# TG21_mach_nut_nhan__V1_ReV.net
KiCad netlist of a schematic drawn in Altium Designer
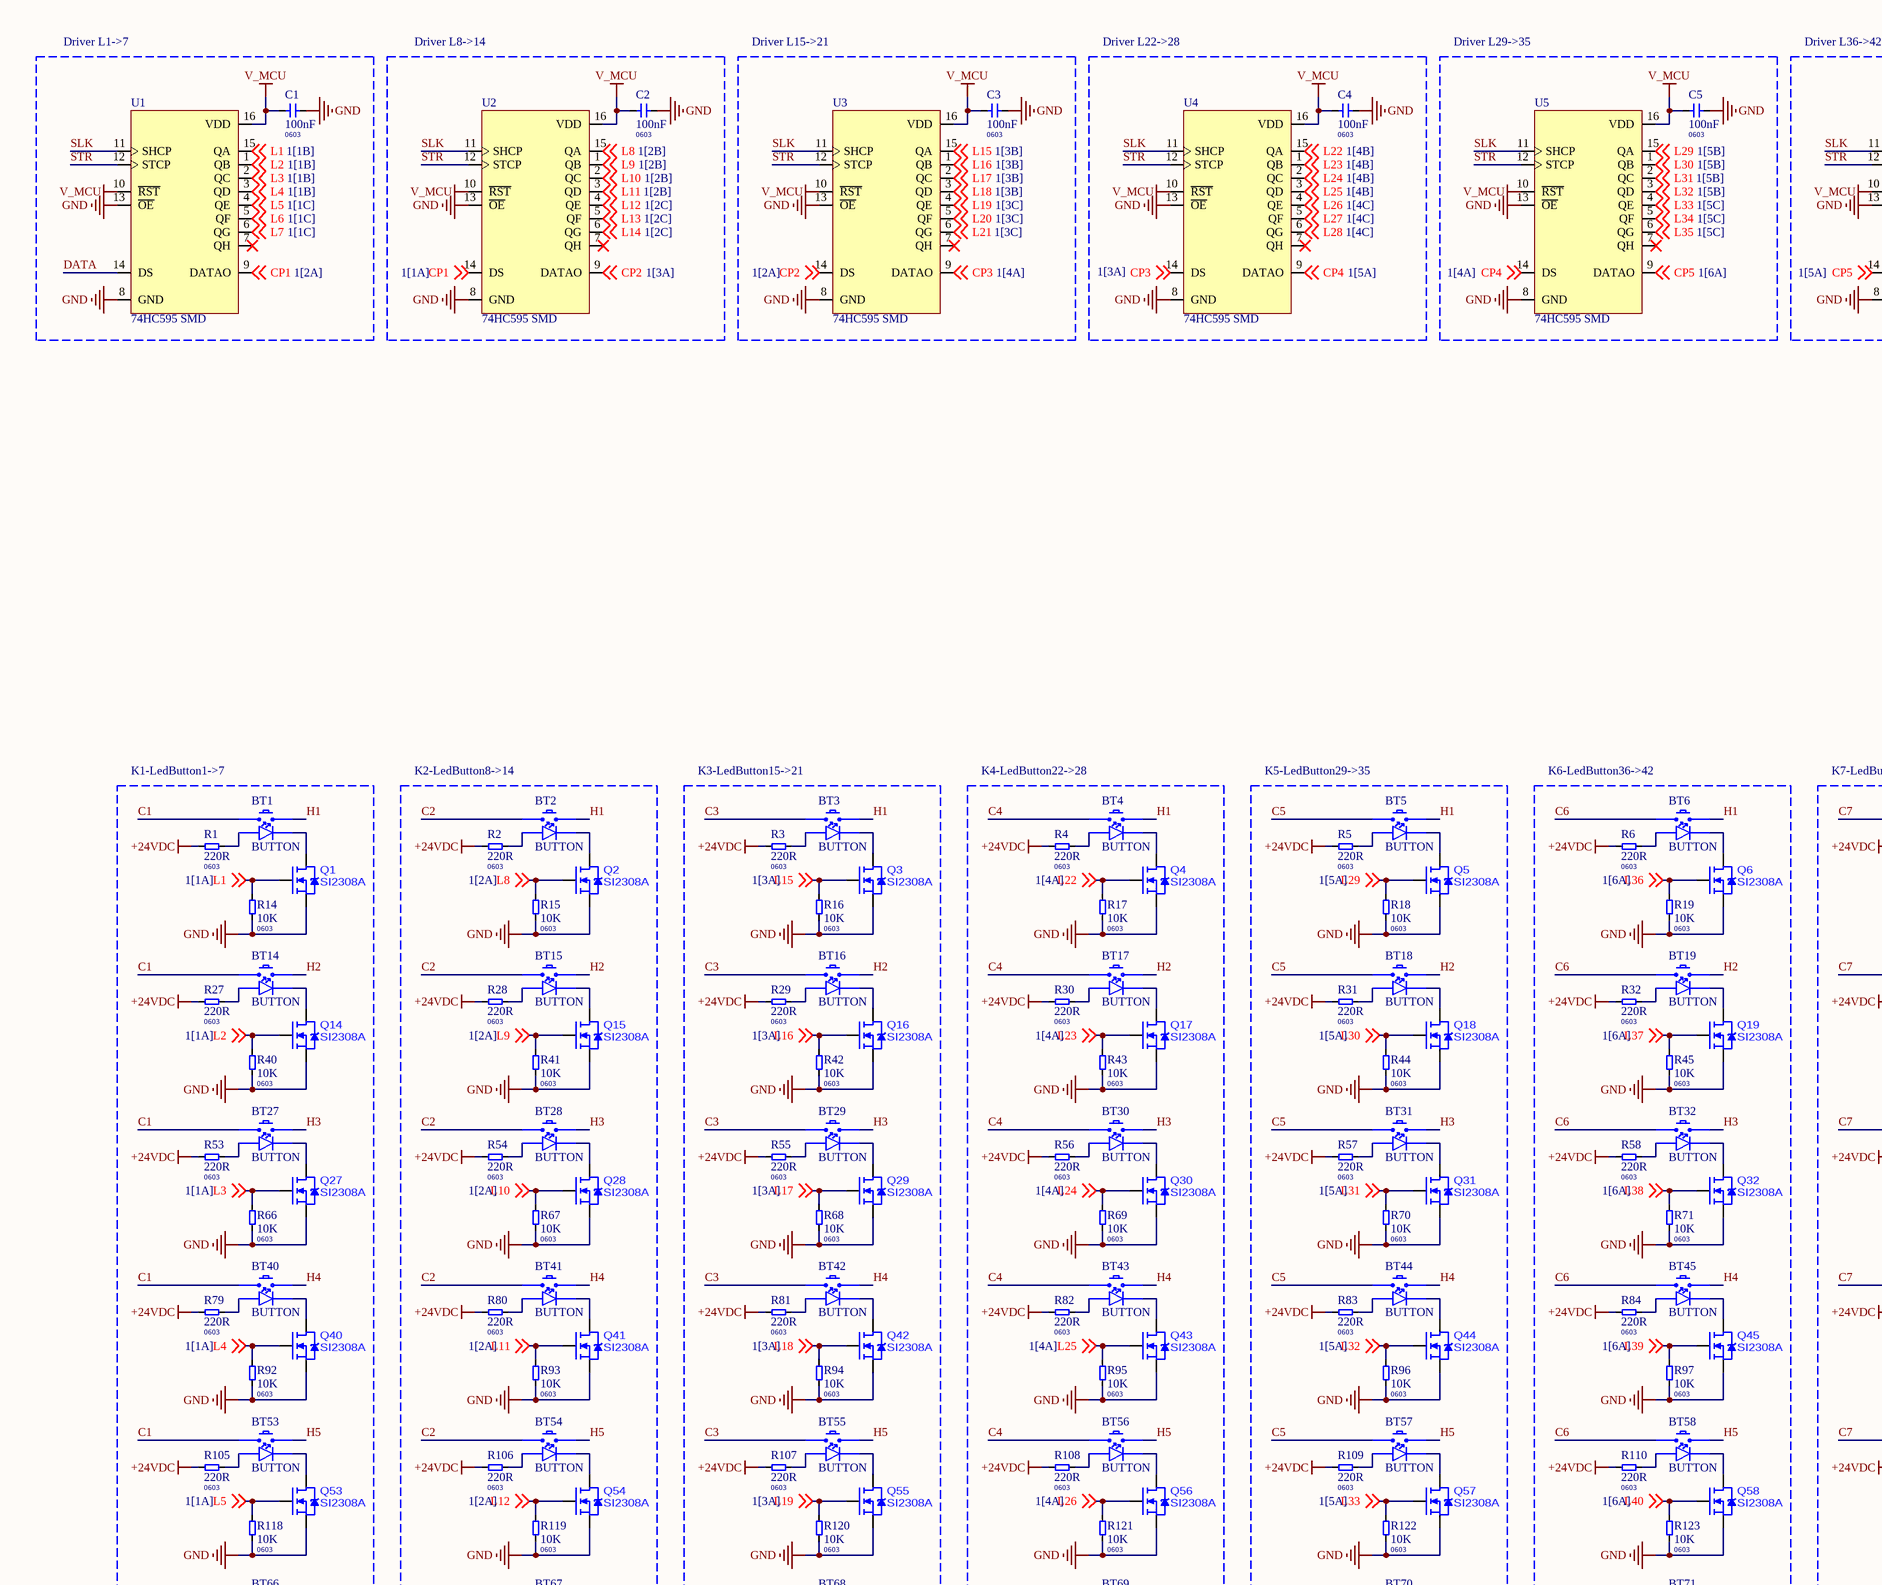
[diagram p0: TG21_mach_nut_nhan _V1_ReV.SchDoc, top left]
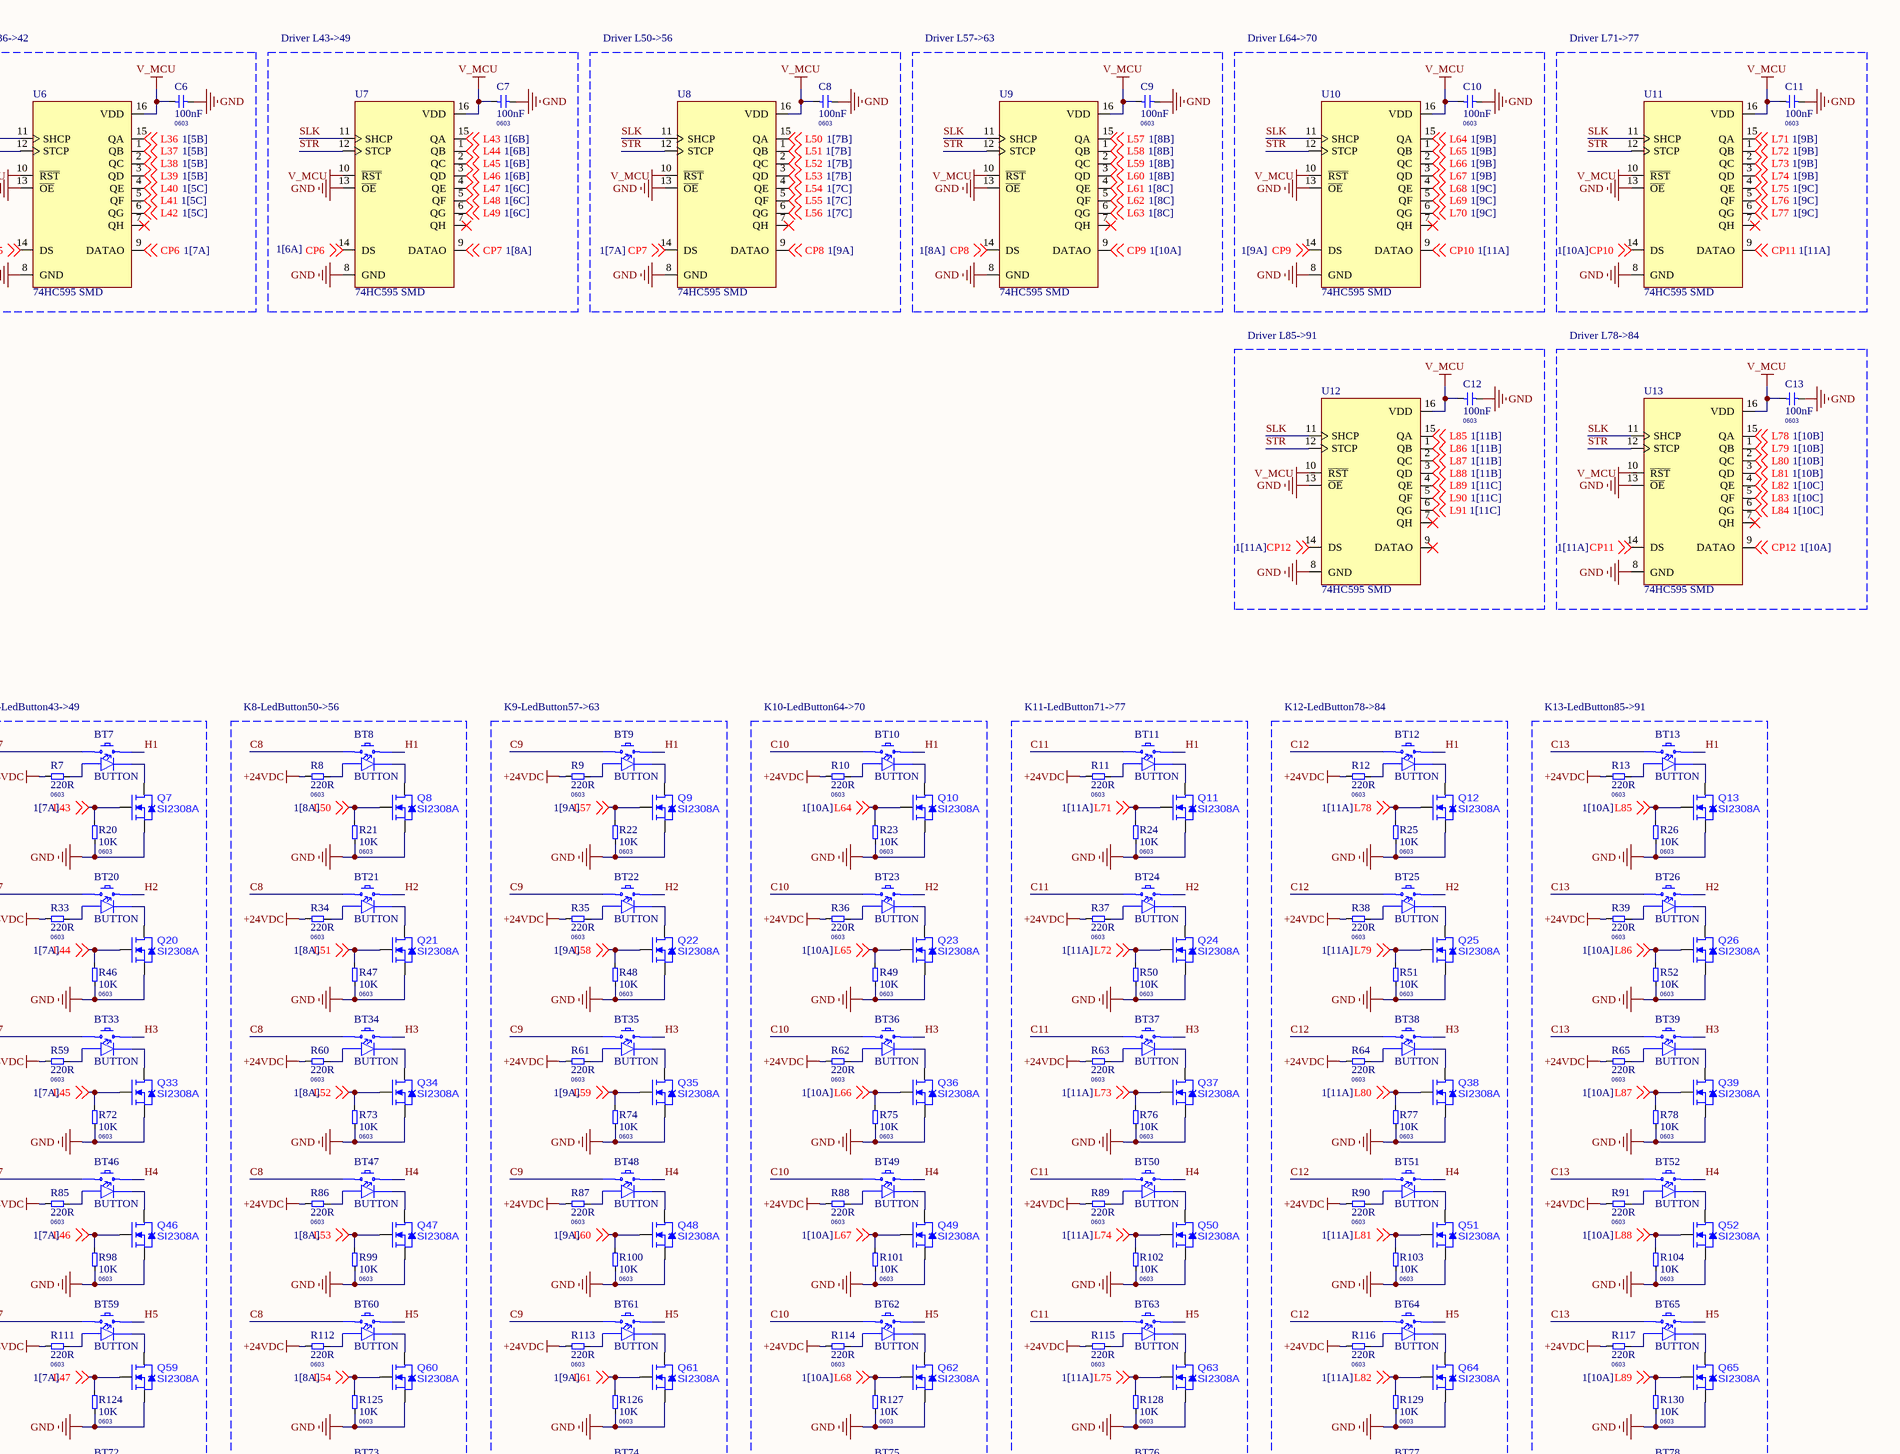
[diagram p1: TG21_mach_nut_nhan _V1_ReV.SchDoc, top right]
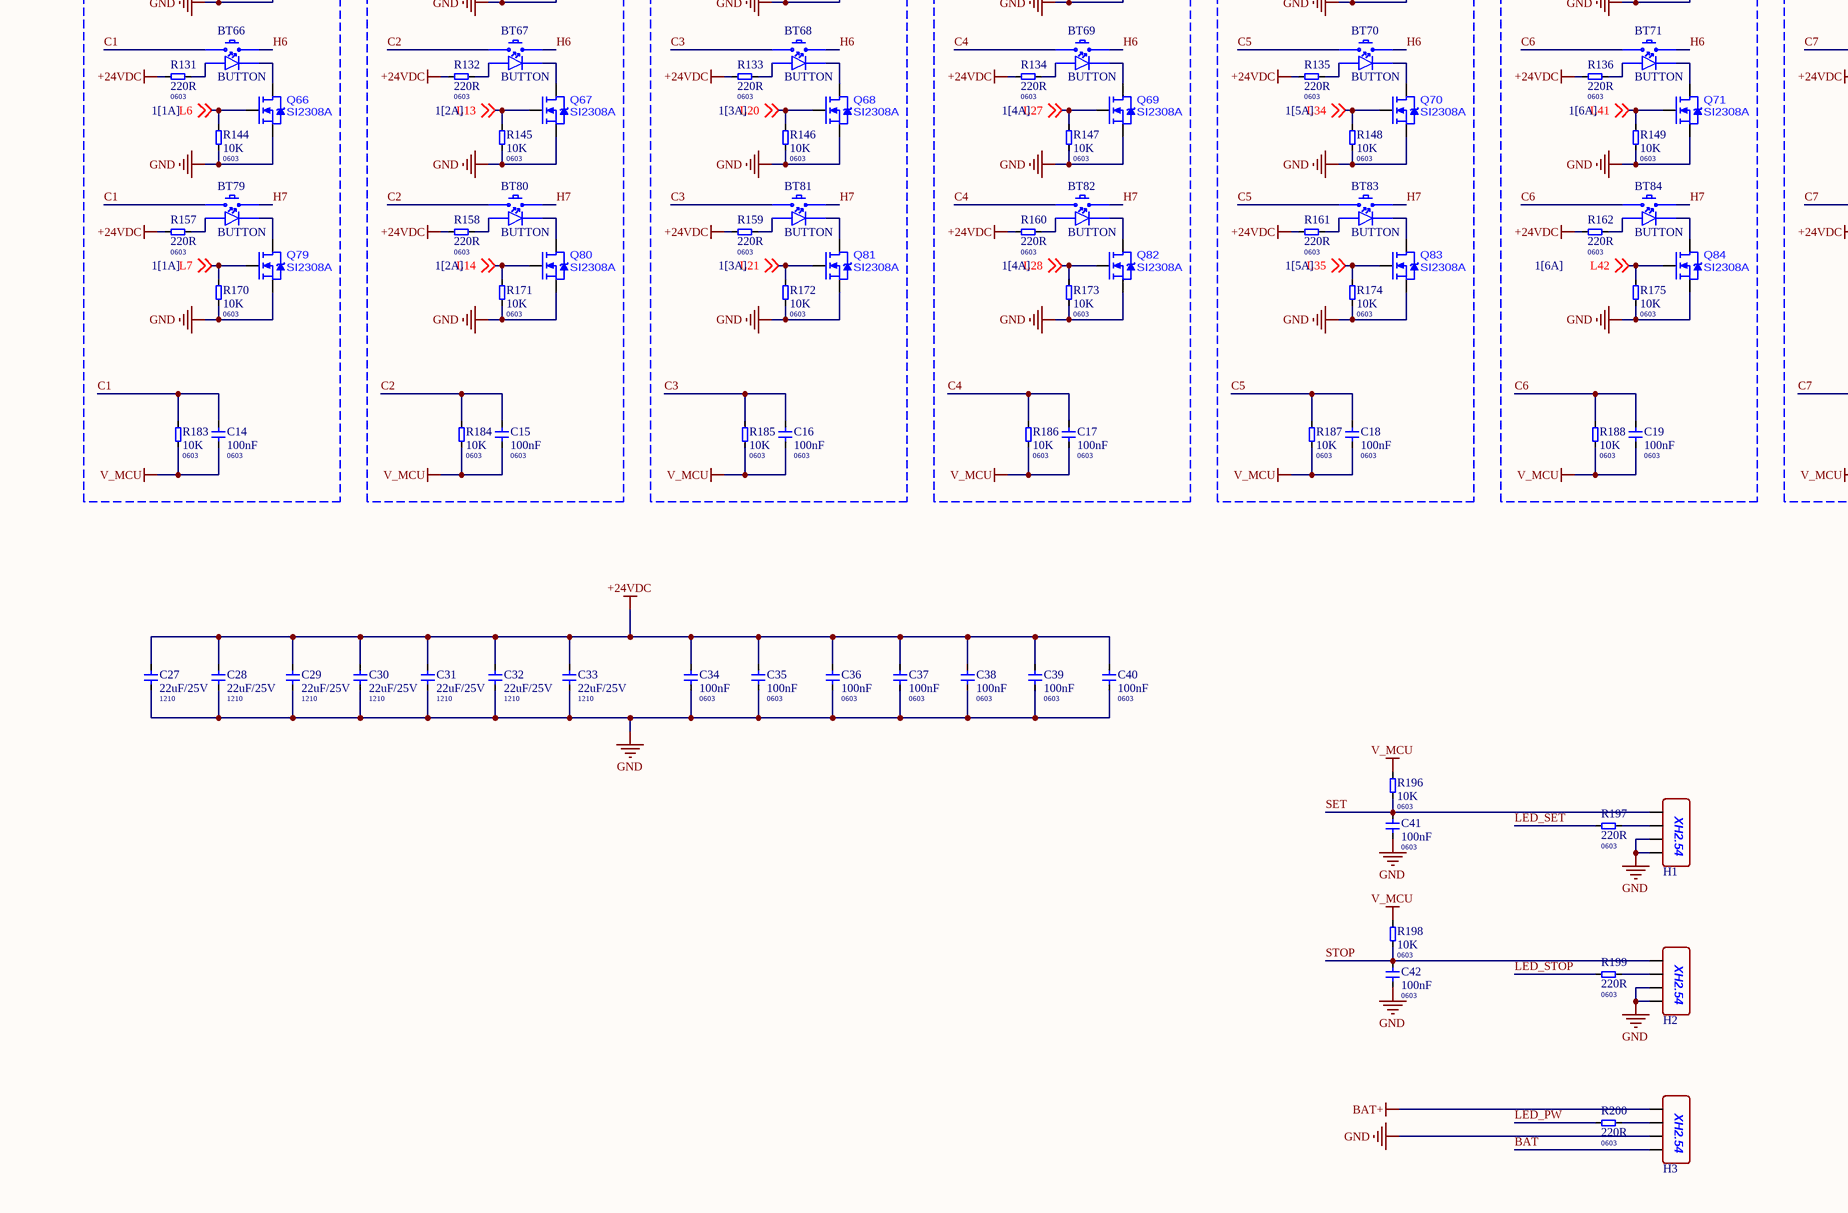
[diagram p2: TG21_mach_nut_nhan _V1_ReV.SchDoc, bottom left]
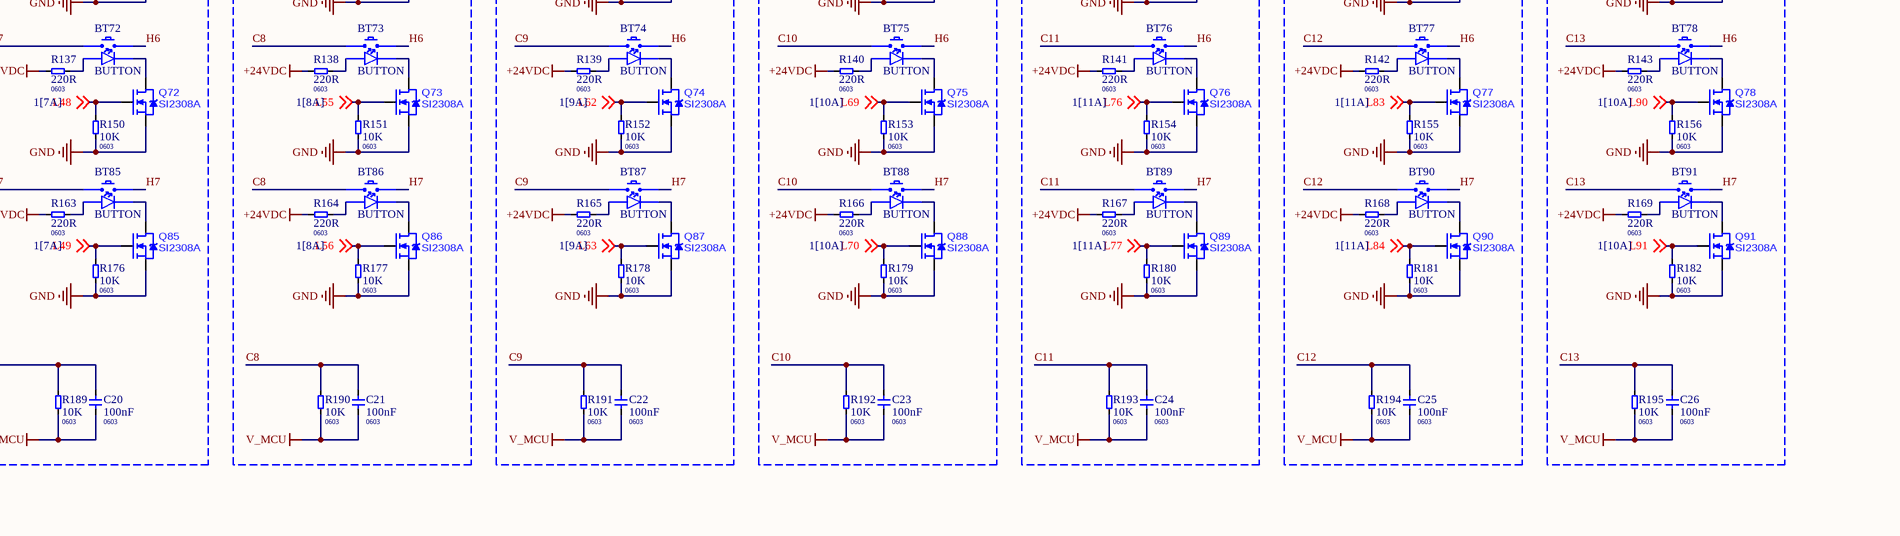
[diagram p3: TG21_mach_nut_nhan _V1_ReV.SchDoc, bottom right]

(export (version "E")
  (design (tool "Eeschema 10.0.6"))
  (components
    (comp (ref "BT1")
      (value "BUTTON")
      (footprint "Metal Push Button Switch")
      (libsource (lib "TG21_TX_Ma tran phimPrjPcb") (part "Metal Push Button Switch"))
    )
    (comp (ref "BT2")
      (value "BUTTON")
      (footprint "Metal Push Button Switch")
      (libsource (lib "TG21_TX_Ma tran phimPrjPcb") (part "Metal Push Button Switch"))
    )
    (comp (ref "BT3")
      (value "BUTTON")
      (footprint "Metal Push Button Switch")
      (libsource (lib "TG21_TX_Ma tran phimPrjPcb") (part "Metal Push Button Switch"))
    )
    (comp (ref "BT4")
      (value "BUTTON")
      (footprint "Metal Push Button Switch")
      (libsource (lib "TG21_TX_Ma tran phimPrjPcb") (part "Metal Push Button Switch"))
    )
    (comp (ref "BT5")
      (value "BUTTON")
      (footprint "Metal Push Button Switch")
      (libsource (lib "TG21_TX_Ma tran phimPrjPcb") (part "Metal Push Button Switch"))
    )
    (comp (ref "BT6")
      (value "BUTTON")
      (footprint "Metal Push Button Switch")
      (libsource (lib "TG21_TX_Ma tran phimPrjPcb") (part "Metal Push Button Switch"))
    )
    (comp (ref "BT7")
      (value "BUTTON")
      (footprint "Metal Push Button Switch")
      (libsource (lib "TG21_TX_Ma tran phimPrjPcb") (part "Metal Push Button Switch"))
    )
    (comp (ref "BT8")
      (value "BUTTON")
      (footprint "Metal Push Button Switch")
      (libsource (lib "TG21_TX_Ma tran phimPrjPcb") (part "Metal Push Button Switch"))
    )
    (comp (ref "BT9")
      (value "BUTTON")
      (footprint "Metal Push Button Switch")
      (libsource (lib "TG21_TX_Ma tran phimPrjPcb") (part "Metal Push Button Switch"))
    )
    (comp (ref "BT10")
      (value "BUTTON")
      (footprint "Metal Push Button Switch")
      (libsource (lib "TG21_TX_Ma tran phimPrjPcb") (part "Metal Push Button Switch"))
    )
    (comp (ref "BT11")
      (value "BUTTON")
      (footprint "Metal Push Button Switch")
      (libsource (lib "TG21_TX_Ma tran phimPrjPcb") (part "Metal Push Button Switch"))
    )
    (comp (ref "BT12")
      (value "BUTTON")
      (footprint "Metal Push Button Switch")
      (libsource (lib "TG21_TX_Ma tran phimPrjPcb") (part "Metal Push Button Switch"))
    )
    (comp (ref "BT13")
      (value "BUTTON")
      (footprint "Metal Push Button Switch")
      (libsource (lib "TG21_TX_Ma tran phimPrjPcb") (part "Metal Push Button Switch"))
    )
    (comp (ref "BT14")
      (value "BUTTON")
      (footprint "Metal Push Button Switch")
      (libsource (lib "TG21_TX_Ma tran phimPrjPcb") (part "Metal Push Button Switch"))
    )
    (comp (ref "BT15")
      (value "BUTTON")
      (footprint "Metal Push Button Switch")
      (libsource (lib "TG21_TX_Ma tran phimPrjPcb") (part "Metal Push Button Switch"))
    )
    (comp (ref "BT16")
      (value "BUTTON")
      (footprint "Metal Push Button Switch")
      (libsource (lib "TG21_TX_Ma tran phimPrjPcb") (part "Metal Push Button Switch"))
    )
    (comp (ref "BT17")
      (value "BUTTON")
      (footprint "Metal Push Button Switch")
      (libsource (lib "TG21_TX_Ma tran phimPrjPcb") (part "Metal Push Button Switch"))
    )
    (comp (ref "BT18")
      (value "BUTTON")
      (footprint "Metal Push Button Switch")
      (libsource (lib "TG21_TX_Ma tran phimPrjPcb") (part "Metal Push Button Switch"))
    )
    (comp (ref "BT19")
      (value "BUTTON")
      (footprint "Metal Push Button Switch")
      (libsource (lib "TG21_TX_Ma tran phimPrjPcb") (part "Metal Push Button Switch"))
    )
    (comp (ref "BT20")
      (value "BUTTON")
      (footprint "Metal Push Button Switch")
      (libsource (lib "TG21_TX_Ma tran phimPrjPcb") (part "Metal Push Button Switch"))
    )
    (comp (ref "BT21")
      (value "BUTTON")
      (footprint "Metal Push Button Switch")
      (libsource (lib "TG21_TX_Ma tran phimPrjPcb") (part "Metal Push Button Switch"))
    )
    (comp (ref "BT22")
      (value "BUTTON")
      (footprint "Metal Push Button Switch")
      (libsource (lib "TG21_TX_Ma tran phimPrjPcb") (part "Metal Push Button Switch"))
    )
    (comp (ref "BT23")
      (value "BUTTON")
      (footprint "Metal Push Button Switch")
      (libsource (lib "TG21_TX_Ma tran phimPrjPcb") (part "Metal Push Button Switch"))
    )
    (comp (ref "BT24")
      (value "BUTTON")
      (footprint "Metal Push Button Switch")
      (libsource (lib "TG21_TX_Ma tran phimPrjPcb") (part "Metal Push Button Switch"))
    )
    (comp (ref "BT25")
      (value "BUTTON")
      (footprint "Metal Push Button Switch")
      (libsource (lib "TG21_TX_Ma tran phimPrjPcb") (part "Metal Push Button Switch"))
    )
    (comp (ref "BT26")
      (value "BUTTON")
      (footprint "Metal Push Button Switch")
      (libsource (lib "TG21_TX_Ma tran phimPrjPcb") (part "Metal Push Button Switch"))
    )
    (comp (ref "BT27")
      (value "BUTTON")
      (footprint "Metal Push Button Switch")
      (libsource (lib "TG21_TX_Ma tran phimPrjPcb") (part "Metal Push Button Switch"))
    )
    (comp (ref "BT28")
      (value "BUTTON")
      (footprint "Metal Push Button Switch")
      (libsource (lib "TG21_TX_Ma tran phimPrjPcb") (part "Metal Push Button Switch"))
    )
    (comp (ref "BT29")
      (value "BUTTON")
      (footprint "Metal Push Button Switch")
      (libsource (lib "TG21_TX_Ma tran phimPrjPcb") (part "Metal Push Button Switch"))
    )
    (comp (ref "BT30")
      (value "BUTTON")
      (footprint "Metal Push Button Switch")
      (libsource (lib "TG21_TX_Ma tran phimPrjPcb") (part "Metal Push Button Switch"))
    )
    (comp (ref "BT31")
      (value "BUTTON")
      (footprint "Metal Push Button Switch")
      (libsource (lib "TG21_TX_Ma tran phimPrjPcb") (part "Metal Push Button Switch"))
    )
    (comp (ref "BT32")
      (value "BUTTON")
      (footprint "Metal Push Button Switch")
      (libsource (lib "TG21_TX_Ma tran phimPrjPcb") (part "Metal Push Button Switch"))
    )
    (comp (ref "BT33")
      (value "BUTTON")
      (footprint "Metal Push Button Switch")
      (libsource (lib "TG21_TX_Ma tran phimPrjPcb") (part "Metal Push Button Switch"))
    )
    (comp (ref "BT34")
      (value "BUTTON")
      (footprint "Metal Push Button Switch")
      (libsource (lib "TG21_TX_Ma tran phimPrjPcb") (part "Metal Push Button Switch"))
    )
    (comp (ref "BT35")
      (value "BUTTON")
      (footprint "Metal Push Button Switch")
      (libsource (lib "TG21_TX_Ma tran phimPrjPcb") (part "Metal Push Button Switch"))
    )
    (comp (ref "BT36")
      (value "BUTTON")
      (footprint "Metal Push Button Switch")
      (libsource (lib "TG21_TX_Ma tran phimPrjPcb") (part "Metal Push Button Switch"))
    )
    (comp (ref "BT37")
      (value "BUTTON")
      (footprint "Metal Push Button Switch")
      (libsource (lib "TG21_TX_Ma tran phimPrjPcb") (part "Metal Push Button Switch"))
    )
    (comp (ref "BT38")
      (value "BUTTON")
      (footprint "Metal Push Button Switch")
      (libsource (lib "TG21_TX_Ma tran phimPrjPcb") (part "Metal Push Button Switch"))
    )
    (comp (ref "BT39")
      (value "BUTTON")
      (footprint "Metal Push Button Switch")
      (libsource (lib "TG21_TX_Ma tran phimPrjPcb") (part "Metal Push Button Switch"))
    )
    (comp (ref "BT40")
      (value "BUTTON")
      (footprint "Metal Push Button Switch")
      (libsource (lib "TG21_TX_Ma tran phimPrjPcb") (part "Metal Push Button Switch"))
    )
    (comp (ref "BT41")
      (value "BUTTON")
      (footprint "Metal Push Button Switch")
      (libsource (lib "TG21_TX_Ma tran phimPrjPcb") (part "Metal Push Button Switch"))
    )
    (comp (ref "BT42")
      (value "BUTTON")
      (footprint "Metal Push Button Switch")
      (libsource (lib "TG21_TX_Ma tran phimPrjPcb") (part "Metal Push Button Switch"))
    )
    (comp (ref "BT43")
      (value "BUTTON")
      (footprint "Metal Push Button Switch")
      (libsource (lib "TG21_TX_Ma tran phimPrjPcb") (part "Metal Push Button Switch"))
    )
    (comp (ref "BT44")
      (value "BUTTON")
      (footprint "Metal Push Button Switch")
      (libsource (lib "TG21_TX_Ma tran phimPrjPcb") (part "Metal Push Button Switch"))
    )
    (comp (ref "BT45")
      (value "BUTTON")
      (footprint "Metal Push Button Switch")
      (libsource (lib "TG21_TX_Ma tran phimPrjPcb") (part "Metal Push Button Switch"))
    )
    (comp (ref "BT46")
      (value "BUTTON")
      (footprint "Metal Push Button Switch")
      (libsource (lib "TG21_TX_Ma tran phimPrjPcb") (part "Metal Push Button Switch"))
    )
    (comp (ref "BT47")
      (value "BUTTON")
      (footprint "Metal Push Button Switch")
      (libsource (lib "TG21_TX_Ma tran phimPrjPcb") (part "Metal Push Button Switch"))
    )
    (comp (ref "BT48")
      (value "BUTTON")
      (footprint "Metal Push Button Switch")
      (libsource (lib "TG21_TX_Ma tran phimPrjPcb") (part "Metal Push Button Switch"))
    )
    (comp (ref "BT49")
      (value "BUTTON")
      (footprint "Metal Push Button Switch")
      (libsource (lib "TG21_TX_Ma tran phimPrjPcb") (part "Metal Push Button Switch"))
    )
    (comp (ref "BT50")
      (value "BUTTON")
      (footprint "Metal Push Button Switch")
      (libsource (lib "TG21_TX_Ma tran phimPrjPcb") (part "Metal Push Button Switch"))
    )
    (comp (ref "BT51")
      (value "BUTTON")
      (footprint "Metal Push Button Switch")
      (libsource (lib "TG21_TX_Ma tran phimPrjPcb") (part "Metal Push Button Switch"))
    )
    (comp (ref "BT52")
      (value "BUTTON")
      (footprint "Metal Push Button Switch")
      (libsource (lib "TG21_TX_Ma tran phimPrjPcb") (part "Metal Push Button Switch"))
    )
    (comp (ref "BT53")
      (value "BUTTON")
      (footprint "Metal Push Button Switch")
      (libsource (lib "TG21_TX_Ma tran phimPrjPcb") (part "Metal Push Button Switch"))
    )
    (comp (ref "BT54")
      (value "BUTTON")
      (footprint "Metal Push Button Switch")
      (libsource (lib "TG21_TX_Ma tran phimPrjPcb") (part "Metal Push Button Switch"))
    )
    (comp (ref "BT55")
      (value "BUTTON")
      (footprint "Metal Push Button Switch")
      (libsource (lib "TG21_TX_Ma tran phimPrjPcb") (part "Metal Push Button Switch"))
    )
    (comp (ref "BT56")
      (value "BUTTON")
      (footprint "Metal Push Button Switch")
      (libsource (lib "TG21_TX_Ma tran phimPrjPcb") (part "Metal Push Button Switch"))
    )
    (comp (ref "BT57")
      (value "BUTTON")
      (footprint "Metal Push Button Switch")
      (libsource (lib "TG21_TX_Ma tran phimPrjPcb") (part "Metal Push Button Switch"))
    )
    (comp (ref "BT58")
      (value "BUTTON")
      (footprint "Metal Push Button Switch")
      (libsource (lib "TG21_TX_Ma tran phimPrjPcb") (part "Metal Push Button Switch"))
    )
    (comp (ref "BT59")
      (value "BUTTON")
      (footprint "Metal Push Button Switch")
      (libsource (lib "TG21_TX_Ma tran phimPrjPcb") (part "Metal Push Button Switch"))
    )
    (comp (ref "BT60")
      (value "BUTTON")
      (footprint "Metal Push Button Switch")
      (libsource (lib "TG21_TX_Ma tran phimPrjPcb") (part "Metal Push Button Switch"))
    )
    (comp (ref "BT61")
      (value "BUTTON")
      (footprint "Metal Push Button Switch")
      (libsource (lib "TG21_TX_Ma tran phimPrjPcb") (part "Metal Push Button Switch"))
    )
    (comp (ref "BT62")
      (value "BUTTON")
      (footprint "Metal Push Button Switch")
      (libsource (lib "TG21_TX_Ma tran phimPrjPcb") (part "Metal Push Button Switch"))
    )
    (comp (ref "BT63")
      (value "BUTTON")
      (footprint "Metal Push Button Switch")
      (libsource (lib "TG21_TX_Ma tran phimPrjPcb") (part "Metal Push Button Switch"))
    )
    (comp (ref "BT64")
      (value "BUTTON")
      (footprint "Metal Push Button Switch")
      (libsource (lib "TG21_TX_Ma tran phimPrjPcb") (part "Metal Push Button Switch"))
    )
    (comp (ref "BT65")
      (value "BUTTON")
      (footprint "Metal Push Button Switch")
      (libsource (lib "TG21_TX_Ma tran phimPrjPcb") (part "Metal Push Button Switch"))
    )
    (comp (ref "BT66")
      (value "BUTTON")
      (footprint "Metal Push Button Switch")
      (libsource (lib "TG21_TX_Ma tran phimPrjPcb") (part "Metal Push Button Switch"))
    )
    (comp (ref "BT67")
      (value "BUTTON")
      (footprint "Metal Push Button Switch")
      (libsource (lib "TG21_TX_Ma tran phimPrjPcb") (part "Metal Push Button Switch"))
    )
    (comp (ref "BT68")
      (value "BUTTON")
      (footprint "Metal Push Button Switch")
      (libsource (lib "TG21_TX_Ma tran phimPrjPcb") (part "Metal Push Button Switch"))
    )
    (comp (ref "BT69")
      (value "BUTTON")
      (footprint "Metal Push Button Switch")
      (libsource (lib "TG21_TX_Ma tran phimPrjPcb") (part "Metal Push Button Switch"))
    )
    (comp (ref "BT70")
      (value "BUTTON")
      (footprint "Metal Push Button Switch")
      (libsource (lib "TG21_TX_Ma tran phimPrjPcb") (part "Metal Push Button Switch"))
    )
    (comp (ref "BT71")
      (value "BUTTON")
      (footprint "Metal Push Button Switch")
      (libsource (lib "TG21_TX_Ma tran phimPrjPcb") (part "Metal Push Button Switch"))
    )
    (comp (ref "BT72")
      (value "BUTTON")
      (footprint "Metal Push Button Switch")
      (libsource (lib "TG21_TX_Ma tran phimPrjPcb") (part "Metal Push Button Switch"))
    )
    (comp (ref "BT73")
      (value "BUTTON")
      (footprint "Metal Push Button Switch")
      (libsource (lib "TG21_TX_Ma tran phimPrjPcb") (part "Metal Push Button Switch"))
    )
    (comp (ref "BT74")
      (value "BUTTON")
      (footprint "Metal Push Button Switch")
      (libsource (lib "TG21_TX_Ma tran phimPrjPcb") (part "Metal Push Button Switch"))
    )
    (comp (ref "BT75")
      (value "BUTTON")
      (footprint "Metal Push Button Switch")
      (libsource (lib "TG21_TX_Ma tran phimPrjPcb") (part "Metal Push Button Switch"))
    )
    (comp (ref "BT76")
      (value "BUTTON")
      (footprint "Metal Push Button Switch")
      (libsource (lib "TG21_TX_Ma tran phimPrjPcb") (part "Metal Push Button Switch"))
    )
    (comp (ref "BT77")
      (value "BUTTON")
      (footprint "Metal Push Button Switch")
      (libsource (lib "TG21_TX_Ma tran phimPrjPcb") (part "Metal Push Button Switch"))
    )
    (comp (ref "BT78")
      (value "BUTTON")
      (footprint "Metal Push Button Switch")
      (libsource (lib "TG21_TX_Ma tran phimPrjPcb") (part "Metal Push Button Switch"))
    )
    (comp (ref "BT79")
      (value "BUTTON")
      (footprint "Metal Push Button Switch")
      (libsource (lib "TG21_TX_Ma tran phimPrjPcb") (part "Metal Push Button Switch"))
    )
    (comp (ref "BT80")
      (value "BUTTON")
      (footprint "Metal Push Button Switch")
      (libsource (lib "TG21_TX_Ma tran phimPrjPcb") (part "Metal Push Button Switch"))
    )
    (comp (ref "BT81")
      (value "BUTTON")
      (footprint "Metal Push Button Switch")
      (libsource (lib "TG21_TX_Ma tran phimPrjPcb") (part "Metal Push Button Switch"))
    )
    (comp (ref "BT82")
      (value "BUTTON")
      (footprint "Metal Push Button Switch")
      (libsource (lib "TG21_TX_Ma tran phimPrjPcb") (part "Metal Push Button Switch"))
    )
    (comp (ref "BT83")
      (value "BUTTON")
      (footprint "Metal Push Button Switch")
      (libsource (lib "TG21_TX_Ma tran phimPrjPcb") (part "Metal Push Button Switch"))
    )
    (comp (ref "BT84")
      (value "BUTTON")
      (footprint "Metal Push Button Switch")
      (libsource (lib "TG21_TX_Ma tran phimPrjPcb") (part "Metal Push Button Switch"))
    )
    (comp (ref "BT85")
      (value "BUTTON")
      (footprint "Metal Push Button Switch")
      (libsource (lib "TG21_TX_Ma tran phimPrjPcb") (part "Metal Push Button Switch"))
    )
    (comp (ref "BT86")
      (value "BUTTON")
      (footprint "Metal Push Button Switch")
      (libsource (lib "TG21_TX_Ma tran phimPrjPcb") (part "Metal Push Button Switch"))
    )
    (comp (ref "BT87")
      (value "BUTTON")
      (footprint "Metal Push Button Switch")
      (libsource (lib "TG21_TX_Ma tran phimPrjPcb") (part "Metal Push Button Switch"))
    )
    (comp (ref "BT88")
      (value "BUTTON")
      (footprint "Metal Push Button Switch")
      (libsource (lib "TG21_TX_Ma tran phimPrjPcb") (part "Metal Push Button Switch"))
    )
    (comp (ref "BT89")
      (value "BUTTON")
      (footprint "Metal Push Button Switch")
      (libsource (lib "TG21_TX_Ma tran phimPrjPcb") (part "Metal Push Button Switch"))
    )
    (comp (ref "BT90")
      (value "BUTTON")
      (footprint "Metal Push Button Switch")
      (libsource (lib "TG21_TX_Ma tran phimPrjPcb") (part "Metal Push Button Switch"))
    )
    (comp (ref "BT91")
      (value "BUTTON")
      (footprint "Metal Push Button Switch")
      (libsource (lib "TG21_TX_Ma tran phimPrjPcb") (part "Metal Push Button Switch"))
    )
    (comp (ref "C1")
      (value "100nF")
      (footprint "0603 MLCC")
      (description "100nF ±10% 50V Ceramic Capacitor X7R 0603")
      (fields
        (field (name "MANUFACTURER") "YAGEO")
        (field (name "MFR. PART #") "CC0603KRX7R9BB104")
        (field (name "PACKAGE") "0603")
      )
      (libsource (lib "TG21_TX_Ma tran phimPrjPcb") (part "0603 100nF"))
    )
    (comp (ref "C2")
      (value "100nF")
      (footprint "0603 MLCC")
      (description "100nF ±10% 50V Ceramic Capacitor X7R 0603")
      (fields
        (field (name "MANUFACTURER") "YAGEO")
        (field (name "MFR. PART #") "CC0603KRX7R9BB104")
        (field (name "PACKAGE") "0603")
      )
      (libsource (lib "TG21_TX_Ma tran phimPrjPcb") (part "0603 100nF"))
    )
    (comp (ref "C3")
      (value "100nF")
      (footprint "0603 MLCC")
      (description "100nF ±10% 50V Ceramic Capacitor X7R 0603")
      (fields
        (field (name "MANUFACTURER") "YAGEO")
        (field (name "MFR. PART #") "CC0603KRX7R9BB104")
        (field (name "PACKAGE") "0603")
      )
      (libsource (lib "TG21_TX_Ma tran phimPrjPcb") (part "0603 100nF"))
    )
    (comp (ref "C4")
      (value "100nF")
      (footprint "0603 MLCC")
      (description "100nF ±10% 50V Ceramic Capacitor X7R 0603")
      (fields
        (field (name "MANUFACTURER") "YAGEO")
        (field (name "MFR. PART #") "CC0603KRX7R9BB104")
        (field (name "PACKAGE") "0603")
      )
      (libsource (lib "TG21_TX_Ma tran phimPrjPcb") (part "0603 100nF"))
    )
    (comp (ref "C5")
      (value "100nF")
      (footprint "0603 MLCC")
      (description "100nF ±10% 50V Ceramic Capacitor X7R 0603")
      (fields
        (field (name "MANUFACTURER") "YAGEO")
        (field (name "MFR. PART #") "CC0603KRX7R9BB104")
        (field (name "PACKAGE") "0603")
      )
      (libsource (lib "TG21_TX_Ma tran phimPrjPcb") (part "0603 100nF"))
    )
    (comp (ref "C6")
      (value "100nF")
      (footprint "0603 MLCC")
      (description "100nF ±10% 50V Ceramic Capacitor X7R 0603")
      (fields
        (field (name "MANUFACTURER") "YAGEO")
        (field (name "MFR. PART #") "CC0603KRX7R9BB104")
        (field (name "PACKAGE") "0603")
      )
      (libsource (lib "TG21_TX_Ma tran phimPrjPcb") (part "0603 100nF"))
    )
    (comp (ref "C7")
      (value "100nF")
      (footprint "0603 MLCC")
      (description "100nF ±10% 50V Ceramic Capacitor X7R 0603")
      (fields
        (field (name "MANUFACTURER") "YAGEO")
        (field (name "MFR. PART #") "CC0603KRX7R9BB104")
        (field (name "PACKAGE") "0603")
      )
      (libsource (lib "TG21_TX_Ma tran phimPrjPcb") (part "0603 100nF"))
    )
    (comp (ref "C8")
      (value "100nF")
      (footprint "0603 MLCC")
      (description "100nF ±10% 50V Ceramic Capacitor X7R 0603")
      (fields
        (field (name "MANUFACTURER") "YAGEO")
        (field (name "MFR. PART #") "CC0603KRX7R9BB104")
        (field (name "PACKAGE") "0603")
      )
      (libsource (lib "TG21_TX_Ma tran phimPrjPcb") (part "0603 100nF"))
    )
    (comp (ref "C9")
      (value "100nF")
      (footprint "0603 MLCC")
      (description "100nF ±10% 50V Ceramic Capacitor X7R 0603")
      (fields
        (field (name "MANUFACTURER") "YAGEO")
        (field (name "MFR. PART #") "CC0603KRX7R9BB104")
        (field (name "PACKAGE") "0603")
      )
      (libsource (lib "TG21_TX_Ma tran phimPrjPcb") (part "0603 100nF"))
    )
    (comp (ref "C10")
      (value "100nF")
      (footprint "0603 MLCC")
      (description "100nF ±10% 50V Ceramic Capacitor X7R 0603")
      (fields
        (field (name "MANUFACTURER") "YAGEO")
        (field (name "MFR. PART #") "CC0603KRX7R9BB104")
        (field (name "PACKAGE") "0603")
      )
      (libsource (lib "TG21_TX_Ma tran phimPrjPcb") (part "0603 100nF"))
    )
    (comp (ref "C11")
      (value "100nF")
      (footprint "0603 MLCC")
      (description "100nF ±10% 50V Ceramic Capacitor X7R 0603")
      (fields
        (field (name "MANUFACTURER") "YAGEO")
        (field (name "MFR. PART #") "CC0603KRX7R9BB104")
        (field (name "PACKAGE") "0603")
      )
      (libsource (lib "TG21_TX_Ma tran phimPrjPcb") (part "0603 100nF"))
    )
    (comp (ref "C12")
      (value "100nF")
      (footprint "0603 MLCC")
      (description "100nF ±10% 50V Ceramic Capacitor X7R 0603")
      (fields
        (field (name "MANUFACTURER") "YAGEO")
        (field (name "MFR. PART #") "CC0603KRX7R9BB104")
        (field (name "PACKAGE") "0603")
      )
      (libsource (lib "TG21_TX_Ma tran phimPrjPcb") (part "0603 100nF"))
    )
    (comp (ref "C13")
      (value "100nF")
      (footprint "0603 MLCC")
      (description "100nF ±10% 50V Ceramic Capacitor X7R 0603")
      (fields
        (field (name "MANUFACTURER") "YAGEO")
        (field (name "MFR. PART #") "CC0603KRX7R9BB104")
        (field (name "PACKAGE") "0603")
      )
      (libsource (lib "TG21_TX_Ma tran phimPrjPcb") (part "0603 100nF"))
    )
    (comp (ref "C14")
      (value "100nF")
      (footprint "0603 MLCC")
      (description "100nF ±10% 50V Ceramic Capacitor X7R 0603")
      (fields
        (field (name "MANUFACTURER") "YAGEO")
        (field (name "MFR. PART #") "CC0603KRX7R9BB104")
        (field (name "PACKAGE") "0603")
      )
      (libsource (lib "TG21_TX_Ma tran phimPrjPcb") (part "0603 100nF"))
    )
    (comp (ref "C15")
      (value "100nF")
      (footprint "0603 MLCC")
      (description "100nF ±10% 50V Ceramic Capacitor X7R 0603")
      (fields
        (field (name "MANUFACTURER") "YAGEO")
        (field (name "MFR. PART #") "CC0603KRX7R9BB104")
        (field (name "PACKAGE") "0603")
      )
      (libsource (lib "TG21_TX_Ma tran phimPrjPcb") (part "0603 100nF"))
    )
    (comp (ref "C16")
      (value "100nF")
      (footprint "0603 MLCC")
      (description "100nF ±10% 50V Ceramic Capacitor X7R 0603")
      (fields
        (field (name "MANUFACTURER") "YAGEO")
        (field (name "MFR. PART #") "CC0603KRX7R9BB104")
        (field (name "PACKAGE") "0603")
      )
      (libsource (lib "TG21_TX_Ma tran phimPrjPcb") (part "0603 100nF"))
    )
    (comp (ref "C17")
      (value "100nF")
      (footprint "0603 MLCC")
      (description "100nF ±10% 50V Ceramic Capacitor X7R 0603")
      (fields
        (field (name "MANUFACTURER") "YAGEO")
        (field (name "MFR. PART #") "CC0603KRX7R9BB104")
        (field (name "PACKAGE") "0603")
      )
      (libsource (lib "TG21_TX_Ma tran phimPrjPcb") (part "0603 100nF"))
    )
    (comp (ref "C18")
      (value "100nF")
      (footprint "0603 MLCC")
      (description "100nF ±10% 50V Ceramic Capacitor X7R 0603")
      (fields
        (field (name "MANUFACTURER") "YAGEO")
        (field (name "MFR. PART #") "CC0603KRX7R9BB104")
        (field (name "PACKAGE") "0603")
      )
      (libsource (lib "TG21_TX_Ma tran phimPrjPcb") (part "0603 100nF"))
    )
    (comp (ref "C19")
      (value "100nF")
      (footprint "0603 MLCC")
      (description "100nF ±10% 50V Ceramic Capacitor X7R 0603")
      (fields
        (field (name "MANUFACTURER") "YAGEO")
        (field (name "MFR. PART #") "CC0603KRX7R9BB104")
        (field (name "PACKAGE") "0603")
      )
      (libsource (lib "TG21_TX_Ma tran phimPrjPcb") (part "0603 100nF"))
    )
    (comp (ref "C20")
      (value "100nF")
      (footprint "0603 MLCC")
      (description "100nF ±10% 50V Ceramic Capacitor X7R 0603")
      (fields
        (field (name "MANUFACTURER") "YAGEO")
        (field (name "MFR. PART #") "CC0603KRX7R9BB104")
        (field (name "PACKAGE") "0603")
      )
      (libsource (lib "TG21_TX_Ma tran phimPrjPcb") (part "0603 100nF"))
    )
    (comp (ref "C21")
      (value "100nF")
      (footprint "0603 MLCC")
      (description "100nF ±10% 50V Ceramic Capacitor X7R 0603")
      (fields
        (field (name "MANUFACTURER") "YAGEO")
        (field (name "MFR. PART #") "CC0603KRX7R9BB104")
        (field (name "PACKAGE") "0603")
      )
      (libsource (lib "TG21_TX_Ma tran phimPrjPcb") (part "0603 100nF"))
    )
    (comp (ref "C22")
      (value "100nF")
      (footprint "0603 MLCC")
      (description "100nF ±10% 50V Ceramic Capacitor X7R 0603")
      (fields
        (field (name "MANUFACTURER") "YAGEO")
        (field (name "MFR. PART #") "CC0603KRX7R9BB104")
        (field (name "PACKAGE") "0603")
      )
      (libsource (lib "TG21_TX_Ma tran phimPrjPcb") (part "0603 100nF"))
    )
    (comp (ref "C23")
      (value "100nF")
      (footprint "0603 MLCC")
      (description "100nF ±10% 50V Ceramic Capacitor X7R 0603")
      (fields
        (field (name "MANUFACTURER") "YAGEO")
        (field (name "MFR. PART #") "CC0603KRX7R9BB104")
        (field (name "PACKAGE") "0603")
      )
      (libsource (lib "TG21_TX_Ma tran phimPrjPcb") (part "0603 100nF"))
    )
    (comp (ref "C24")
      (value "100nF")
      (footprint "0603 MLCC")
      (description "100nF ±10% 50V Ceramic Capacitor X7R 0603")
      (fields
        (field (name "MANUFACTURER") "YAGEO")
        (field (name "MFR. PART #") "CC0603KRX7R9BB104")
        (field (name "PACKAGE") "0603")
      )
      (libsource (lib "TG21_TX_Ma tran phimPrjPcb") (part "0603 100nF"))
    )
    (comp (ref "C25")
      (value "100nF")
      (footprint "0603 MLCC")
      (description "100nF ±10% 50V Ceramic Capacitor X7R 0603")
      (fields
        (field (name "MANUFACTURER") "YAGEO")
        (field (name "MFR. PART #") "CC0603KRX7R9BB104")
        (field (name "PACKAGE") "0603")
      )
      (libsource (lib "TG21_TX_Ma tran phimPrjPcb") (part "0603 100nF"))
    )
    (comp (ref "C26")
      (value "100nF")
      (footprint "0603 MLCC")
      (description "100nF ±10% 50V Ceramic Capacitor X7R 0603")
      (fields
        (field (name "MANUFACTURER") "YAGEO")
        (field (name "MFR. PART #") "CC0603KRX7R9BB104")
        (field (name "PACKAGE") "0603")
      )
      (libsource (lib "TG21_TX_Ma tran phimPrjPcb") (part "0603 100nF"))
    )
    (comp (ref "C27")
      (value "22uF/25V")
      (footprint "1210 CAPACITOR")
      (description "22uF ±10% 25V Ceramic Capacitor X7R 1210")
      (fields
        (field (name "MANUFACTURER") "Samsung Electro-Mechanics")
        (field (name "MFR. PART #") "CL32B226KAJNNNE")
        (field (name "PACKAGE") "1210")
      )
      (libsource (lib "TG21_TX_Ma tran phimPrjPcb") (part "1210 22uF 25V X7R"))
    )
    (comp (ref "C28")
      (value "22uF/25V")
      (footprint "1210 CAPACITOR")
      (description "22uF ±10% 25V Ceramic Capacitor X7R 1210")
      (fields
        (field (name "MANUFACTURER") "Samsung Electro-Mechanics")
        (field (name "MFR. PART #") "CL32B226KAJNNNE")
        (field (name "PACKAGE") "1210")
      )
      (libsource (lib "TG21_TX_Ma tran phimPrjPcb") (part "1210 22uF 25V X7R"))
    )
    (comp (ref "C29")
      (value "22uF/25V")
      (footprint "1210 CAPACITOR")
      (description "22uF ±10% 25V Ceramic Capacitor X7R 1210")
      (fields
        (field (name "MANUFACTURER") "Samsung Electro-Mechanics")
        (field (name "MFR. PART #") "CL32B226KAJNNNE")
        (field (name "PACKAGE") "1210")
      )
      (libsource (lib "TG21_TX_Ma tran phimPrjPcb") (part "1210 22uF 25V X7R"))
    )
    (comp (ref "C30")
      (value "22uF/25V")
      (footprint "1210 CAPACITOR")
      (description "22uF ±10% 25V Ceramic Capacitor X7R 1210")
      (fields
        (field (name "MANUFACTURER") "Samsung Electro-Mechanics")
        (field (name "MFR. PART #") "CL32B226KAJNNNE")
        (field (name "PACKAGE") "1210")
      )
      (libsource (lib "TG21_TX_Ma tran phimPrjPcb") (part "1210 22uF 25V X7R"))
    )
    (comp (ref "C31")
      (value "22uF/25V")
      (footprint "1210 CAPACITOR")
      (description "22uF ±10% 25V Ceramic Capacitor X7R 1210")
      (fields
        (field (name "MANUFACTURER") "Samsung Electro-Mechanics")
        (field (name "MFR. PART #") "CL32B226KAJNNNE")
        (field (name "PACKAGE") "1210")
      )
      (libsource (lib "TG21_TX_Ma tran phimPrjPcb") (part "1210 22uF 25V X7R"))
    )
    (comp (ref "C32")
      (value "22uF/25V")
      (footprint "1210 CAPACITOR")
      (description "22uF ±10% 25V Ceramic Capacitor X7R 1210")
      (fields
        (field (name "MANUFACTURER") "Samsung Electro-Mechanics")
        (field (name "MFR. PART #") "CL32B226KAJNNNE")
        (field (name "PACKAGE") "1210")
      )
      (libsource (lib "TG21_TX_Ma tran phimPrjPcb") (part "1210 22uF 25V X7R"))
    )
    (comp (ref "C33")
      (value "22uF/25V")
      (footprint "1210 CAPACITOR")
      (description "22uF ±10% 25V Ceramic Capacitor X7R 1210")
      (fields
        (field (name "MANUFACTURER") "Samsung Electro-Mechanics")
        (field (name "MFR. PART #") "CL32B226KAJNNNE")
        (field (name "PACKAGE") "1210")
      )
      (libsource (lib "TG21_TX_Ma tran phimPrjPcb") (part "1210 22uF 25V X7R"))
    )
    (comp (ref "C34")
      (value "100nF")
      (footprint "0603 MLCC")
      (description "100nF ±10% 50V Ceramic Capacitor X7R 0603")
      (fields
        (field (name "MANUFACTURER") "YAGEO")
        (field (name "MFR. PART #") "CC0603KRX7R9BB104")
        (field (name "PACKAGE") "0603")
      )
      (libsource (lib "TG21_TX_Ma tran phimPrjPcb") (part "0603 100nF"))
    )
    (comp (ref "C35")
      (value "100nF")
      (footprint "0603 MLCC")
      (description "100nF ±10% 50V Ceramic Capacitor X7R 0603")
      (fields
        (field (name "MANUFACTURER") "YAGEO")
        (field (name "MFR. PART #") "CC0603KRX7R9BB104")
        (field (name "PACKAGE") "0603")
      )
      (libsource (lib "TG21_TX_Ma tran phimPrjPcb") (part "0603 100nF"))
    )
    (comp (ref "C36")
      (value "100nF")
      (footprint "0603 MLCC")
      (description "100nF ±10% 50V Ceramic Capacitor X7R 0603")
      (fields
        (field (name "MANUFACTURER") "YAGEO")
        (field (name "MFR. PART #") "CC0603KRX7R9BB104")
        (field (name "PACKAGE") "0603")
      )
      (libsource (lib "TG21_TX_Ma tran phimPrjPcb") (part "0603 100nF"))
    )
    (comp (ref "C37")
      (value "100nF")
      (footprint "0603 MLCC")
      (description "100nF ±10% 50V Ceramic Capacitor X7R 0603")
      (fields
        (field (name "MANUFACTURER") "YAGEO")
        (field (name "MFR. PART #") "CC0603KRX7R9BB104")
        (field (name "PACKAGE") "0603")
      )
      (libsource (lib "TG21_TX_Ma tran phimPrjPcb") (part "0603 100nF"))
    )
    (comp (ref "C38")
      (value "100nF")
      (footprint "0603 MLCC")
      (description "100nF ±10% 50V Ceramic Capacitor X7R 0603")
      (fields
        (field (name "MANUFACTURER") "YAGEO")
        (field (name "MFR. PART #") "CC0603KRX7R9BB104")
        (field (name "PACKAGE") "0603")
      )
      (libsource (lib "TG21_TX_Ma tran phimPrjPcb") (part "0603 100nF"))
    )
    (comp (ref "C39")
      (value "100nF")
      (footprint "0603 MLCC")
      (description "100nF ±10% 50V Ceramic Capacitor X7R 0603")
      (fields
        (field (name "MANUFACTURER") "YAGEO")
        (field (name "MFR. PART #") "CC0603KRX7R9BB104")
        (field (name "PACKAGE") "0603")
      )
      (libsource (lib "TG21_TX_Ma tran phimPrjPcb") (part "0603 100nF"))
    )
    (comp (ref "C40")
      (value "100nF")
      (footprint "0603 MLCC")
      (description "100nF ±10% 50V Ceramic Capacitor X7R 0603")
      (fields
        (field (name "MANUFACTURER") "YAGEO")
        (field (name "MFR. PART #") "CC0603KRX7R9BB104")
        (field (name "PACKAGE") "0603")
      )
      (libsource (lib "TG21_TX_Ma tran phimPrjPcb") (part "0603 100nF"))
    )
    (comp (ref "C41")
      (value "100nF")
      (footprint "0603 MLCC")
      (description "100nF ±10% 50V Ceramic Capacitor X7R 0603")
      (fields
        (field (name "MANUFACTURER") "YAGEO")
        (field (name "MFR. PART #") "CC0603KRX7R9BB104")
        (field (name "PACKAGE") "0603")
      )
      (libsource (lib "TG21_SCHLib") (part "0603 100nF"))
    )
    (comp (ref "C42")
      (value "100nF")
      (footprint "0603 MLCC")
      (description "100nF ±10% 50V Ceramic Capacitor X7R 0603")
      (fields
        (field (name "MANUFACTURER") "YAGEO")
        (field (name "MFR. PART #") "CC0603KRX7R9BB104")
        (field (name "PACKAGE") "0603")
      )
      (libsource (lib "TG21_SCHLib") (part "0603 100nF"))
    )
    (comp (ref "H1")
      (value "XY-XH2.54-4PZZ")
      (footprint "XH2.54 - 4PZZ")
      (description "XH 1 4P -25℃~+85℃ 2.54mm 4 2A 250V 1x4P Through Hole,P=2.54mm Headers, Male Pins RoHS")
      (fields (field (name "MANUFACTURER") "XYECONN") (field (name "LCSC PART #") "C53201003"))
      (libsource (lib "TG21_SCHLib") (part "XH2.54 4PZZ"))
    )
    (comp (ref "H2")
      (value "XY-XH2.54-4PZZ")
      (footprint "XH2.54 - 4PZZ")
      (description "XH 1 4P -25℃~+85℃ 2.54mm 4 2A 250V 1x4P Through Hole,P=2.54mm Headers, Male Pins RoHS")
      (fields (field (name "MANUFACTURER") "XYECONN") (field (name "LCSC PART #") "C53201003"))
      (libsource (lib "TG21_SCHLib") (part "XH2.54 4PZZ"))
    )
    (comp (ref "H3")
      (value "XY-XH2.54-4PZZ")
      (footprint "XH2.54 - 4PZZ")
      (description "XH 1 4P -25℃~+85℃ 2.54mm 4 2A 250V 1x4P Through Hole,P=2.54mm Headers, Male Pins RoHS")
      (fields (field (name "MANUFACTURER") "XYECONN") (field (name "LCSC PART #") "C53201003"))
      (libsource (lib "TG21_SCHLib") (part "XH2.54 4PZZ"))
    )
    (comp (ref "Q1")
      (value "SI2308A")
      (footprint "SOT23_HVT")
      (description "N-Channel 60V 3A 1.25W Surface Mount SOT-23")
      (fields (field (name "MANUFACTURER") "UMW") (field (name "LCSC PART #") "C347491"))
      (libsource (lib "TG21_TX_Ma tran phimPrjPcb") (part "SI2308A"))
    )
    (comp (ref "Q2")
      (value "SI2308A")
      (footprint "SOT23_HVT")
      (description "N-Channel 60V 3A 1.25W Surface Mount SOT-23")
      (fields (field (name "MANUFACTURER") "UMW") (field (name "LCSC PART #") "C347491"))
      (libsource (lib "TG21_TX_Ma tran phimPrjPcb") (part "SI2308A"))
    )
    (comp (ref "Q3")
      (value "SI2308A")
      (footprint "SOT23_HVT")
      (description "N-Channel 60V 3A 1.25W Surface Mount SOT-23")
      (fields (field (name "MANUFACTURER") "UMW") (field (name "LCSC PART #") "C347491"))
      (libsource (lib "TG21_TX_Ma tran phimPrjPcb") (part "SI2308A"))
    )
    (comp (ref "Q4")
      (value "SI2308A")
      (footprint "SOT23_HVT")
      (description "N-Channel 60V 3A 1.25W Surface Mount SOT-23")
      (fields (field (name "MANUFACTURER") "UMW") (field (name "LCSC PART #") "C347491"))
      (libsource (lib "TG21_TX_Ma tran phimPrjPcb") (part "SI2308A"))
    )
    (comp (ref "Q5")
      (value "SI2308A")
      (footprint "SOT23_HVT")
      (description "N-Channel 60V 3A 1.25W Surface Mount SOT-23")
      (fields (field (name "MANUFACTURER") "UMW") (field (name "LCSC PART #") "C347491"))
      (libsource (lib "TG21_TX_Ma tran phimPrjPcb") (part "SI2308A"))
    )
    (comp (ref "Q6")
      (value "SI2308A")
      (footprint "SOT23_HVT")
      (description "N-Channel 60V 3A 1.25W Surface Mount SOT-23")
      (fields (field (name "MANUFACTURER") "UMW") (field (name "LCSC PART #") "C347491"))
      (libsource (lib "TG21_TX_Ma tran phimPrjPcb") (part "SI2308A"))
    )
    (comp (ref "Q7")
      (value "SI2308A")
      (footprint "SOT23_HVT")
      (description "N-Channel 60V 3A 1.25W Surface Mount SOT-23")
      (fields (field (name "MANUFACTURER") "UMW") (field (name "LCSC PART #") "C347491"))
      (libsource (lib "TG21_TX_Ma tran phimPrjPcb") (part "SI2308A"))
    )
    (comp (ref "Q8")
      (value "SI2308A")
      (footprint "SOT23_HVT")
      (description "N-Channel 60V 3A 1.25W Surface Mount SOT-23")
      (fields (field (name "MANUFACTURER") "UMW") (field (name "LCSC PART #") "C347491"))
      (libsource (lib "TG21_TX_Ma tran phimPrjPcb") (part "SI2308A"))
    )
    (comp (ref "Q9")
      (value "SI2308A")
      (footprint "SOT23_HVT")
      (description "N-Channel 60V 3A 1.25W Surface Mount SOT-23")
      (fields (field (name "MANUFACTURER") "UMW") (field (name "LCSC PART #") "C347491"))
      (libsource (lib "TG21_TX_Ma tran phimPrjPcb") (part "SI2308A"))
    )
    (comp (ref "Q10")
      (value "SI2308A")
      (footprint "SOT23_HVT")
      (description "N-Channel 60V 3A 1.25W Surface Mount SOT-23")
      (fields (field (name "MANUFACTURER") "UMW") (field (name "LCSC PART #") "C347491"))
      (libsource (lib "TG21_TX_Ma tran phimPrjPcb") (part "SI2308A"))
    )
    (comp (ref "Q11")
      (value "SI2308A")
      (footprint "SOT23_HVT")
      (description "N-Channel 60V 3A 1.25W Surface Mount SOT-23")
      (fields (field (name "MANUFACTURER") "UMW") (field (name "LCSC PART #") "C347491"))
      (libsource (lib "TG21_TX_Ma tran phimPrjPcb") (part "SI2308A"))
    )
    (comp (ref "Q12")
      (value "SI2308A")
      (footprint "SOT23_HVT")
      (description "N-Channel 60V 3A 1.25W Surface Mount SOT-23")
      (fields (field (name "MANUFACTURER") "UMW") (field (name "LCSC PART #") "C347491"))
      (libsource (lib "TG21_TX_Ma tran phimPrjPcb") (part "SI2308A"))
    )
    (comp (ref "Q13")
      (value "SI2308A")
      (footprint "SOT23_HVT")
      (description "N-Channel 60V 3A 1.25W Surface Mount SOT-23")
      (fields (field (name "MANUFACTURER") "UMW") (field (name "LCSC PART #") "C347491"))
      (libsource (lib "TG21_TX_Ma tran phimPrjPcb") (part "SI2308A"))
    )
    (comp (ref "Q14")
      (value "SI2308A")
      (footprint "SOT23_HVT")
      (description "N-Channel 60V 3A 1.25W Surface Mount SOT-23")
      (fields (field (name "MANUFACTURER") "UMW") (field (name "LCSC PART #") "C347491"))
      (libsource (lib "TG21_TX_Ma tran phimPrjPcb") (part "SI2308A"))
    )
    (comp (ref "Q15")
      (value "SI2308A")
      (footprint "SOT23_HVT")
      (description "N-Channel 60V 3A 1.25W Surface Mount SOT-23")
      (fields (field (name "MANUFACTURER") "UMW") (field (name "LCSC PART #") "C347491"))
      (libsource (lib "TG21_TX_Ma tran phimPrjPcb") (part "SI2308A"))
    )
    (comp (ref "Q16")
      (value "SI2308A")
      (footprint "SOT23_HVT")
      (description "N-Channel 60V 3A 1.25W Surface Mount SOT-23")
      (fields (field (name "MANUFACTURER") "UMW") (field (name "LCSC PART #") "C347491"))
      (libsource (lib "TG21_TX_Ma tran phimPrjPcb") (part "SI2308A"))
    )
    (comp (ref "Q17")
      (value "SI2308A")
      (footprint "SOT23_HVT")
      (description "N-Channel 60V 3A 1.25W Surface Mount SOT-23")
      (fields (field (name "MANUFACTURER") "UMW") (field (name "LCSC PART #") "C347491"))
      (libsource (lib "TG21_TX_Ma tran phimPrjPcb") (part "SI2308A"))
    )
    (comp (ref "Q18")
      (value "SI2308A")
      (footprint "SOT23_HVT")
      (description "N-Channel 60V 3A 1.25W Surface Mount SOT-23")
      (fields (field (name "MANUFACTURER") "UMW") (field (name "LCSC PART #") "C347491"))
      (libsource (lib "TG21_TX_Ma tran phimPrjPcb") (part "SI2308A"))
    )
    (comp (ref "Q19")
      (value "SI2308A")
      (footprint "SOT23_HVT")
      (description "N-Channel 60V 3A 1.25W Surface Mount SOT-23")
      (fields (field (name "MANUFACTURER") "UMW") (field (name "LCSC PART #") "C347491"))
      (libsource (lib "TG21_TX_Ma tran phimPrjPcb") (part "SI2308A"))
    )
    (comp (ref "Q20")
      (value "SI2308A")
      (footprint "SOT23_HVT")
      (description "N-Channel 60V 3A 1.25W Surface Mount SOT-23")
      (fields (field (name "MANUFACTURER") "UMW") (field (name "LCSC PART #") "C347491"))
      (libsource (lib "TG21_TX_Ma tran phimPrjPcb") (part "SI2308A"))
    )
    (comp (ref "Q21")
      (value "SI2308A")
      (footprint "SOT23_HVT")
      (description "N-Channel 60V 3A 1.25W Surface Mount SOT-23")
      (fields (field (name "MANUFACTURER") "UMW") (field (name "LCSC PART #") "C347491"))
      (libsource (lib "TG21_TX_Ma tran phimPrjPcb") (part "SI2308A"))
    )
    (comp (ref "Q22")
      (value "SI2308A")
      (footprint "SOT23_HVT")
      (description "N-Channel 60V 3A 1.25W Surface Mount SOT-23")
      (fields (field (name "MANUFACTURER") "UMW") (field (name "LCSC PART #") "C347491"))
      (libsource (lib "TG21_TX_Ma tran phimPrjPcb") (part "SI2308A"))
    )
    (comp (ref "Q23")
      (value "SI2308A")
      (footprint "SOT23_HVT")
      (description "N-Channel 60V 3A 1.25W Surface Mount SOT-23")
      (fields (field (name "MANUFACTURER") "UMW") (field (name "LCSC PART #") "C347491"))
      (libsource (lib "TG21_TX_Ma tran phimPrjPcb") (part "SI2308A"))
    )
    (comp (ref "Q24")
      (value "SI2308A")
      (footprint "SOT23_HVT")
      (description "N-Channel 60V 3A 1.25W Surface Mount SOT-23")
      (fields (field (name "MANUFACTURER") "UMW") (field (name "LCSC PART #") "C347491"))
      (libsource (lib "TG21_TX_Ma tran phimPrjPcb") (part "SI2308A"))
    )
    (comp (ref "Q25")
      (value "SI2308A")
      (footprint "SOT23_HVT")
      (description "N-Channel 60V 3A 1.25W Surface Mount SOT-23")
      (fields (field (name "MANUFACTURER") "UMW") (field (name "LCSC PART #") "C347491"))
      (libsource (lib "TG21_TX_Ma tran phimPrjPcb") (part "SI2308A"))
    )
    (comp (ref "Q26")
      (value "SI2308A")
      (footprint "SOT23_HVT")
      (description "N-Channel 60V 3A 1.25W Surface Mount SOT-23")
      (fields (field (name "MANUFACTURER") "UMW") (field (name "LCSC PART #") "C347491"))
      (libsource (lib "TG21_TX_Ma tran phimPrjPcb") (part "SI2308A"))
    )
    (comp (ref "Q27")
      (value "SI2308A")
      (footprint "SOT23_HVT")
      (description "N-Channel 60V 3A 1.25W Surface Mount SOT-23")
      (fields (field (name "MANUFACTURER") "UMW") (field (name "LCSC PART #") "C347491"))
      (libsource (lib "TG21_TX_Ma tran phimPrjPcb") (part "SI2308A"))
    )
    (comp (ref "Q28")
      (value "SI2308A")
      (footprint "SOT23_HVT")
      (description "N-Channel 60V 3A 1.25W Surface Mount SOT-23")
      (fields (field (name "MANUFACTURER") "UMW") (field (name "LCSC PART #") "C347491"))
      (libsource (lib "TG21_TX_Ma tran phimPrjPcb") (part "SI2308A"))
    )
    (comp (ref "Q29")
      (value "SI2308A")
      (footprint "SOT23_HVT")
      (description "N-Channel 60V 3A 1.25W Surface Mount SOT-23")
      (fields (field (name "MANUFACTURER") "UMW") (field (name "LCSC PART #") "C347491"))
      (libsource (lib "TG21_TX_Ma tran phimPrjPcb") (part "SI2308A"))
    )
    (comp (ref "Q30")
      (value "SI2308A")
      (footprint "SOT23_HVT")
      (description "N-Channel 60V 3A 1.25W Surface Mount SOT-23")
      (fields (field (name "MANUFACTURER") "UMW") (field (name "LCSC PART #") "C347491"))
      (libsource (lib "TG21_TX_Ma tran phimPrjPcb") (part "SI2308A"))
    )
    (comp (ref "Q31")
      (value "SI2308A")
      (footprint "SOT23_HVT")
      (description "N-Channel 60V 3A 1.25W Surface Mount SOT-23")
      (fields (field (name "MANUFACTURER") "UMW") (field (name "LCSC PART #") "C347491"))
      (libsource (lib "TG21_TX_Ma tran phimPrjPcb") (part "SI2308A"))
    )
    (comp (ref "Q32")
      (value "SI2308A")
      (footprint "SOT23_HVT")
      (description "N-Channel 60V 3A 1.25W Surface Mount SOT-23")
      (fields (field (name "MANUFACTURER") "UMW") (field (name "LCSC PART #") "C347491"))
      (libsource (lib "TG21_TX_Ma tran phimPrjPcb") (part "SI2308A"))
    )
    (comp (ref "Q33")
      (value "SI2308A")
      (footprint "SOT23_HVT")
      (description "N-Channel 60V 3A 1.25W Surface Mount SOT-23")
      (fields (field (name "MANUFACTURER") "UMW") (field (name "LCSC PART #") "C347491"))
      (libsource (lib "TG21_TX_Ma tran phimPrjPcb") (part "SI2308A"))
    )
    (comp (ref "Q34")
      (value "SI2308A")
      (footprint "SOT23_HVT")
      (description "N-Channel 60V 3A 1.25W Surface Mount SOT-23")
      (fields (field (name "MANUFACTURER") "UMW") (field (name "LCSC PART #") "C347491"))
      (libsource (lib "TG21_TX_Ma tran phimPrjPcb") (part "SI2308A"))
    )
    (comp (ref "Q35")
      (value "SI2308A")
      (footprint "SOT23_HVT")
      (description "N-Channel 60V 3A 1.25W Surface Mount SOT-23")
      (fields (field (name "MANUFACTURER") "UMW") (field (name "LCSC PART #") "C347491"))
      (libsource (lib "TG21_TX_Ma tran phimPrjPcb") (part "SI2308A"))
    )
    (comp (ref "Q36")
      (value "SI2308A")
      (footprint "SOT23_HVT")
      (description "N-Channel 60V 3A 1.25W Surface Mount SOT-23")
      (fields (field (name "MANUFACTURER") "UMW") (field (name "LCSC PART #") "C347491"))
      (libsource (lib "TG21_TX_Ma tran phimPrjPcb") (part "SI2308A"))
    )
    (comp (ref "Q37")
      (value "SI2308A")
      (footprint "SOT23_HVT")
      (description "N-Channel 60V 3A 1.25W Surface Mount SOT-23")
      (fields (field (name "MANUFACTURER") "UMW") (field (name "LCSC PART #") "C347491"))
      (libsource (lib "TG21_TX_Ma tran phimPrjPcb") (part "SI2308A"))
    )
    (comp (ref "Q38")
      (value "SI2308A")
      (footprint "SOT23_HVT")
      (description "N-Channel 60V 3A 1.25W Surface Mount SOT-23")
      (fields (field (name "MANUFACTURER") "UMW") (field (name "LCSC PART #") "C347491"))
      (libsource (lib "TG21_TX_Ma tran phimPrjPcb") (part "SI2308A"))
    )
    (comp (ref "Q39")
      (value "SI2308A")
      (footprint "SOT23_HVT")
      (description "N-Channel 60V 3A 1.25W Surface Mount SOT-23")
      (fields (field (name "MANUFACTURER") "UMW") (field (name "LCSC PART #") "C347491"))
      (libsource (lib "TG21_TX_Ma tran phimPrjPcb") (part "SI2308A"))
    )
    (comp (ref "Q40")
      (value "SI2308A")
      (footprint "SOT23_HVT")
      (description "N-Channel 60V 3A 1.25W Surface Mount SOT-23")
      (fields (field (name "MANUFACTURER") "UMW") (field (name "LCSC PART #") "C347491"))
      (libsource (lib "TG21_TX_Ma tran phimPrjPcb") (part "SI2308A"))
    )
    (comp (ref "Q41")
      (value "SI2308A")
      (footprint "SOT23_HVT")
      (description "N-Channel 60V 3A 1.25W Surface Mount SOT-23")
      (fields (field (name "MANUFACTURER") "UMW") (field (name "LCSC PART #") "C347491"))
      (libsource (lib "TG21_TX_Ma tran phimPrjPcb") (part "SI2308A"))
    )
    (comp (ref "Q42")
      (value "SI2308A")
      (footprint "SOT23_HVT")
      (description "N-Channel 60V 3A 1.25W Surface Mount SOT-23")
      (fields (field (name "MANUFACTURER") "UMW") (field (name "LCSC PART #") "C347491"))
      (libsource (lib "TG21_TX_Ma tran phimPrjPcb") (part "SI2308A"))
    )
    (comp (ref "Q43")
      (value "SI2308A")
      (footprint "SOT23_HVT")
      (description "N-Channel 60V 3A 1.25W Surface Mount SOT-23")
      (fields (field (name "MANUFACTURER") "UMW") (field (name "LCSC PART #") "C347491"))
      (libsource (lib "TG21_TX_Ma tran phimPrjPcb") (part "SI2308A"))
    )
    (comp (ref "Q44")
      (value "SI2308A")
      (footprint "SOT23_HVT")
      (description "N-Channel 60V 3A 1.25W Surface Mount SOT-23")
      (fields (field (name "MANUFACTURER") "UMW") (field (name "LCSC PART #") "C347491"))
      (libsource (lib "TG21_TX_Ma tran phimPrjPcb") (part "SI2308A"))
    )
    (comp (ref "Q45")
      (value "SI2308A")
      (footprint "SOT23_HVT")
      (description "N-Channel 60V 3A 1.25W Surface Mount SOT-23")
      (fields (field (name "MANUFACTURER") "UMW") (field (name "LCSC PART #") "C347491"))
      (libsource (lib "TG21_TX_Ma tran phimPrjPcb") (part "SI2308A"))
    )
    (comp (ref "Q46")
      (value "SI2308A")
      (footprint "SOT23_HVT")
      (description "N-Channel 60V 3A 1.25W Surface Mount SOT-23")
      (fields (field (name "MANUFACTURER") "UMW") (field (name "LCSC PART #") "C347491"))
      (libsource (lib "TG21_TX_Ma tran phimPrjPcb") (part "SI2308A"))
    )
    (comp (ref "Q47")
      (value "SI2308A")
      (footprint "SOT23_HVT")
      (description "N-Channel 60V 3A 1.25W Surface Mount SOT-23")
      (fields (field (name "MANUFACTURER") "UMW") (field (name "LCSC PART #") "C347491"))
      (libsource (lib "TG21_TX_Ma tran phimPrjPcb") (part "SI2308A"))
    )
    (comp (ref "Q48")
      (value "SI2308A")
      (footprint "SOT23_HVT")
      (description "N-Channel 60V 3A 1.25W Surface Mount SOT-23")
      (fields (field (name "MANUFACTURER") "UMW") (field (name "LCSC PART #") "C347491"))
      (libsource (lib "TG21_TX_Ma tran phimPrjPcb") (part "SI2308A"))
    )
    (comp (ref "Q49")
      (value "SI2308A")
      (footprint "SOT23_HVT")
      (description "N-Channel 60V 3A 1.25W Surface Mount SOT-23")
      (fields (field (name "MANUFACTURER") "UMW") (field (name "LCSC PART #") "C347491"))
      (libsource (lib "TG21_TX_Ma tran phimPrjPcb") (part "SI2308A"))
    )
    (comp (ref "Q50")
      (value "SI2308A")
      (footprint "SOT23_HVT")
      (description "N-Channel 60V 3A 1.25W Surface Mount SOT-23")
      (fields (field (name "MANUFACTURER") "UMW") (field (name "LCSC PART #") "C347491"))
      (libsource (lib "TG21_TX_Ma tran phimPrjPcb") (part "SI2308A"))
    )
    (comp (ref "Q51")
      (value "SI2308A")
      (footprint "SOT23_HVT")
      (description "N-Channel 60V 3A 1.25W Surface Mount SOT-23")
      (fields (field (name "MANUFACTURER") "UMW") (field (name "LCSC PART #") "C347491"))
      (libsource (lib "TG21_TX_Ma tran phimPrjPcb") (part "SI2308A"))
    )
    (comp (ref "Q52")
      (value "SI2308A")
      (footprint "SOT23_HVT")
      (description "N-Channel 60V 3A 1.25W Surface Mount SOT-23")
      (fields (field (name "MANUFACTURER") "UMW") (field (name "LCSC PART #") "C347491"))
      (libsource (lib "TG21_TX_Ma tran phimPrjPcb") (part "SI2308A"))
    )
    (comp (ref "Q53")
      (value "SI2308A")
      (footprint "SOT23_HVT")
      (description "N-Channel 60V 3A 1.25W Surface Mount SOT-23")
      (fields (field (name "MANUFACTURER") "UMW") (field (name "LCSC PART #") "C347491"))
      (libsource (lib "TG21_TX_Ma tran phimPrjPcb") (part "SI2308A"))
    )
    (comp (ref "Q54")
      (value "SI2308A")
      (footprint "SOT23_HVT")
      (description "N-Channel 60V 3A 1.25W Surface Mount SOT-23")
      (fields (field (name "MANUFACTURER") "UMW") (field (name "LCSC PART #") "C347491"))
      (libsource (lib "TG21_TX_Ma tran phimPrjPcb") (part "SI2308A"))
    )
    (comp (ref "Q55")
      (value "SI2308A")
      (footprint "SOT23_HVT")
      (description "N-Channel 60V 3A 1.25W Surface Mount SOT-23")
      (fields (field (name "MANUFACTURER") "UMW") (field (name "LCSC PART #") "C347491"))
      (libsource (lib "TG21_TX_Ma tran phimPrjPcb") (part "SI2308A"))
    )
    (comp (ref "Q56")
      (value "SI2308A")
      (footprint "SOT23_HVT")
      (description "N-Channel 60V 3A 1.25W Surface Mount SOT-23")
      (fields (field (name "MANUFACTURER") "UMW") (field (name "LCSC PART #") "C347491"))
      (libsource (lib "TG21_TX_Ma tran phimPrjPcb") (part "SI2308A"))
    )
    (comp (ref "Q57")
      (value "SI2308A")
      (footprint "SOT23_HVT")
      (description "N-Channel 60V 3A 1.25W Surface Mount SOT-23")
      (fields (field (name "MANUFACTURER") "UMW") (field (name "LCSC PART #") "C347491"))
      (libsource (lib "TG21_TX_Ma tran phimPrjPcb") (part "SI2308A"))
    )
    (comp (ref "Q58")
      (value "SI2308A")
      (footprint "SOT23_HVT")
      (description "N-Channel 60V 3A 1.25W Surface Mount SOT-23")
      (fields (field (name "MANUFACTURER") "UMW") (field (name "LCSC PART #") "C347491"))
      (libsource (lib "TG21_TX_Ma tran phimPrjPcb") (part "SI2308A"))
    )
    (comp (ref "Q59")
      (value "SI2308A")
      (footprint "SOT23_HVT")
      (description "N-Channel 60V 3A 1.25W Surface Mount SOT-23")
      (fields (field (name "MANUFACTURER") "UMW") (field (name "LCSC PART #") "C347491"))
      (libsource (lib "TG21_TX_Ma tran phimPrjPcb") (part "SI2308A"))
    )
    (comp (ref "Q60")
      (value "SI2308A")
      (footprint "SOT23_HVT")
      (description "N-Channel 60V 3A 1.25W Surface Mount SOT-23")
      (fields (field (name "MANUFACTURER") "UMW") (field (name "LCSC PART #") "C347491"))
      (libsource (lib "TG21_TX_Ma tran phimPrjPcb") (part "SI2308A"))
    )
    (comp (ref "Q61")
      (value "SI2308A")
      (footprint "SOT23_HVT")
      (description "N-Channel 60V 3A 1.25W Surface Mount SOT-23")
      (fields (field (name "MANUFACTURER") "UMW") (field (name "LCSC PART #") "C347491"))
      (libsource (lib "TG21_TX_Ma tran phimPrjPcb") (part "SI2308A"))
    )
    (comp (ref "Q62")
      (value "SI2308A")
      (footprint "SOT23_HVT")
      (description "N-Channel 60V 3A 1.25W Surface Mount SOT-23")
      (fields (field (name "MANUFACTURER") "UMW") (field (name "LCSC PART #") "C347491"))
      (libsource (lib "TG21_TX_Ma tran phimPrjPcb") (part "SI2308A"))
    )
    (comp (ref "Q63")
      (value "SI2308A")
      (footprint "SOT23_HVT")
      (description "N-Channel 60V 3A 1.25W Surface Mount SOT-23")
      (fields (field (name "MANUFACTURER") "UMW") (field (name "LCSC PART #") "C347491"))
      (libsource (lib "TG21_TX_Ma tran phimPrjPcb") (part "SI2308A"))
    )
    (comp (ref "Q64")
      (value "SI2308A")
      (footprint "SOT23_HVT")
      (description "N-Channel 60V 3A 1.25W Surface Mount SOT-23")
      (fields (field (name "MANUFACTURER") "UMW") (field (name "LCSC PART #") "C347491"))
      (libsource (lib "TG21_TX_Ma tran phimPrjPcb") (part "SI2308A"))
    )
    (comp (ref "Q65")
      (value "SI2308A")
      (footprint "SOT23_HVT")
      (description "N-Channel 60V 3A 1.25W Surface Mount SOT-23")
      (fields (field (name "MANUFACTURER") "UMW") (field (name "LCSC PART #") "C347491"))
      (libsource (lib "TG21_TX_Ma tran phimPrjPcb") (part "SI2308A"))
    )
    (comp (ref "Q66")
      (value "SI2308A")
      (footprint "SOT23_HVT")
      (description "N-Channel 60V 3A 1.25W Surface Mount SOT-23")
      (fields (field (name "MANUFACTURER") "UMW") (field (name "LCSC PART #") "C347491"))
      (libsource (lib "TG21_TX_Ma tran phimPrjPcb") (part "SI2308A"))
    )
    (comp (ref "Q67")
      (value "SI2308A")
      (footprint "SOT23_HVT")
      (description "N-Channel 60V 3A 1.25W Surface Mount SOT-23")
      (fields (field (name "MANUFACTURER") "UMW") (field (name "LCSC PART #") "C347491"))
      (libsource (lib "TG21_TX_Ma tran phimPrjPcb") (part "SI2308A"))
    )
    (comp (ref "Q68")
      (value "SI2308A")
      (footprint "SOT23_HVT")
      (description "N-Channel 60V 3A 1.25W Surface Mount SOT-23")
      (fields (field (name "MANUFACTURER") "UMW") (field (name "LCSC PART #") "C347491"))
      (libsource (lib "TG21_TX_Ma tran phimPrjPcb") (part "SI2308A"))
    )
    (comp (ref "Q69")
      (value "SI2308A")
      (footprint "SOT23_HVT")
      (description "N-Channel 60V 3A 1.25W Surface Mount SOT-23")
      (fields (field (name "MANUFACTURER") "UMW") (field (name "LCSC PART #") "C347491"))
      (libsource (lib "TG21_TX_Ma tran phimPrjPcb") (part "SI2308A"))
    )
    (comp (ref "Q70")
      (value "SI2308A")
      (footprint "SOT23_HVT")
      (description "N-Channel 60V 3A 1.25W Surface Mount SOT-23")
      (fields (field (name "MANUFACTURER") "UMW") (field (name "LCSC PART #") "C347491"))
      (libsource (lib "TG21_TX_Ma tran phimPrjPcb") (part "SI2308A"))
    )
    (comp (ref "Q71")
      (value "SI2308A")
      (footprint "SOT23_HVT")
      (description "N-Channel 60V 3A 1.25W Surface Mount SOT-23")
      (fields (field (name "MANUFACTURER") "UMW") (field (name "LCSC PART #") "C347491"))
      (libsource (lib "TG21_TX_Ma tran phimPrjPcb") (part "SI2308A"))
    )
    (comp (ref "Q72")
      (value "SI2308A")
      (footprint "SOT23_HVT")
      (description "N-Channel 60V 3A 1.25W Surface Mount SOT-23")
      (fields (field (name "MANUFACTURER") "UMW") (field (name "LCSC PART #") "C347491"))
      (libsource (lib "TG21_TX_Ma tran phimPrjPcb") (part "SI2308A"))
    )
    (comp (ref "Q73")
      (value "SI2308A")
      (footprint "SOT23_HVT")
      (description "N-Channel 60V 3A 1.25W Surface Mount SOT-23")
      (fields (field (name "MANUFACTURER") "UMW") (field (name "LCSC PART #") "C347491"))
      (libsource (lib "TG21_TX_Ma tran phimPrjPcb") (part "SI2308A"))
    )
    (comp (ref "Q74")
      (value "SI2308A")
      (footprint "SOT23_HVT")
      (description "N-Channel 60V 3A 1.25W Surface Mount SOT-23")
      (fields (field (name "MANUFACTURER") "UMW") (field (name "LCSC PART #") "C347491"))
      (libsource (lib "TG21_TX_Ma tran phimPrjPcb") (part "SI2308A"))
    )
    (comp (ref "Q75")
      (value "SI2308A")
      (footprint "SOT23_HVT")
      (description "N-Channel 60V 3A 1.25W Surface Mount SOT-23")
      (fields (field (name "MANUFACTURER") "UMW") (field (name "LCSC PART #") "C347491"))
      (libsource (lib "TG21_TX_Ma tran phimPrjPcb") (part "SI2308A"))
    )
    (comp (ref "Q76")
      (value "SI2308A")
      (footprint "SOT23_HVT")
      (description "N-Channel 60V 3A 1.25W Surface Mount SOT-23")
      (fields (field (name "MANUFACTURER") "UMW") (field (name "LCSC PART #") "C347491"))
      (libsource (lib "TG21_TX_Ma tran phimPrjPcb") (part "SI2308A"))
    )
    (comp (ref "Q77")
      (value "SI2308A")
      (footprint "SOT23_HVT")
      (description "N-Channel 60V 3A 1.25W Surface Mount SOT-23")
      (fields (field (name "MANUFACTURER") "UMW") (field (name "LCSC PART #") "C347491"))
      (libsource (lib "TG21_TX_Ma tran phimPrjPcb") (part "SI2308A"))
    )
    (comp (ref "Q78")
      (value "SI2308A")
      (footprint "SOT23_HVT")
      (description "N-Channel 60V 3A 1.25W Surface Mount SOT-23")
      (fields (field (name "MANUFACTURER") "UMW") (field (name "LCSC PART #") "C347491"))
      (libsource (lib "TG21_TX_Ma tran phimPrjPcb") (part "SI2308A"))
    )
    (comp (ref "Q79")
      (value "SI2308A")
      (footprint "SOT23_HVT")
      (description "N-Channel 60V 3A 1.25W Surface Mount SOT-23")
      (fields (field (name "MANUFACTURER") "UMW") (field (name "LCSC PART #") "C347491"))
      (libsource (lib "TG21_TX_Ma tran phimPrjPcb") (part "SI2308A"))
    )
    (comp (ref "Q80")
      (value "SI2308A")
      (footprint "SOT23_HVT")
      (description "N-Channel 60V 3A 1.25W Surface Mount SOT-23")
      (fields (field (name "MANUFACTURER") "UMW") (field (name "LCSC PART #") "C347491"))
      (libsource (lib "TG21_TX_Ma tran phimPrjPcb") (part "SI2308A"))
    )
    (comp (ref "Q81")
      (value "SI2308A")
      (footprint "SOT23_HVT")
      (description "N-Channel 60V 3A 1.25W Surface Mount SOT-23")
      (fields (field (name "MANUFACTURER") "UMW") (field (name "LCSC PART #") "C347491"))
      (libsource (lib "TG21_TX_Ma tran phimPrjPcb") (part "SI2308A"))
    )
    (comp (ref "Q82")
      (value "SI2308A")
      (footprint "SOT23_HVT")
      (description "N-Channel 60V 3A 1.25W Surface Mount SOT-23")
      (fields (field (name "MANUFACTURER") "UMW") (field (name "LCSC PART #") "C347491"))
      (libsource (lib "TG21_TX_Ma tran phimPrjPcb") (part "SI2308A"))
    )
    (comp (ref "Q83")
      (value "SI2308A")
      (footprint "SOT23_HVT")
      (description "N-Channel 60V 3A 1.25W Surface Mount SOT-23")
      (fields (field (name "MANUFACTURER") "UMW") (field (name "LCSC PART #") "C347491"))
      (libsource (lib "TG21_TX_Ma tran phimPrjPcb") (part "SI2308A"))
    )
    (comp (ref "Q84")
      (value "SI2308A")
      (footprint "SOT23_HVT")
      (description "N-Channel 60V 3A 1.25W Surface Mount SOT-23")
      (fields (field (name "MANUFACTURER") "UMW") (field (name "LCSC PART #") "C347491"))
      (libsource (lib "TG21_TX_Ma tran phimPrjPcb") (part "SI2308A"))
    )
    (comp (ref "Q85")
      (value "SI2308A")
      (footprint "SOT23_HVT")
      (description "N-Channel 60V 3A 1.25W Surface Mount SOT-23")
      (fields (field (name "MANUFACTURER") "UMW") (field (name "LCSC PART #") "C347491"))
      (libsource (lib "TG21_TX_Ma tran phimPrjPcb") (part "SI2308A"))
    )
    (comp (ref "Q86")
      (value "SI2308A")
      (footprint "SOT23_HVT")
      (description "N-Channel 60V 3A 1.25W Surface Mount SOT-23")
      (fields (field (name "MANUFACTURER") "UMW") (field (name "LCSC PART #") "C347491"))
      (libsource (lib "TG21_TX_Ma tran phimPrjPcb") (part "SI2308A"))
    )
    (comp (ref "Q87")
      (value "SI2308A")
      (footprint "SOT23_HVT")
      (description "N-Channel 60V 3A 1.25W Surface Mount SOT-23")
      (fields (field (name "MANUFACTURER") "UMW") (field (name "LCSC PART #") "C347491"))
      (libsource (lib "TG21_TX_Ma tran phimPrjPcb") (part "SI2308A"))
    )
    (comp (ref "Q88")
      (value "SI2308A")
      (footprint "SOT23_HVT")
      (description "N-Channel 60V 3A 1.25W Surface Mount SOT-23")
      (fields (field (name "MANUFACTURER") "UMW") (field (name "LCSC PART #") "C347491"))
      (libsource (lib "TG21_TX_Ma tran phimPrjPcb") (part "SI2308A"))
    )
    (comp (ref "Q89")
      (value "SI2308A")
      (footprint "SOT23_HVT")
      (description "N-Channel 60V 3A 1.25W Surface Mount SOT-23")
      (fields (field (name "MANUFACTURER") "UMW") (field (name "LCSC PART #") "C347491"))
      (libsource (lib "TG21_TX_Ma tran phimPrjPcb") (part "SI2308A"))
    )
    (comp (ref "Q90")
      (value "SI2308A")
      (footprint "SOT23_HVT")
      (description "N-Channel 60V 3A 1.25W Surface Mount SOT-23")
      (fields (field (name "MANUFACTURER") "UMW") (field (name "LCSC PART #") "C347491"))
      (libsource (lib "TG21_TX_Ma tran phimPrjPcb") (part "SI2308A"))
    )
    (comp (ref "Q91")
      (value "SI2308A")
      (footprint "SOT23_HVT")
      (description "N-Channel 60V 3A 1.25W Surface Mount SOT-23")
      (fields (field (name "MANUFACTURER") "UMW") (field (name "LCSC PART #") "C347491"))
      (libsource (lib "TG21_TX_Ma tran phimPrjPcb") (part "SI2308A"))
    )
    (comp (ref "R1")
      (value "220R")
      (footprint "0603 MLCC")
      (description "100mW 220Ω 75V Thick Film Resistor ±1% ±100ppm/℃ 0603 Chip Resistor - Surface Mount RoHS")
      (fields
        (field (name "MFR. PART #") "CRCW0603220RFKEAHP")
        (field (name "LCSC PART #") "C313707")
        (field (name "PACKAGE") "0603")
      )
      (libsource (lib "TG21_TX_Ma tran phimPrjPcb") (part "0603 220R"))
    )
    (comp (ref "R2")
      (value "220R")
      (footprint "0603 MLCC")
      (description "100mW 220Ω 75V Thick Film Resistor ±1% ±100ppm/℃ 0603 Chip Resistor - Surface Mount RoHS")
      (fields
        (field (name "MFR. PART #") "CRCW0603220RFKEAHP")
        (field (name "LCSC PART #") "C313707")
        (field (name "PACKAGE") "0603")
      )
      (libsource (lib "TG21_TX_Ma tran phimPrjPcb") (part "0603 220R"))
    )
    (comp (ref "R3")
      (value "220R")
      (footprint "0603 MLCC")
      (description "100mW 220Ω 75V Thick Film Resistor ±1% ±100ppm/℃ 0603 Chip Resistor - Surface Mount RoHS")
      (fields
        (field (name "MFR. PART #") "CRCW0603220RFKEAHP")
        (field (name "LCSC PART #") "C313707")
        (field (name "PACKAGE") "0603")
      )
      (libsource (lib "TG21_TX_Ma tran phimPrjPcb") (part "0603 220R"))
    )
    (comp (ref "R4")
      (value "220R")
      (footprint "0603 MLCC")
      (description "100mW 220Ω 75V Thick Film Resistor ±1% ±100ppm/℃ 0603 Chip Resistor - Surface Mount RoHS")
      (fields
        (field (name "MFR. PART #") "CRCW0603220RFKEAHP")
        (field (name "LCSC PART #") "C313707")
        (field (name "PACKAGE") "0603")
      )
      (libsource (lib "TG21_TX_Ma tran phimPrjPcb") (part "0603 220R"))
    )
    (comp (ref "R5")
      (value "220R")
      (footprint "0603 MLCC")
      (description "100mW 220Ω 75V Thick Film Resistor ±1% ±100ppm/℃ 0603 Chip Resistor - Surface Mount RoHS")
      (fields
        (field (name "MFR. PART #") "CRCW0603220RFKEAHP")
        (field (name "LCSC PART #") "C313707")
        (field (name "PACKAGE") "0603")
      )
      (libsource (lib "TG21_TX_Ma tran phimPrjPcb") (part "0603 220R"))
    )
    (comp (ref "R6")
      (value "220R")
      (footprint "0603 MLCC")
      (description "100mW 220Ω 75V Thick Film Resistor ±1% ±100ppm/℃ 0603 Chip Resistor - Surface Mount RoHS")
      (fields
        (field (name "MFR. PART #") "CRCW0603220RFKEAHP")
        (field (name "LCSC PART #") "C313707")
        (field (name "PACKAGE") "0603")
      )
      (libsource (lib "TG21_TX_Ma tran phimPrjPcb") (part "0603 220R"))
    )
    (comp (ref "R7")
      (value "220R")
      (footprint "0603 MLCC")
      (description "100mW 220Ω 75V Thick Film Resistor ±1% ±100ppm/℃ 0603 Chip Resistor - Surface Mount RoHS")
      (fields
        (field (name "MFR. PART #") "CRCW0603220RFKEAHP")
        (field (name "LCSC PART #") "C313707")
        (field (name "PACKAGE") "0603")
      )
      (libsource (lib "TG21_TX_Ma tran phimPrjPcb") (part "0603 220R"))
    )
    (comp (ref "R8")
      (value "220R")
      (footprint "0603 MLCC")
      (description "100mW 220Ω 75V Thick Film Resistor ±1% ±100ppm/℃ 0603 Chip Resistor - Surface Mount RoHS")
      (fields
        (field (name "MFR. PART #") "CRCW0603220RFKEAHP")
        (field (name "LCSC PART #") "C313707")
        (field (name "PACKAGE") "0603")
      )
      (libsource (lib "TG21_TX_Ma tran phimPrjPcb") (part "0603 220R"))
    )
    (comp (ref "R9")
      (value "220R")
      (footprint "0603 MLCC")
      (description "100mW 220Ω 75V Thick Film Resistor ±1% ±100ppm/℃ 0603 Chip Resistor - Surface Mount RoHS")
      (fields
        (field (name "MFR. PART #") "CRCW0603220RFKEAHP")
        (field (name "LCSC PART #") "C313707")
        (field (name "PACKAGE") "0603")
      )
      (libsource (lib "TG21_TX_Ma tran phimPrjPcb") (part "0603 220R"))
    )
    (comp (ref "R10")
      (value "220R")
      (footprint "0603 MLCC")
      (description "100mW 220Ω 75V Thick Film Resistor ±1% ±100ppm/℃ 0603 Chip Resistor - Surface Mount RoHS")
      (fields
        (field (name "MFR. PART #") "CRCW0603220RFKEAHP")
        (field (name "LCSC PART #") "C313707")
        (field (name "PACKAGE") "0603")
      )
      (libsource (lib "TG21_TX_Ma tran phimPrjPcb") (part "0603 220R"))
    )
    (comp (ref "R11")
      (value "220R")
      (footprint "0603 MLCC")
      (description "100mW 220Ω 75V Thick Film Resistor ±1% ±100ppm/℃ 0603 Chip Resistor - Surface Mount RoHS")
      (fields
        (field (name "MFR. PART #") "CRCW0603220RFKEAHP")
        (field (name "LCSC PART #") "C313707")
        (field (name "PACKAGE") "0603")
      )
      (libsource (lib "TG21_TX_Ma tran phimPrjPcb") (part "0603 220R"))
    )
    (comp (ref "R12")
      (value "220R")
      (footprint "0603 MLCC")
      (description "100mW 220Ω 75V Thick Film Resistor ±1% ±100ppm/℃ 0603 Chip Resistor - Surface Mount RoHS")
      (fields
        (field (name "MFR. PART #") "CRCW0603220RFKEAHP")
        (field (name "LCSC PART #") "C313707")
        (field (name "PACKAGE") "0603")
      )
      (libsource (lib "TG21_TX_Ma tran phimPrjPcb") (part "0603 220R"))
    )
    (comp (ref "R13")
      (value "220R")
      (footprint "0603 MLCC")
      (description "100mW 220Ω 75V Thick Film Resistor ±1% ±100ppm/℃ 0603 Chip Resistor - Surface Mount RoHS")
      (fields
        (field (name "MFR. PART #") "CRCW0603220RFKEAHP")
        (field (name "LCSC PART #") "C313707")
        (field (name "PACKAGE") "0603")
      )
      (libsource (lib "TG21_TX_Ma tran phimPrjPcb") (part "0603 220R"))
    )
    (comp (ref "R14")
      (value "10K")
      (footprint "0603 Resistors")
      (description "100mW 10kΩ 75V Thick Film Resistor ±1% ±100ppm/℃ 0603 Chip Resistor - Surface Mount RoHS")
      (fields
        (field (name "MANUFACTURER") "VISHAY")
        (field (name "MFR. PART #") "CRCW060310K0FKEA")
        (field (name "PACKAGE") "0603")
      )
      (libsource (lib "TG21_TX_Ma tran phimPrjPcb") (part "0603 10K"))
    )
    (comp (ref "R15")
      (value "10K")
      (footprint "0603 Resistors")
      (description "100mW 10kΩ 75V Thick Film Resistor ±1% ±100ppm/℃ 0603 Chip Resistor - Surface Mount RoHS")
      (fields
        (field (name "MANUFACTURER") "VISHAY")
        (field (name "MFR. PART #") "CRCW060310K0FKEA")
        (field (name "PACKAGE") "0603")
      )
      (libsource (lib "TG21_TX_Ma tran phimPrjPcb") (part "0603 10K"))
    )
    (comp (ref "R16")
      (value "10K")
      (footprint "0603 Resistors")
      (description "100mW 10kΩ 75V Thick Film Resistor ±1% ±100ppm/℃ 0603 Chip Resistor - Surface Mount RoHS")
      (fields
        (field (name "MANUFACTURER") "VISHAY")
        (field (name "MFR. PART #") "CRCW060310K0FKEA")
        (field (name "PACKAGE") "0603")
      )
      (libsource (lib "TG21_TX_Ma tran phimPrjPcb") (part "0603 10K"))
    )
    (comp (ref "R17")
      (value "10K")
      (footprint "0603 Resistors")
      (description "100mW 10kΩ 75V Thick Film Resistor ±1% ±100ppm/℃ 0603 Chip Resistor - Surface Mount RoHS")
      (fields
        (field (name "MANUFACTURER") "VISHAY")
        (field (name "MFR. PART #") "CRCW060310K0FKEA")
        (field (name "PACKAGE") "0603")
      )
      (libsource (lib "TG21_TX_Ma tran phimPrjPcb") (part "0603 10K"))
    )
    (comp (ref "R18")
      (value "10K")
      (footprint "0603 Resistors")
      (description "100mW 10kΩ 75V Thick Film Resistor ±1% ±100ppm/℃ 0603 Chip Resistor - Surface Mount RoHS")
      (fields
        (field (name "MANUFACTURER") "VISHAY")
        (field (name "MFR. PART #") "CRCW060310K0FKEA")
        (field (name "PACKAGE") "0603")
      )
      (libsource (lib "TG21_TX_Ma tran phimPrjPcb") (part "0603 10K"))
    )
    (comp (ref "R19")
      (value "10K")
      (footprint "0603 Resistors")
      (description "100mW 10kΩ 75V Thick Film Resistor ±1% ±100ppm/℃ 0603 Chip Resistor - Surface Mount RoHS")
      (fields
        (field (name "MANUFACTURER") "VISHAY")
        (field (name "MFR. PART #") "CRCW060310K0FKEA")
        (field (name "PACKAGE") "0603")
      )
      (libsource (lib "TG21_TX_Ma tran phimPrjPcb") (part "0603 10K"))
    )
    (comp (ref "R20")
      (value "10K")
      (footprint "0603 Resistors")
      (description "100mW 10kΩ 75V Thick Film Resistor ±1% ±100ppm/℃ 0603 Chip Resistor - Surface Mount RoHS")
      (fields
        (field (name "MANUFACTURER") "VISHAY")
        (field (name "MFR. PART #") "CRCW060310K0FKEA")
        (field (name "PACKAGE") "0603")
      )
      (libsource (lib "TG21_TX_Ma tran phimPrjPcb") (part "0603 10K"))
    )
    (comp (ref "R21")
      (value "10K")
      (footprint "0603 Resistors")
      (description "100mW 10kΩ 75V Thick Film Resistor ±1% ±100ppm/℃ 0603 Chip Resistor - Surface Mount RoHS")
      (fields
        (field (name "MANUFACTURER") "VISHAY")
        (field (name "MFR. PART #") "CRCW060310K0FKEA")
        (field (name "PACKAGE") "0603")
      )
      (libsource (lib "TG21_TX_Ma tran phimPrjPcb") (part "0603 10K"))
    )
    (comp (ref "R22")
      (value "10K")
      (footprint "0603 Resistors")
      (description "100mW 10kΩ 75V Thick Film Resistor ±1% ±100ppm/℃ 0603 Chip Resistor - Surface Mount RoHS")
      (fields
        (field (name "MANUFACTURER") "VISHAY")
        (field (name "MFR. PART #") "CRCW060310K0FKEA")
        (field (name "PACKAGE") "0603")
      )
      (libsource (lib "TG21_TX_Ma tran phimPrjPcb") (part "0603 10K"))
    )
    (comp (ref "R23")
      (value "10K")
      (footprint "0603 Resistors")
      (description "100mW 10kΩ 75V Thick Film Resistor ±1% ±100ppm/℃ 0603 Chip Resistor - Surface Mount RoHS")
      (fields
        (field (name "MANUFACTURER") "VISHAY")
        (field (name "MFR. PART #") "CRCW060310K0FKEA")
        (field (name "PACKAGE") "0603")
      )
      (libsource (lib "TG21_TX_Ma tran phimPrjPcb") (part "0603 10K"))
    )
    (comp (ref "R24")
      (value "10K")
      (footprint "0603 Resistors")
      (description "100mW 10kΩ 75V Thick Film Resistor ±1% ±100ppm/℃ 0603 Chip Resistor - Surface Mount RoHS")
      (fields
        (field (name "MANUFACTURER") "VISHAY")
        (field (name "MFR. PART #") "CRCW060310K0FKEA")
        (field (name "PACKAGE") "0603")
      )
      (libsource (lib "TG21_TX_Ma tran phimPrjPcb") (part "0603 10K"))
    )
    (comp (ref "R25")
      (value "10K")
      (footprint "0603 Resistors")
      (description "100mW 10kΩ 75V Thick Film Resistor ±1% ±100ppm/℃ 0603 Chip Resistor - Surface Mount RoHS")
      (fields
        (field (name "MANUFACTURER") "VISHAY")
        (field (name "MFR. PART #") "CRCW060310K0FKEA")
        (field (name "PACKAGE") "0603")
      )
      (libsource (lib "TG21_TX_Ma tran phimPrjPcb") (part "0603 10K"))
    )
    (comp (ref "R26")
      (value "10K")
      (footprint "0603 Resistors")
      (description "100mW 10kΩ 75V Thick Film Resistor ±1% ±100ppm/℃ 0603 Chip Resistor - Surface Mount RoHS")
      (fields
        (field (name "MANUFACTURER") "VISHAY")
        (field (name "MFR. PART #") "CRCW060310K0FKEA")
        (field (name "PACKAGE") "0603")
      )
      (libsource (lib "TG21_TX_Ma tran phimPrjPcb") (part "0603 10K"))
    )
    (comp (ref "R27")
      (value "220R")
      (footprint "0603 MLCC")
      (description "100mW 220Ω 75V Thick Film Resistor ±1% ±100ppm/℃ 0603 Chip Resistor - Surface Mount RoHS")
      (fields
        (field (name "MFR. PART #") "CRCW0603220RFKEAHP")
        (field (name "LCSC PART #") "C313707")
        (field (name "PACKAGE") "0603")
      )
      (libsource (lib "TG21_TX_Ma tran phimPrjPcb") (part "0603 220R"))
    )
    (comp (ref "R28")
      (value "220R")
      (footprint "0603 MLCC")
      (description "100mW 220Ω 75V Thick Film Resistor ±1% ±100ppm/℃ 0603 Chip Resistor - Surface Mount RoHS")
      (fields
        (field (name "MFR. PART #") "CRCW0603220RFKEAHP")
        (field (name "LCSC PART #") "C313707")
        (field (name "PACKAGE") "0603")
      )
      (libsource (lib "TG21_TX_Ma tran phimPrjPcb") (part "0603 220R"))
    )
    (comp (ref "R29")
      (value "220R")
      (footprint "0603 MLCC")
      (description "100mW 220Ω 75V Thick Film Resistor ±1% ±100ppm/℃ 0603 Chip Resistor - Surface Mount RoHS")
      (fields
        (field (name "MFR. PART #") "CRCW0603220RFKEAHP")
        (field (name "LCSC PART #") "C313707")
        (field (name "PACKAGE") "0603")
      )
      (libsource (lib "TG21_TX_Ma tran phimPrjPcb") (part "0603 220R"))
    )
    (comp (ref "R30")
      (value "220R")
      (footprint "0603 MLCC")
      (description "100mW 220Ω 75V Thick Film Resistor ±1% ±100ppm/℃ 0603 Chip Resistor - Surface Mount RoHS")
      (fields
        (field (name "MFR. PART #") "CRCW0603220RFKEAHP")
        (field (name "LCSC PART #") "C313707")
        (field (name "PACKAGE") "0603")
      )
      (libsource (lib "TG21_TX_Ma tran phimPrjPcb") (part "0603 220R"))
    )
    (comp (ref "R31")
      (value "220R")
      (footprint "0603 MLCC")
      (description "100mW 220Ω 75V Thick Film Resistor ±1% ±100ppm/℃ 0603 Chip Resistor - Surface Mount RoHS")
      (fields
        (field (name "MFR. PART #") "CRCW0603220RFKEAHP")
        (field (name "LCSC PART #") "C313707")
        (field (name "PACKAGE") "0603")
      )
      (libsource (lib "TG21_TX_Ma tran phimPrjPcb") (part "0603 220R"))
    )
    (comp (ref "R32")
      (value "220R")
      (footprint "0603 MLCC")
      (description "100mW 220Ω 75V Thick Film Resistor ±1% ±100ppm/℃ 0603 Chip Resistor - Surface Mount RoHS")
      (fields
        (field (name "MFR. PART #") "CRCW0603220RFKEAHP")
        (field (name "LCSC PART #") "C313707")
        (field (name "PACKAGE") "0603")
      )
      (libsource (lib "TG21_TX_Ma tran phimPrjPcb") (part "0603 220R"))
    )
    (comp (ref "R33")
      (value "220R")
      (footprint "0603 MLCC")
      (description "100mW 220Ω 75V Thick Film Resistor ±1% ±100ppm/℃ 0603 Chip Resistor - Surface Mount RoHS")
      (fields
        (field (name "MFR. PART #") "CRCW0603220RFKEAHP")
        (field (name "LCSC PART #") "C313707")
        (field (name "PACKAGE") "0603")
      )
      (libsource (lib "TG21_TX_Ma tran phimPrjPcb") (part "0603 220R"))
    )
    (comp (ref "R34")
      (value "220R")
      (footprint "0603 MLCC")
      (description "100mW 220Ω 75V Thick Film Resistor ±1% ±100ppm/℃ 0603 Chip Resistor - Surface Mount RoHS")
      (fields
        (field (name "MFR. PART #") "CRCW0603220RFKEAHP")
        (field (name "LCSC PART #") "C313707")
        (field (name "PACKAGE") "0603")
      )
      (libsource (lib "TG21_TX_Ma tran phimPrjPcb") (part "0603 220R"))
    )
    (comp (ref "R35")
      (value "220R")
      (footprint "0603 MLCC")
      (description "100mW 220Ω 75V Thick Film Resistor ±1% ±100ppm/℃ 0603 Chip Resistor - Surface Mount RoHS")
      (fields
        (field (name "MFR. PART #") "CRCW0603220RFKEAHP")
        (field (name "LCSC PART #") "C313707")
        (field (name "PACKAGE") "0603")
      )
      (libsource (lib "TG21_TX_Ma tran phimPrjPcb") (part "0603 220R"))
    )
    (comp (ref "R36")
      (value "220R")
      (footprint "0603 MLCC")
      (description "100mW 220Ω 75V Thick Film Resistor ±1% ±100ppm/℃ 0603 Chip Resistor - Surface Mount RoHS")
      (fields
        (field (name "MFR. PART #") "CRCW0603220RFKEAHP")
        (field (name "LCSC PART #") "C313707")
        (field (name "PACKAGE") "0603")
      )
      (libsource (lib "TG21_TX_Ma tran phimPrjPcb") (part "0603 220R"))
    )
    (comp (ref "R37")
      (value "220R")
      (footprint "0603 MLCC")
      (description "100mW 220Ω 75V Thick Film Resistor ±1% ±100ppm/℃ 0603 Chip Resistor - Surface Mount RoHS")
      (fields
        (field (name "MFR. PART #") "CRCW0603220RFKEAHP")
        (field (name "LCSC PART #") "C313707")
        (field (name "PACKAGE") "0603")
      )
      (libsource (lib "TG21_TX_Ma tran phimPrjPcb") (part "0603 220R"))
    )
    (comp (ref "R38")
      (value "220R")
      (footprint "0603 MLCC")
      (description "100mW 220Ω 75V Thick Film Resistor ±1% ±100ppm/℃ 0603 Chip Resistor - Surface Mount RoHS")
      (fields
        (field (name "MFR. PART #") "CRCW0603220RFKEAHP")
        (field (name "LCSC PART #") "C313707")
        (field (name "PACKAGE") "0603")
      )
      (libsource (lib "TG21_TX_Ma tran phimPrjPcb") (part "0603 220R"))
    )
    (comp (ref "R39")
      (value "220R")
      (footprint "0603 MLCC")
      (description "100mW 220Ω 75V Thick Film Resistor ±1% ±100ppm/℃ 0603 Chip Resistor - Surface Mount RoHS")
      (fields
        (field (name "MFR. PART #") "CRCW0603220RFKEAHP")
        (field (name "LCSC PART #") "C313707")
        (field (name "PACKAGE") "0603")
      )
      (libsource (lib "TG21_TX_Ma tran phimPrjPcb") (part "0603 220R"))
    )
    (comp (ref "R40")
      (value "10K")
      (footprint "0603 Resistors")
      (description "100mW 10kΩ 75V Thick Film Resistor ±1% ±100ppm/℃ 0603 Chip Resistor - Surface Mount RoHS")
      (fields
        (field (name "MANUFACTURER") "VISHAY")
        (field (name "MFR. PART #") "CRCW060310K0FKEA")
        (field (name "PACKAGE") "0603")
      )
      (libsource (lib "TG21_TX_Ma tran phimPrjPcb") (part "0603 10K"))
    )
    (comp (ref "R41")
      (value "10K")
      (footprint "0603 Resistors")
      (description "100mW 10kΩ 75V Thick Film Resistor ±1% ±100ppm/℃ 0603 Chip Resistor - Surface Mount RoHS")
      (fields
        (field (name "MANUFACTURER") "VISHAY")
        (field (name "MFR. PART #") "CRCW060310K0FKEA")
        (field (name "PACKAGE") "0603")
      )
      (libsource (lib "TG21_TX_Ma tran phimPrjPcb") (part "0603 10K"))
    )
    (comp (ref "R42")
      (value "10K")
      (footprint "0603 Resistors")
      (description "100mW 10kΩ 75V Thick Film Resistor ±1% ±100ppm/℃ 0603 Chip Resistor - Surface Mount RoHS")
      (fields
        (field (name "MANUFACTURER") "VISHAY")
        (field (name "MFR. PART #") "CRCW060310K0FKEA")
        (field (name "PACKAGE") "0603")
      )
      (libsource (lib "TG21_TX_Ma tran phimPrjPcb") (part "0603 10K"))
    )
    (comp (ref "R43")
      (value "10K")
      (footprint "0603 Resistors")
      (description "100mW 10kΩ 75V Thick Film Resistor ±1% ±100ppm/℃ 0603 Chip Resistor - Surface Mount RoHS")
      (fields
        (field (name "MANUFACTURER") "VISHAY")
        (field (name "MFR. PART #") "CRCW060310K0FKEA")
        (field (name "PACKAGE") "0603")
      )
      (libsource (lib "TG21_TX_Ma tran phimPrjPcb") (part "0603 10K"))
    )
    (comp (ref "R44")
      (value "10K")
      (footprint "0603 Resistors")
      (description "100mW 10kΩ 75V Thick Film Resistor ±1% ±100ppm/℃ 0603 Chip Resistor - Surface Mount RoHS")
      (fields
        (field (name "MANUFACTURER") "VISHAY")
        (field (name "MFR. PART #") "CRCW060310K0FKEA")
        (field (name "PACKAGE") "0603")
      )
      (libsource (lib "TG21_TX_Ma tran phimPrjPcb") (part "0603 10K"))
    )
    (comp (ref "R45")
      (value "10K")
      (footprint "0603 Resistors")
      (description "100mW 10kΩ 75V Thick Film Resistor ±1% ±100ppm/℃ 0603 Chip Resistor - Surface Mount RoHS")
      (fields
        (field (name "MANUFACTURER") "VISHAY")
        (field (name "MFR. PART #") "CRCW060310K0FKEA")
        (field (name "PACKAGE") "0603")
      )
      (libsource (lib "TG21_TX_Ma tran phimPrjPcb") (part "0603 10K"))
    )
    (comp (ref "R46")
      (value "10K")
      (footprint "0603 Resistors")
      (description "100mW 10kΩ 75V Thick Film Resistor ±1% ±100ppm/℃ 0603 Chip Resistor - Surface Mount RoHS")
      (fields
        (field (name "MANUFACTURER") "VISHAY")
        (field (name "MFR. PART #") "CRCW060310K0FKEA")
        (field (name "PACKAGE") "0603")
      )
      (libsource (lib "TG21_TX_Ma tran phimPrjPcb") (part "0603 10K"))
    )
    (comp (ref "R47")
      (value "10K")
      (footprint "0603 Resistors")
      (description "100mW 10kΩ 75V Thick Film Resistor ±1% ±100ppm/℃ 0603 Chip Resistor - Surface Mount RoHS")
      (fields
        (field (name "MANUFACTURER") "VISHAY")
        (field (name "MFR. PART #") "CRCW060310K0FKEA")
        (field (name "PACKAGE") "0603")
      )
      (libsource (lib "TG21_TX_Ma tran phimPrjPcb") (part "0603 10K"))
    )
    (comp (ref "R48")
      (value "10K")
      (footprint "0603 Resistors")
      (description "100mW 10kΩ 75V Thick Film Resistor ±1% ±100ppm/℃ 0603 Chip Resistor - Surface Mount RoHS")
      (fields
        (field (name "MANUFACTURER") "VISHAY")
        (field (name "MFR. PART #") "CRCW060310K0FKEA")
        (field (name "PACKAGE") "0603")
      )
      (libsource (lib "TG21_TX_Ma tran phimPrjPcb") (part "0603 10K"))
    )
    (comp (ref "R49")
      (value "10K")
      (footprint "0603 Resistors")
      (description "100mW 10kΩ 75V Thick Film Resistor ±1% ±100ppm/℃ 0603 Chip Resistor - Surface Mount RoHS")
      (fields
        (field (name "MANUFACTURER") "VISHAY")
        (field (name "MFR. PART #") "CRCW060310K0FKEA")
        (field (name "PACKAGE") "0603")
      )
      (libsource (lib "TG21_TX_Ma tran phimPrjPcb") (part "0603 10K"))
    )
    (comp (ref "R50")
      (value "10K")
      (footprint "0603 Resistors")
      (description "100mW 10kΩ 75V Thick Film Resistor ±1% ±100ppm/℃ 0603 Chip Resistor - Surface Mount RoHS")
      (fields
        (field (name "MANUFACTURER") "VISHAY")
        (field (name "MFR. PART #") "CRCW060310K0FKEA")
        (field (name "PACKAGE") "0603")
      )
      (libsource (lib "TG21_TX_Ma tran phimPrjPcb") (part "0603 10K"))
    )
    (comp (ref "R51")
      (value "10K")
      (footprint "0603 Resistors")
      (description "100mW 10kΩ 75V Thick Film Resistor ±1% ±100ppm/℃ 0603 Chip Resistor - Surface Mount RoHS")
      (fields
        (field (name "MANUFACTURER") "VISHAY")
        (field (name "MFR. PART #") "CRCW060310K0FKEA")
        (field (name "PACKAGE") "0603")
      )
      (libsource (lib "TG21_TX_Ma tran phimPrjPcb") (part "0603 10K"))
    )
    (comp (ref "R52")
      (value "10K")
      (footprint "0603 Resistors")
      (description "100mW 10kΩ 75V Thick Film Resistor ±1% ±100ppm/℃ 0603 Chip Resistor - Surface Mount RoHS")
      (fields
        (field (name "MANUFACTURER") "VISHAY")
        (field (name "MFR. PART #") "CRCW060310K0FKEA")
        (field (name "PACKAGE") "0603")
      )
      (libsource (lib "TG21_TX_Ma tran phimPrjPcb") (part "0603 10K"))
    )
    (comp (ref "R53")
      (value "220R")
      (footprint "0603 MLCC")
      (description "100mW 220Ω 75V Thick Film Resistor ±1% ±100ppm/℃ 0603 Chip Resistor - Surface Mount RoHS")
      (fields
        (field (name "MFR. PART #") "CRCW0603220RFKEAHP")
        (field (name "LCSC PART #") "C313707")
        (field (name "PACKAGE") "0603")
      )
      (libsource (lib "TG21_TX_Ma tran phimPrjPcb") (part "0603 220R"))
    )
    (comp (ref "R54")
      (value "220R")
      (footprint "0603 MLCC")
      (description "100mW 220Ω 75V Thick Film Resistor ±1% ±100ppm/℃ 0603 Chip Resistor - Surface Mount RoHS")
      (fields
        (field (name "MFR. PART #") "CRCW0603220RFKEAHP")
        (field (name "LCSC PART #") "C313707")
        (field (name "PACKAGE") "0603")
      )
      (libsource (lib "TG21_TX_Ma tran phimPrjPcb") (part "0603 220R"))
    )
    (comp (ref "R55")
      (value "220R")
      (footprint "0603 MLCC")
      (description "100mW 220Ω 75V Thick Film Resistor ±1% ±100ppm/℃ 0603 Chip Resistor - Surface Mount RoHS")
      (fields
        (field (name "MFR. PART #") "CRCW0603220RFKEAHP")
        (field (name "LCSC PART #") "C313707")
        (field (name "PACKAGE") "0603")
      )
      (libsource (lib "TG21_TX_Ma tran phimPrjPcb") (part "0603 220R"))
    )
    (comp (ref "R56")
      (value "220R")
      (footprint "0603 MLCC")
      (description "100mW 220Ω 75V Thick Film Resistor ±1% ±100ppm/℃ 0603 Chip Resistor - Surface Mount RoHS")
      (fields
        (field (name "MFR. PART #") "CRCW0603220RFKEAHP")
        (field (name "LCSC PART #") "C313707")
        (field (name "PACKAGE") "0603")
      )
      (libsource (lib "TG21_TX_Ma tran phimPrjPcb") (part "0603 220R"))
    )
    (comp (ref "R57")
      (value "220R")
      (footprint "0603 MLCC")
      (description "100mW 220Ω 75V Thick Film Resistor ±1% ±100ppm/℃ 0603 Chip Resistor - Surface Mount RoHS")
      (fields
        (field (name "MFR. PART #") "CRCW0603220RFKEAHP")
        (field (name "LCSC PART #") "C313707")
        (field (name "PACKAGE") "0603")
      )
      (libsource (lib "TG21_TX_Ma tran phimPrjPcb") (part "0603 220R"))
    )
    (comp (ref "R58")
      (value "220R")
      (footprint "0603 MLCC")
      (description "100mW 220Ω 75V Thick Film Resistor ±1% ±100ppm/℃ 0603 Chip Resistor - Surface Mount RoHS")
      (fields
        (field (name "MFR. PART #") "CRCW0603220RFKEAHP")
        (field (name "LCSC PART #") "C313707")
        (field (name "PACKAGE") "0603")
      )
      (libsource (lib "TG21_TX_Ma tran phimPrjPcb") (part "0603 220R"))
    )
    (comp (ref "R59")
      (value "220R")
      (footprint "0603 MLCC")
      (description "100mW 220Ω 75V Thick Film Resistor ±1% ±100ppm/℃ 0603 Chip Resistor - Surface Mount RoHS")
      (fields
        (field (name "MFR. PART #") "CRCW0603220RFKEAHP")
        (field (name "LCSC PART #") "C313707")
        (field (name "PACKAGE") "0603")
      )
      (libsource (lib "TG21_TX_Ma tran phimPrjPcb") (part "0603 220R"))
    )
    (comp (ref "R60")
      (value "220R")
      (footprint "0603 MLCC")
      (description "100mW 220Ω 75V Thick Film Resistor ±1% ±100ppm/℃ 0603 Chip Resistor - Surface Mount RoHS")
      (fields
        (field (name "MFR. PART #") "CRCW0603220RFKEAHP")
        (field (name "LCSC PART #") "C313707")
        (field (name "PACKAGE") "0603")
      )
      (libsource (lib "TG21_TX_Ma tran phimPrjPcb") (part "0603 220R"))
    )
    (comp (ref "R61")
      (value "220R")
      (footprint "0603 MLCC")
      (description "100mW 220Ω 75V Thick Film Resistor ±1% ±100ppm/℃ 0603 Chip Resistor - Surface Mount RoHS")
      (fields
        (field (name "MFR. PART #") "CRCW0603220RFKEAHP")
        (field (name "LCSC PART #") "C313707")
        (field (name "PACKAGE") "0603")
      )
      (libsource (lib "TG21_TX_Ma tran phimPrjPcb") (part "0603 220R"))
    )
    (comp (ref "R62")
      (value "220R")
      (footprint "0603 MLCC")
      (description "100mW 220Ω 75V Thick Film Resistor ±1% ±100ppm/℃ 0603 Chip Resistor - Surface Mount RoHS")
      (fields
        (field (name "MFR. PART #") "CRCW0603220RFKEAHP")
        (field (name "LCSC PART #") "C313707")
        (field (name "PACKAGE") "0603")
      )
      (libsource (lib "TG21_TX_Ma tran phimPrjPcb") (part "0603 220R"))
    )
    (comp (ref "R63")
      (value "220R")
      (footprint "0603 MLCC")
      (description "100mW 220Ω 75V Thick Film Resistor ±1% ±100ppm/℃ 0603 Chip Resistor - Surface Mount RoHS")
      (fields
        (field (name "MFR. PART #") "CRCW0603220RFKEAHP")
        (field (name "LCSC PART #") "C313707")
        (field (name "PACKAGE") "0603")
      )
      (libsource (lib "TG21_TX_Ma tran phimPrjPcb") (part "0603 220R"))
    )
    (comp (ref "R64")
      (value "220R")
      (footprint "0603 MLCC")
      (description "100mW 220Ω 75V Thick Film Resistor ±1% ±100ppm/℃ 0603 Chip Resistor - Surface Mount RoHS")
      (fields
        (field (name "MFR. PART #") "CRCW0603220RFKEAHP")
        (field (name "LCSC PART #") "C313707")
        (field (name "PACKAGE") "0603")
      )
      (libsource (lib "TG21_TX_Ma tran phimPrjPcb") (part "0603 220R"))
    )
    (comp (ref "R65")
      (value "220R")
      (footprint "0603 MLCC")
      (description "100mW 220Ω 75V Thick Film Resistor ±1% ±100ppm/℃ 0603 Chip Resistor - Surface Mount RoHS")
      (fields
        (field (name "MFR. PART #") "CRCW0603220RFKEAHP")
        (field (name "LCSC PART #") "C313707")
        (field (name "PACKAGE") "0603")
      )
      (libsource (lib "TG21_TX_Ma tran phimPrjPcb") (part "0603 220R"))
    )
    (comp (ref "R66")
      (value "10K")
      (footprint "0603 Resistors")
      (description "100mW 10kΩ 75V Thick Film Resistor ±1% ±100ppm/℃ 0603 Chip Resistor - Surface Mount RoHS")
      (fields
        (field (name "MANUFACTURER") "VISHAY")
        (field (name "MFR. PART #") "CRCW060310K0FKEA")
        (field (name "PACKAGE") "0603")
      )
      (libsource (lib "TG21_TX_Ma tran phimPrjPcb") (part "0603 10K"))
    )
    (comp (ref "R67")
      (value "10K")
      (footprint "0603 Resistors")
      (description "100mW 10kΩ 75V Thick Film Resistor ±1% ±100ppm/℃ 0603 Chip Resistor - Surface Mount RoHS")
      (fields
        (field (name "MANUFACTURER") "VISHAY")
        (field (name "MFR. PART #") "CRCW060310K0FKEA")
        (field (name "PACKAGE") "0603")
      )
      (libsource (lib "TG21_TX_Ma tran phimPrjPcb") (part "0603 10K"))
    )
    (comp (ref "R68")
      (value "10K")
      (footprint "0603 Resistors")
      (description "100mW 10kΩ 75V Thick Film Resistor ±1% ±100ppm/℃ 0603 Chip Resistor - Surface Mount RoHS")
      (fields
        (field (name "MANUFACTURER") "VISHAY")
        (field (name "MFR. PART #") "CRCW060310K0FKEA")
        (field (name "PACKAGE") "0603")
      )
      (libsource (lib "TG21_TX_Ma tran phimPrjPcb") (part "0603 10K"))
    )
    (comp (ref "R69")
      (value "10K")
      (footprint "0603 Resistors")
      (description "100mW 10kΩ 75V Thick Film Resistor ±1% ±100ppm/℃ 0603 Chip Resistor - Surface Mount RoHS")
      (fields
        (field (name "MANUFACTURER") "VISHAY")
        (field (name "MFR. PART #") "CRCW060310K0FKEA")
        (field (name "PACKAGE") "0603")
      )
      (libsource (lib "TG21_TX_Ma tran phimPrjPcb") (part "0603 10K"))
    )
    (comp (ref "R70")
      (value "10K")
      (footprint "0603 Resistors")
      (description "100mW 10kΩ 75V Thick Film Resistor ±1% ±100ppm/℃ 0603 Chip Resistor - Surface Mount RoHS")
      (fields
        (field (name "MANUFACTURER") "VISHAY")
        (field (name "MFR. PART #") "CRCW060310K0FKEA")
        (field (name "PACKAGE") "0603")
      )
      (libsource (lib "TG21_TX_Ma tran phimPrjPcb") (part "0603 10K"))
    )
    (comp (ref "R71")
      (value "10K")
      (footprint "0603 Resistors")
      (description "100mW 10kΩ 75V Thick Film Resistor ±1% ±100ppm/℃ 0603 Chip Resistor - Surface Mount RoHS")
      (fields
        (field (name "MANUFACTURER") "VISHAY")
        (field (name "MFR. PART #") "CRCW060310K0FKEA")
        (field (name "PACKAGE") "0603")
      )
      (libsource (lib "TG21_TX_Ma tran phimPrjPcb") (part "0603 10K"))
    )
    (comp (ref "R72")
      (value "10K")
      (footprint "0603 Resistors")
      (description "100mW 10kΩ 75V Thick Film Resistor ±1% ±100ppm/℃ 0603 Chip Resistor - Surface Mount RoHS")
      (fields
        (field (name "MANUFACTURER") "VISHAY")
        (field (name "MFR. PART #") "CRCW060310K0FKEA")
        (field (name "PACKAGE") "0603")
      )
      (libsource (lib "TG21_TX_Ma tran phimPrjPcb") (part "0603 10K"))
    )
    (comp (ref "R73")
      (value "10K")
      (footprint "0603 Resistors")
      (description "100mW 10kΩ 75V Thick Film Resistor ±1% ±100ppm/℃ 0603 Chip Resistor - Surface Mount RoHS")
      (fields
        (field (name "MANUFACTURER") "VISHAY")
        (field (name "MFR. PART #") "CRCW060310K0FKEA")
        (field (name "PACKAGE") "0603")
      )
      (libsource (lib "TG21_TX_Ma tran phimPrjPcb") (part "0603 10K"))
    )
    (comp (ref "R74")
      (value "10K")
      (footprint "0603 Resistors")
      (description "100mW 10kΩ 75V Thick Film Resistor ±1% ±100ppm/℃ 0603 Chip Resistor - Surface Mount RoHS")
      (fields
        (field (name "MANUFACTURER") "VISHAY")
        (field (name "MFR. PART #") "CRCW060310K0FKEA")
        (field (name "PACKAGE") "0603")
      )
      (libsource (lib "TG21_TX_Ma tran phimPrjPcb") (part "0603 10K"))
    )
    (comp (ref "R75")
      (value "10K")
      (footprint "0603 Resistors")
      (description "100mW 10kΩ 75V Thick Film Resistor ±1% ±100ppm/℃ 0603 Chip Resistor - Surface Mount RoHS")
      (fields
        (field (name "MANUFACTURER") "VISHAY")
        (field (name "MFR. PART #") "CRCW060310K0FKEA")
        (field (name "PACKAGE") "0603")
      )
      (libsource (lib "TG21_TX_Ma tran phimPrjPcb") (part "0603 10K"))
    )
    (comp (ref "R76")
      (value "10K")
      (footprint "0603 Resistors")
      (description "100mW 10kΩ 75V Thick Film Resistor ±1% ±100ppm/℃ 0603 Chip Resistor - Surface Mount RoHS")
      (fields
        (field (name "MANUFACTURER") "VISHAY")
        (field (name "MFR. PART #") "CRCW060310K0FKEA")
        (field (name "PACKAGE") "0603")
      )
      (libsource (lib "TG21_TX_Ma tran phimPrjPcb") (part "0603 10K"))
    )
    (comp (ref "R77")
      (value "10K")
      (footprint "0603 Resistors")
      (description "100mW 10kΩ 75V Thick Film Resistor ±1% ±100ppm/℃ 0603 Chip Resistor - Surface Mount RoHS")
      (fields
        (field (name "MANUFACTURER") "VISHAY")
        (field (name "MFR. PART #") "CRCW060310K0FKEA")
        (field (name "PACKAGE") "0603")
      )
      (libsource (lib "TG21_TX_Ma tran phimPrjPcb") (part "0603 10K"))
    )
    (comp (ref "R78")
      (value "10K")
      (footprint "0603 Resistors")
      (description "100mW 10kΩ 75V Thick Film Resistor ±1% ±100ppm/℃ 0603 Chip Resistor - Surface Mount RoHS")
      (fields
        (field (name "MANUFACTURER") "VISHAY")
        (field (name "MFR. PART #") "CRCW060310K0FKEA")
        (field (name "PACKAGE") "0603")
      )
      (libsource (lib "TG21_TX_Ma tran phimPrjPcb") (part "0603 10K"))
    )
    (comp (ref "R79")
      (value "220R")
      (footprint "0603 MLCC")
      (description "100mW 220Ω 75V Thick Film Resistor ±1% ±100ppm/℃ 0603 Chip Resistor - Surface Mount RoHS")
      (fields
        (field (name "MFR. PART #") "CRCW0603220RFKEAHP")
        (field (name "LCSC PART #") "C313707")
        (field (name "PACKAGE") "0603")
      )
      (libsource (lib "TG21_TX_Ma tran phimPrjPcb") (part "0603 220R"))
    )
    (comp (ref "R80")
      (value "220R")
      (footprint "0603 MLCC")
      (description "100mW 220Ω 75V Thick Film Resistor ±1% ±100ppm/℃ 0603 Chip Resistor - Surface Mount RoHS")
      (fields
        (field (name "MFR. PART #") "CRCW0603220RFKEAHP")
        (field (name "LCSC PART #") "C313707")
        (field (name "PACKAGE") "0603")
      )
      (libsource (lib "TG21_TX_Ma tran phimPrjPcb") (part "0603 220R"))
    )
    (comp (ref "R81")
      (value "220R")
      (footprint "0603 MLCC")
      (description "100mW 220Ω 75V Thick Film Resistor ±1% ±100ppm/℃ 0603 Chip Resistor - Surface Mount RoHS")
      (fields
        (field (name "MFR. PART #") "CRCW0603220RFKEAHP")
        (field (name "LCSC PART #") "C313707")
        (field (name "PACKAGE") "0603")
      )
      (libsource (lib "TG21_TX_Ma tran phimPrjPcb") (part "0603 220R"))
    )
    (comp (ref "R82")
      (value "220R")
      (footprint "0603 MLCC")
      (description "100mW 220Ω 75V Thick Film Resistor ±1% ±100ppm/℃ 0603 Chip Resistor - Surface Mount RoHS")
      (fields
        (field (name "MFR. PART #") "CRCW0603220RFKEAHP")
        (field (name "LCSC PART #") "C313707")
        (field (name "PACKAGE") "0603")
      )
      (libsource (lib "TG21_TX_Ma tran phimPrjPcb") (part "0603 220R"))
    )
    (comp (ref "R83")
      (value "220R")
      (footprint "0603 MLCC")
      (description "100mW 220Ω 75V Thick Film Resistor ±1% ±100ppm/℃ 0603 Chip Resistor - Surface Mount RoHS")
      (fields
        (field (name "MFR. PART #") "CRCW0603220RFKEAHP")
        (field (name "LCSC PART #") "C313707")
        (field (name "PACKAGE") "0603")
      )
      (libsource (lib "TG21_TX_Ma tran phimPrjPcb") (part "0603 220R"))
    )
    (comp (ref "R84")
      (value "220R")
      (footprint "0603 MLCC")
      (description "100mW 220Ω 75V Thick Film Resistor ±1% ±100ppm/℃ 0603 Chip Resistor - Surface Mount RoHS")
      (fields
        (field (name "MFR. PART #") "CRCW0603220RFKEAHP")
        (field (name "LCSC PART #") "C313707")
        (field (name "PACKAGE") "0603")
      )
      (libsource (lib "TG21_TX_Ma tran phimPrjPcb") (part "0603 220R"))
    )
    (comp (ref "R85")
      (value "220R")
      (footprint "0603 MLCC")
      (description "100mW 220Ω 75V Thick Film Resistor ±1% ±100ppm/℃ 0603 Chip Resistor - Surface Mount RoHS")
      (fields
        (field (name "MFR. PART #") "CRCW0603220RFKEAHP")
        (field (name "LCSC PART #") "C313707")
        (field (name "PACKAGE") "0603")
      )
      (libsource (lib "TG21_TX_Ma tran phimPrjPcb") (part "0603 220R"))
    )
    (comp (ref "R86")
      (value "220R")
      (footprint "0603 MLCC")
      (description "100mW 220Ω 75V Thick Film Resistor ±1% ±100ppm/℃ 0603 Chip Resistor - Surface Mount RoHS")
      (fields
        (field (name "MFR. PART #") "CRCW0603220RFKEAHP")
        (field (name "LCSC PART #") "C313707")
        (field (name "PACKAGE") "0603")
      )
      (libsource (lib "TG21_TX_Ma tran phimPrjPcb") (part "0603 220R"))
    )
    (comp (ref "R87")
      (value "220R")
      (footprint "0603 MLCC")
      (description "100mW 220Ω 75V Thick Film Resistor ±1% ±100ppm/℃ 0603 Chip Resistor - Surface Mount RoHS")
      (fields
        (field (name "MFR. PART #") "CRCW0603220RFKEAHP")
        (field (name "LCSC PART #") "C313707")
        (field (name "PACKAGE") "0603")
      )
      (libsource (lib "TG21_TX_Ma tran phimPrjPcb") (part "0603 220R"))
    )
    (comp (ref "R88")
      (value "220R")
      (footprint "0603 MLCC")
      (description "100mW 220Ω 75V Thick Film Resistor ±1% ±100ppm/℃ 0603 Chip Resistor - Surface Mount RoHS")
      (fields
        (field (name "MFR. PART #") "CRCW0603220RFKEAHP")
        (field (name "LCSC PART #") "C313707")
        (field (name "PACKAGE") "0603")
      )
      (libsource (lib "TG21_TX_Ma tran phimPrjPcb") (part "0603 220R"))
    )
    (comp (ref "R89")
      (value "220R")
      (footprint "0603 MLCC")
      (description "100mW 220Ω 75V Thick Film Resistor ±1% ±100ppm/℃ 0603 Chip Resistor - Surface Mount RoHS")
      (fields
        (field (name "MFR. PART #") "CRCW0603220RFKEAHP")
        (field (name "LCSC PART #") "C313707")
        (field (name "PACKAGE") "0603")
      )
      (libsource (lib "TG21_TX_Ma tran phimPrjPcb") (part "0603 220R"))
    )
    (comp (ref "R90")
      (value "220R")
      (footprint "0603 MLCC")
      (description "100mW 220Ω 75V Thick Film Resistor ±1% ±100ppm/℃ 0603 Chip Resistor - Surface Mount RoHS")
      (fields
        (field (name "MFR. PART #") "CRCW0603220RFKEAHP")
        (field (name "LCSC PART #") "C313707")
        (field (name "PACKAGE") "0603")
      )
      (libsource (lib "TG21_TX_Ma tran phimPrjPcb") (part "0603 220R"))
    )
    (comp (ref "R91")
      (value "220R")
      (footprint "0603 MLCC")
      (description "100mW 220Ω 75V Thick Film Resistor ±1% ±100ppm/℃ 0603 Chip Resistor - Surface Mount RoHS")
      (fields
        (field (name "MFR. PART #") "CRCW0603220RFKEAHP")
        (field (name "LCSC PART #") "C313707")
        (field (name "PACKAGE") "0603")
      )
      (libsource (lib "TG21_TX_Ma tran phimPrjPcb") (part "0603 220R"))
    )
    (comp (ref "R92")
      (value "10K")
      (footprint "0603 Resistors")
      (description "100mW 10kΩ 75V Thick Film Resistor ±1% ±100ppm/℃ 0603 Chip Resistor - Surface Mount RoHS")
      (fields
        (field (name "MANUFACTURER") "VISHAY")
        (field (name "MFR. PART #") "CRCW060310K0FKEA")
        (field (name "PACKAGE") "0603")
      )
      (libsource (lib "TG21_TX_Ma tran phimPrjPcb") (part "0603 10K"))
    )
    (comp (ref "R93")
      (value "10K")
      (footprint "0603 Resistors")
      (description "100mW 10kΩ 75V Thick Film Resistor ±1% ±100ppm/℃ 0603 Chip Resistor - Surface Mount RoHS")
      (fields
        (field (name "MANUFACTURER") "VISHAY")
        (field (name "MFR. PART #") "CRCW060310K0FKEA")
        (field (name "PACKAGE") "0603")
      )
      (libsource (lib "TG21_TX_Ma tran phimPrjPcb") (part "0603 10K"))
    )
    (comp (ref "R94")
      (value "10K")
      (footprint "0603 Resistors")
      (description "100mW 10kΩ 75V Thick Film Resistor ±1% ±100ppm/℃ 0603 Chip Resistor - Surface Mount RoHS")
      (fields
        (field (name "MANUFACTURER") "VISHAY")
        (field (name "MFR. PART #") "CRCW060310K0FKEA")
        (field (name "PACKAGE") "0603")
      )
      (libsource (lib "TG21_TX_Ma tran phimPrjPcb") (part "0603 10K"))
    )
    (comp (ref "R95")
      (value "10K")
      (footprint "0603 Resistors")
      (description "100mW 10kΩ 75V Thick Film Resistor ±1% ±100ppm/℃ 0603 Chip Resistor - Surface Mount RoHS")
      (fields
        (field (name "MANUFACTURER") "VISHAY")
        (field (name "MFR. PART #") "CRCW060310K0FKEA")
        (field (name "PACKAGE") "0603")
      )
      (libsource (lib "TG21_TX_Ma tran phimPrjPcb") (part "0603 10K"))
    )
    (comp (ref "R96")
      (value "10K")
      (footprint "0603 Resistors")
      (description "100mW 10kΩ 75V Thick Film Resistor ±1% ±100ppm/℃ 0603 Chip Resistor - Surface Mount RoHS")
      (fields
        (field (name "MANUFACTURER") "VISHAY")
        (field (name "MFR. PART #") "CRCW060310K0FKEA")
        (field (name "PACKAGE") "0603")
      )
      (libsource (lib "TG21_TX_Ma tran phimPrjPcb") (part "0603 10K"))
    )
    (comp (ref "R97")
      (value "10K")
      (footprint "0603 Resistors")
      (description "100mW 10kΩ 75V Thick Film Resistor ±1% ±100ppm/℃ 0603 Chip Resistor - Surface Mount RoHS")
      (fields
        (field (name "MANUFACTURER") "VISHAY")
        (field (name "MFR. PART #") "CRCW060310K0FKEA")
        (field (name "PACKAGE") "0603")
      )
      (libsource (lib "TG21_TX_Ma tran phimPrjPcb") (part "0603 10K"))
    )
    (comp (ref "R98")
      (value "10K")
      (footprint "0603 Resistors")
      (description "100mW 10kΩ 75V Thick Film Resistor ±1% ±100ppm/℃ 0603 Chip Resistor - Surface Mount RoHS")
      (fields
        (field (name "MANUFACTURER") "VISHAY")
        (field (name "MFR. PART #") "CRCW060310K0FKEA")
        (field (name "PACKAGE") "0603")
      )
      (libsource (lib "TG21_TX_Ma tran phimPrjPcb") (part "0603 10K"))
    )
    (comp (ref "R99")
      (value "10K")
      (footprint "0603 Resistors")
      (description "100mW 10kΩ 75V Thick Film Resistor ±1% ±100ppm/℃ 0603 Chip Resistor - Surface Mount RoHS")
      (fields
        (field (name "MANUFACTURER") "VISHAY")
        (field (name "MFR. PART #") "CRCW060310K0FKEA")
        (field (name "PACKAGE") "0603")
      )
      (libsource (lib "TG21_TX_Ma tran phimPrjPcb") (part "0603 10K"))
    )
    (comp (ref "R100")
      (value "10K")
      (footprint "0603 Resistors")
      (description "100mW 10kΩ 75V Thick Film Resistor ±1% ±100ppm/℃ 0603 Chip Resistor - Surface Mount RoHS")
      (fields
        (field (name "MANUFACTURER") "VISHAY")
        (field (name "MFR. PART #") "CRCW060310K0FKEA")
        (field (name "PACKAGE") "0603")
      )
      (libsource (lib "TG21_TX_Ma tran phimPrjPcb") (part "0603 10K"))
    )
    (comp (ref "R101")
      (value "10K")
      (footprint "0603 Resistors")
      (description "100mW 10kΩ 75V Thick Film Resistor ±1% ±100ppm/℃ 0603 Chip Resistor - Surface Mount RoHS")
      (fields
        (field (name "MANUFACTURER") "VISHAY")
        (field (name "MFR. PART #") "CRCW060310K0FKEA")
        (field (name "PACKAGE") "0603")
      )
      (libsource (lib "TG21_TX_Ma tran phimPrjPcb") (part "0603 10K"))
    )
    (comp (ref "R102")
      (value "10K")
      (footprint "0603 Resistors")
      (description "100mW 10kΩ 75V Thick Film Resistor ±1% ±100ppm/℃ 0603 Chip Resistor - Surface Mount RoHS")
      (fields
        (field (name "MANUFACTURER") "VISHAY")
        (field (name "MFR. PART #") "CRCW060310K0FKEA")
        (field (name "PACKAGE") "0603")
      )
      (libsource (lib "TG21_TX_Ma tran phimPrjPcb") (part "0603 10K"))
    )
    (comp (ref "R103")
      (value "10K")
      (footprint "0603 Resistors")
      (description "100mW 10kΩ 75V Thick Film Resistor ±1% ±100ppm/℃ 0603 Chip Resistor - Surface Mount RoHS")
      (fields
        (field (name "MANUFACTURER") "VISHAY")
        (field (name "MFR. PART #") "CRCW060310K0FKEA")
        (field (name "PACKAGE") "0603")
      )
      (libsource (lib "TG21_TX_Ma tran phimPrjPcb") (part "0603 10K"))
    )
    (comp (ref "R104")
      (value "10K")
      (footprint "0603 Resistors")
      (description "100mW 10kΩ 75V Thick Film Resistor ±1% ±100ppm/℃ 0603 Chip Resistor - Surface Mount RoHS")
      (fields
        (field (name "MANUFACTURER") "VISHAY")
        (field (name "MFR. PART #") "CRCW060310K0FKEA")
        (field (name "PACKAGE") "0603")
      )
      (libsource (lib "TG21_TX_Ma tran phimPrjPcb") (part "0603 10K"))
    )
    (comp (ref "R105")
      (value "220R")
      (footprint "0603 MLCC")
      (description "100mW 220Ω 75V Thick Film Resistor ±1% ±100ppm/℃ 0603 Chip Resistor - Surface Mount RoHS")
      (fields
        (field (name "MFR. PART #") "CRCW0603220RFKEAHP")
        (field (name "LCSC PART #") "C313707")
        (field (name "PACKAGE") "0603")
      )
      (libsource (lib "TG21_TX_Ma tran phimPrjPcb") (part "0603 220R"))
    )
    (comp (ref "R106")
      (value "220R")
      (footprint "0603 MLCC")
      (description "100mW 220Ω 75V Thick Film Resistor ±1% ±100ppm/℃ 0603 Chip Resistor - Surface Mount RoHS")
      (fields
        (field (name "MFR. PART #") "CRCW0603220RFKEAHP")
        (field (name "LCSC PART #") "C313707")
        (field (name "PACKAGE") "0603")
      )
      (libsource (lib "TG21_TX_Ma tran phimPrjPcb") (part "0603 220R"))
    )
    (comp (ref "R107")
      (value "220R")
      (footprint "0603 MLCC")
      (description "100mW 220Ω 75V Thick Film Resistor ±1% ±100ppm/℃ 0603 Chip Resistor - Surface Mount RoHS")
      (fields
        (field (name "MFR. PART #") "CRCW0603220RFKEAHP")
        (field (name "LCSC PART #") "C313707")
        (field (name "PACKAGE") "0603")
      )
      (libsource (lib "TG21_TX_Ma tran phimPrjPcb") (part "0603 220R"))
    )
    (comp (ref "R108")
      (value "220R")
      (footprint "0603 MLCC")
      (description "100mW 220Ω 75V Thick Film Resistor ±1% ±100ppm/℃ 0603 Chip Resistor - Surface Mount RoHS")
      (fields
        (field (name "MFR. PART #") "CRCW0603220RFKEAHP")
        (field (name "LCSC PART #") "C313707")
        (field (name "PACKAGE") "0603")
      )
      (libsource (lib "TG21_TX_Ma tran phimPrjPcb") (part "0603 220R"))
    )
    (comp (ref "R109")
      (value "220R")
      (footprint "0603 MLCC")
      (description "100mW 220Ω 75V Thick Film Resistor ±1% ±100ppm/℃ 0603 Chip Resistor - Surface Mount RoHS")
      (fields
        (field (name "MFR. PART #") "CRCW0603220RFKEAHP")
        (field (name "LCSC PART #") "C313707")
        (field (name "PACKAGE") "0603")
      )
      (libsource (lib "TG21_TX_Ma tran phimPrjPcb") (part "0603 220R"))
    )
    (comp (ref "R110")
      (value "220R")
      (footprint "0603 MLCC")
      (description "100mW 220Ω 75V Thick Film Resistor ±1% ±100ppm/℃ 0603 Chip Resistor - Surface Mount RoHS")
      (fields
        (field (name "MFR. PART #") "CRCW0603220RFKEAHP")
        (field (name "LCSC PART #") "C313707")
        (field (name "PACKAGE") "0603")
      )
      (libsource (lib "TG21_TX_Ma tran phimPrjPcb") (part "0603 220R"))
    )
    (comp (ref "R111")
      (value "220R")
      (footprint "0603 MLCC")
      (description "100mW 220Ω 75V Thick Film Resistor ±1% ±100ppm/℃ 0603 Chip Resistor - Surface Mount RoHS")
      (fields
        (field (name "MFR. PART #") "CRCW0603220RFKEAHP")
        (field (name "LCSC PART #") "C313707")
        (field (name "PACKAGE") "0603")
      )
      (libsource (lib "TG21_TX_Ma tran phimPrjPcb") (part "0603 220R"))
    )
    (comp (ref "R112")
      (value "220R")
      (footprint "0603 MLCC")
      (description "100mW 220Ω 75V Thick Film Resistor ±1% ±100ppm/℃ 0603 Chip Resistor - Surface Mount RoHS")
      (fields
        (field (name "MFR. PART #") "CRCW0603220RFKEAHP")
        (field (name "LCSC PART #") "C313707")
        (field (name "PACKAGE") "0603")
      )
      (libsource (lib "TG21_TX_Ma tran phimPrjPcb") (part "0603 220R"))
    )
    (comp (ref "R113")
      (value "220R")
      (footprint "0603 MLCC")
      (description "100mW 220Ω 75V Thick Film Resistor ±1% ±100ppm/℃ 0603 Chip Resistor - Surface Mount RoHS")
      (fields
        (field (name "MFR. PART #") "CRCW0603220RFKEAHP")
        (field (name "LCSC PART #") "C313707")
        (field (name "PACKAGE") "0603")
      )
      (libsource (lib "TG21_TX_Ma tran phimPrjPcb") (part "0603 220R"))
    )
    (comp (ref "R114")
      (value "220R")
      (footprint "0603 MLCC")
      (description "100mW 220Ω 75V Thick Film Resistor ±1% ±100ppm/℃ 0603 Chip Resistor - Surface Mount RoHS")
      (fields
        (field (name "MFR. PART #") "CRCW0603220RFKEAHP")
        (field (name "LCSC PART #") "C313707")
        (field (name "PACKAGE") "0603")
      )
      (libsource (lib "TG21_TX_Ma tran phimPrjPcb") (part "0603 220R"))
    )
    (comp (ref "R115")
      (value "220R")
      (footprint "0603 MLCC")
      (description "100mW 220Ω 75V Thick Film Resistor ±1% ±100ppm/℃ 0603 Chip Resistor - Surface Mount RoHS")
      (fields
        (field (name "MFR. PART #") "CRCW0603220RFKEAHP")
        (field (name "LCSC PART #") "C313707")
        (field (name "PACKAGE") "0603")
      )
      (libsource (lib "TG21_TX_Ma tran phimPrjPcb") (part "0603 220R"))
    )
    (comp (ref "R116")
      (value "220R")
      (footprint "0603 MLCC")
      (description "100mW 220Ω 75V Thick Film Resistor ±1% ±100ppm/℃ 0603 Chip Resistor - Surface Mount RoHS")
      (fields
        (field (name "MFR. PART #") "CRCW0603220RFKEAHP")
        (field (name "LCSC PART #") "C313707")
        (field (name "PACKAGE") "0603")
      )
      (libsource (lib "TG21_TX_Ma tran phimPrjPcb") (part "0603 220R"))
    )
    (comp (ref "R117")
      (value "220R")
      (footprint "0603 MLCC")
      (description "100mW 220Ω 75V Thick Film Resistor ±1% ±100ppm/℃ 0603 Chip Resistor - Surface Mount RoHS")
      (fields
        (field (name "MFR. PART #") "CRCW0603220RFKEAHP")
        (field (name "LCSC PART #") "C313707")
        (field (name "PACKAGE") "0603")
      )
      (libsource (lib "TG21_TX_Ma tran phimPrjPcb") (part "0603 220R"))
    )
    (comp (ref "R118")
      (value "10K")
      (footprint "0603 Resistors")
      (description "100mW 10kΩ 75V Thick Film Resistor ±1% ±100ppm/℃ 0603 Chip Resistor - Surface Mount RoHS")
      (fields
        (field (name "MANUFACTURER") "VISHAY")
        (field (name "MFR. PART #") "CRCW060310K0FKEA")
        (field (name "PACKAGE") "0603")
      )
      (libsource (lib "TG21_TX_Ma tran phimPrjPcb") (part "0603 10K"))
    )
    (comp (ref "R119")
      (value "10K")
      (footprint "0603 Resistors")
      (description "100mW 10kΩ 75V Thick Film Resistor ±1% ±100ppm/℃ 0603 Chip Resistor - Surface Mount RoHS")
      (fields
        (field (name "MANUFACTURER") "VISHAY")
        (field (name "MFR. PART #") "CRCW060310K0FKEA")
        (field (name "PACKAGE") "0603")
      )
      (libsource (lib "TG21_TX_Ma tran phimPrjPcb") (part "0603 10K"))
    )
    (comp (ref "R120")
      (value "10K")
      (footprint "0603 Resistors")
      (description "100mW 10kΩ 75V Thick Film Resistor ±1% ±100ppm/℃ 0603 Chip Resistor - Surface Mount RoHS")
      (fields
        (field (name "MANUFACTURER") "VISHAY")
        (field (name "MFR. PART #") "CRCW060310K0FKEA")
        (field (name "PACKAGE") "0603")
      )
      (libsource (lib "TG21_TX_Ma tran phimPrjPcb") (part "0603 10K"))
    )
    (comp (ref "R121")
      (value "10K")
      (footprint "0603 Resistors")
      (description "100mW 10kΩ 75V Thick Film Resistor ±1% ±100ppm/℃ 0603 Chip Resistor - Surface Mount RoHS")
      (fields
        (field (name "MANUFACTURER") "VISHAY")
        (field (name "MFR. PART #") "CRCW060310K0FKEA")
        (field (name "PACKAGE") "0603")
      )
      (libsource (lib "TG21_TX_Ma tran phimPrjPcb") (part "0603 10K"))
    )
    (comp (ref "R122")
      (value "10K")
      (footprint "0603 Resistors")
      (description "100mW 10kΩ 75V Thick Film Resistor ±1% ±100ppm/℃ 0603 Chip Resistor - Surface Mount RoHS")
      (fields
        (field (name "MANUFACTURER") "VISHAY")
        (field (name "MFR. PART #") "CRCW060310K0FKEA")
        (field (name "PACKAGE") "0603")
      )
      (libsource (lib "TG21_TX_Ma tran phimPrjPcb") (part "0603 10K"))
    )
    (comp (ref "R123")
      (value "10K")
      (footprint "0603 Resistors")
      (description "100mW 10kΩ 75V Thick Film Resistor ±1% ±100ppm/℃ 0603 Chip Resistor - Surface Mount RoHS")
      (fields
        (field (name "MANUFACTURER") "VISHAY")
        (field (name "MFR. PART #") "CRCW060310K0FKEA")
        (field (name "PACKAGE") "0603")
      )
      (libsource (lib "TG21_TX_Ma tran phimPrjPcb") (part "0603 10K"))
    )
    (comp (ref "R124")
      (value "10K")
      (footprint "0603 Resistors")
      (description "100mW 10kΩ 75V Thick Film Resistor ±1% ±100ppm/℃ 0603 Chip Resistor - Surface Mount RoHS")
      (fields
        (field (name "MANUFACTURER") "VISHAY")
        (field (name "MFR. PART #") "CRCW060310K0FKEA")
        (field (name "PACKAGE") "0603")
      )
      (libsource (lib "TG21_TX_Ma tran phimPrjPcb") (part "0603 10K"))
    )
    (comp (ref "R125")
      (value "10K")
      (footprint "0603 Resistors")
      (description "100mW 10kΩ 75V Thick Film Resistor ±1% ±100ppm/℃ 0603 Chip Resistor - Surface Mount RoHS")
      (fields
        (field (name "MANUFACTURER") "VISHAY")
        (field (name "MFR. PART #") "CRCW060310K0FKEA")
        (field (name "PACKAGE") "0603")
      )
      (libsource (lib "TG21_TX_Ma tran phimPrjPcb") (part "0603 10K"))
    )
    (comp (ref "R126")
      (value "10K")
      (footprint "0603 Resistors")
      (description "100mW 10kΩ 75V Thick Film Resistor ±1% ±100ppm/℃ 0603 Chip Resistor - Surface Mount RoHS")
      (fields
        (field (name "MANUFACTURER") "VISHAY")
        (field (name "MFR. PART #") "CRCW060310K0FKEA")
        (field (name "PACKAGE") "0603")
      )
      (libsource (lib "TG21_TX_Ma tran phimPrjPcb") (part "0603 10K"))
    )
    (comp (ref "R127")
      (value "10K")
      (footprint "0603 Resistors")
      (description "100mW 10kΩ 75V Thick Film Resistor ±1% ±100ppm/℃ 0603 Chip Resistor - Surface Mount RoHS")
      (fields
        (field (name "MANUFACTURER") "VISHAY")
        (field (name "MFR. PART #") "CRCW060310K0FKEA")
        (field (name "PACKAGE") "0603")
      )
      (libsource (lib "TG21_TX_Ma tran phimPrjPcb") (part "0603 10K"))
    )
    (comp (ref "R128")
      (value "10K")
      (footprint "0603 Resistors")
      (description "100mW 10kΩ 75V Thick Film Resistor ±1% ±100ppm/℃ 0603 Chip Resistor - Surface Mount RoHS")
      (fields
        (field (name "MANUFACTURER") "VISHAY")
        (field (name "MFR. PART #") "CRCW060310K0FKEA")
        (field (name "PACKAGE") "0603")
      )
      (libsource (lib "TG21_TX_Ma tran phimPrjPcb") (part "0603 10K"))
    )
    (comp (ref "R129")
      (value "10K")
      (footprint "0603 Resistors")
      (description "100mW 10kΩ 75V Thick Film Resistor ±1% ±100ppm/℃ 0603 Chip Resistor - Surface Mount RoHS")
      (fields
        (field (name "MANUFACTURER") "VISHAY")
        (field (name "MFR. PART #") "CRCW060310K0FKEA")
        (field (name "PACKAGE") "0603")
      )
      (libsource (lib "TG21_TX_Ma tran phimPrjPcb") (part "0603 10K"))
    )
    (comp (ref "R130")
      (value "10K")
      (footprint "0603 Resistors")
      (description "100mW 10kΩ 75V Thick Film Resistor ±1% ±100ppm/℃ 0603 Chip Resistor - Surface Mount RoHS")
      (fields
        (field (name "MANUFACTURER") "VISHAY")
        (field (name "MFR. PART #") "CRCW060310K0FKEA")
        (field (name "PACKAGE") "0603")
      )
      (libsource (lib "TG21_TX_Ma tran phimPrjPcb") (part "0603 10K"))
    )
    (comp (ref "R131")
      (value "220R")
      (footprint "0603 MLCC")
      (description "100mW 220Ω 75V Thick Film Resistor ±1% ±100ppm/℃ 0603 Chip Resistor - Surface Mount RoHS")
      (fields
        (field (name "MFR. PART #") "CRCW0603220RFKEAHP")
        (field (name "LCSC PART #") "C313707")
        (field (name "PACKAGE") "0603")
      )
      (libsource (lib "TG21_TX_Ma tran phimPrjPcb") (part "0603 220R"))
    )
    (comp (ref "R132")
      (value "220R")
      (footprint "0603 MLCC")
      (description "100mW 220Ω 75V Thick Film Resistor ±1% ±100ppm/℃ 0603 Chip Resistor - Surface Mount RoHS")
      (fields
        (field (name "MFR. PART #") "CRCW0603220RFKEAHP")
        (field (name "LCSC PART #") "C313707")
        (field (name "PACKAGE") "0603")
      )
      (libsource (lib "TG21_TX_Ma tran phimPrjPcb") (part "0603 220R"))
    )
    (comp (ref "R133")
      (value "220R")
      (footprint "0603 MLCC")
      (description "100mW 220Ω 75V Thick Film Resistor ±1% ±100ppm/℃ 0603 Chip Resistor - Surface Mount RoHS")
      (fields
        (field (name "MFR. PART #") "CRCW0603220RFKEAHP")
        (field (name "LCSC PART #") "C313707")
        (field (name "PACKAGE") "0603")
      )
      (libsource (lib "TG21_TX_Ma tran phimPrjPcb") (part "0603 220R"))
    )
    (comp (ref "R134")
      (value "220R")
      (footprint "0603 MLCC")
      (description "100mW 220Ω 75V Thick Film Resistor ±1% ±100ppm/℃ 0603 Chip Resistor - Surface Mount RoHS")
      (fields
        (field (name "MFR. PART #") "CRCW0603220RFKEAHP")
        (field (name "LCSC PART #") "C313707")
        (field (name "PACKAGE") "0603")
      )
      (libsource (lib "TG21_TX_Ma tran phimPrjPcb") (part "0603 220R"))
    )
    (comp (ref "R135")
      (value "220R")
      (footprint "0603 MLCC")
      (description "100mW 220Ω 75V Thick Film Resistor ±1% ±100ppm/℃ 0603 Chip Resistor - Surface Mount RoHS")
      (fields
        (field (name "MFR. PART #") "CRCW0603220RFKEAHP")
        (field (name "LCSC PART #") "C313707")
        (field (name "PACKAGE") "0603")
      )
      (libsource (lib "TG21_TX_Ma tran phimPrjPcb") (part "0603 220R"))
    )
    (comp (ref "R136")
      (value "220R")
      (footprint "0603 MLCC")
      (description "100mW 220Ω 75V Thick Film Resistor ±1% ±100ppm/℃ 0603 Chip Resistor - Surface Mount RoHS")
      (fields
        (field (name "MFR. PART #") "CRCW0603220RFKEAHP")
        (field (name "LCSC PART #") "C313707")
        (field (name "PACKAGE") "0603")
      )
      (libsource (lib "TG21_TX_Ma tran phimPrjPcb") (part "0603 220R"))
    )
    (comp (ref "R137")
      (value "220R")
      (footprint "0603 MLCC")
      (description "100mW 220Ω 75V Thick Film Resistor ±1% ±100ppm/℃ 0603 Chip Resistor - Surface Mount RoHS")
      (fields
        (field (name "MFR. PART #") "CRCW0603220RFKEAHP")
        (field (name "LCSC PART #") "C313707")
        (field (name "PACKAGE") "0603")
      )
      (libsource (lib "TG21_TX_Ma tran phimPrjPcb") (part "0603 220R"))
    )
    (comp (ref "R138")
      (value "220R")
      (footprint "0603 MLCC")
      (description "100mW 220Ω 75V Thick Film Resistor ±1% ±100ppm/℃ 0603 Chip Resistor - Surface Mount RoHS")
      (fields
        (field (name "MFR. PART #") "CRCW0603220RFKEAHP")
        (field (name "LCSC PART #") "C313707")
        (field (name "PACKAGE") "0603")
      )
      (libsource (lib "TG21_TX_Ma tran phimPrjPcb") (part "0603 220R"))
    )
    (comp (ref "R139")
      (value "220R")
      (footprint "0603 MLCC")
      (description "100mW 220Ω 75V Thick Film Resistor ±1% ±100ppm/℃ 0603 Chip Resistor - Surface Mount RoHS")
      (fields
        (field (name "MFR. PART #") "CRCW0603220RFKEAHP")
        (field (name "LCSC PART #") "C313707")
        (field (name "PACKAGE") "0603")
      )
      (libsource (lib "TG21_TX_Ma tran phimPrjPcb") (part "0603 220R"))
    )
    (comp (ref "R140")
      (value "220R")
      (footprint "0603 MLCC")
      (description "100mW 220Ω 75V Thick Film Resistor ±1% ±100ppm/℃ 0603 Chip Resistor - Surface Mount RoHS")
      (fields
        (field (name "MFR. PART #") "CRCW0603220RFKEAHP")
        (field (name "LCSC PART #") "C313707")
        (field (name "PACKAGE") "0603")
      )
      (libsource (lib "TG21_TX_Ma tran phimPrjPcb") (part "0603 220R"))
    )
    (comp (ref "R141")
      (value "220R")
      (footprint "0603 MLCC")
      (description "100mW 220Ω 75V Thick Film Resistor ±1% ±100ppm/℃ 0603 Chip Resistor - Surface Mount RoHS")
      (fields
        (field (name "MFR. PART #") "CRCW0603220RFKEAHP")
        (field (name "LCSC PART #") "C313707")
        (field (name "PACKAGE") "0603")
      )
      (libsource (lib "TG21_TX_Ma tran phimPrjPcb") (part "0603 220R"))
    )
    (comp (ref "R142")
      (value "220R")
      (footprint "0603 MLCC")
      (description "100mW 220Ω 75V Thick Film Resistor ±1% ±100ppm/℃ 0603 Chip Resistor - Surface Mount RoHS")
      (fields
        (field (name "MFR. PART #") "CRCW0603220RFKEAHP")
        (field (name "LCSC PART #") "C313707")
        (field (name "PACKAGE") "0603")
      )
      (libsource (lib "TG21_TX_Ma tran phimPrjPcb") (part "0603 220R"))
    )
    (comp (ref "R143")
      (value "220R")
      (footprint "0603 MLCC")
      (description "100mW 220Ω 75V Thick Film Resistor ±1% ±100ppm/℃ 0603 Chip Resistor - Surface Mount RoHS")
      (fields
        (field (name "MFR. PART #") "CRCW0603220RFKEAHP")
        (field (name "LCSC PART #") "C313707")
        (field (name "PACKAGE") "0603")
      )
      (libsource (lib "TG21_TX_Ma tran phimPrjPcb") (part "0603 220R"))
    )
    (comp (ref "R144")
      (value "10K")
      (footprint "0603 Resistors")
      (description "100mW 10kΩ 75V Thick Film Resistor ±1% ±100ppm/℃ 0603 Chip Resistor - Surface Mount RoHS")
      (fields
        (field (name "MANUFACTURER") "VISHAY")
        (field (name "MFR. PART #") "CRCW060310K0FKEA")
        (field (name "PACKAGE") "0603")
      )
      (libsource (lib "TG21_TX_Ma tran phimPrjPcb") (part "0603 10K"))
    )
    (comp (ref "R145")
      (value "10K")
      (footprint "0603 Resistors")
      (description "100mW 10kΩ 75V Thick Film Resistor ±1% ±100ppm/℃ 0603 Chip Resistor - Surface Mount RoHS")
      (fields
        (field (name "MANUFACTURER") "VISHAY")
        (field (name "MFR. PART #") "CRCW060310K0FKEA")
        (field (name "PACKAGE") "0603")
      )
      (libsource (lib "TG21_TX_Ma tran phimPrjPcb") (part "0603 10K"))
    )
    (comp (ref "R146")
      (value "10K")
      (footprint "0603 Resistors")
      (description "100mW 10kΩ 75V Thick Film Resistor ±1% ±100ppm/℃ 0603 Chip Resistor - Surface Mount RoHS")
      (fields
        (field (name "MANUFACTURER") "VISHAY")
        (field (name "MFR. PART #") "CRCW060310K0FKEA")
        (field (name "PACKAGE") "0603")
      )
      (libsource (lib "TG21_TX_Ma tran phimPrjPcb") (part "0603 10K"))
    )
    (comp (ref "R147")
      (value "10K")
      (footprint "0603 Resistors")
      (description "100mW 10kΩ 75V Thick Film Resistor ±1% ±100ppm/℃ 0603 Chip Resistor - Surface Mount RoHS")
      (fields
        (field (name "MANUFACTURER") "VISHAY")
        (field (name "MFR. PART #") "CRCW060310K0FKEA")
        (field (name "PACKAGE") "0603")
      )
      (libsource (lib "TG21_TX_Ma tran phimPrjPcb") (part "0603 10K"))
    )
    (comp (ref "R148")
      (value "10K")
      (footprint "0603 Resistors")
      (description "100mW 10kΩ 75V Thick Film Resistor ±1% ±100ppm/℃ 0603 Chip Resistor - Surface Mount RoHS")
      (fields
        (field (name "MANUFACTURER") "VISHAY")
        (field (name "MFR. PART #") "CRCW060310K0FKEA")
        (field (name "PACKAGE") "0603")
      )
      (libsource (lib "TG21_TX_Ma tran phimPrjPcb") (part "0603 10K"))
    )
    (comp (ref "R149")
      (value "10K")
      (footprint "0603 Resistors")
      (description "100mW 10kΩ 75V Thick Film Resistor ±1% ±100ppm/℃ 0603 Chip Resistor - Surface Mount RoHS")
      (fields
        (field (name "MANUFACTURER") "VISHAY")
        (field (name "MFR. PART #") "CRCW060310K0FKEA")
        (field (name "PACKAGE") "0603")
      )
      (libsource (lib "TG21_TX_Ma tran phimPrjPcb") (part "0603 10K"))
    )
    (comp (ref "R150")
      (value "10K")
      (footprint "0603 Resistors")
      (description "100mW 10kΩ 75V Thick Film Resistor ±1% ±100ppm/℃ 0603 Chip Resistor - Surface Mount RoHS")
      (fields
        (field (name "MANUFACTURER") "VISHAY")
        (field (name "MFR. PART #") "CRCW060310K0FKEA")
        (field (name "PACKAGE") "0603")
      )
      (libsource (lib "TG21_TX_Ma tran phimPrjPcb") (part "0603 10K"))
    )
    (comp (ref "R151")
      (value "10K")
      (footprint "0603 Resistors")
      (description "100mW 10kΩ 75V Thick Film Resistor ±1% ±100ppm/℃ 0603 Chip Resistor - Surface Mount RoHS")
      (fields
        (field (name "MANUFACTURER") "VISHAY")
        (field (name "MFR. PART #") "CRCW060310K0FKEA")
        (field (name "PACKAGE") "0603")
      )
      (libsource (lib "TG21_TX_Ma tran phimPrjPcb") (part "0603 10K"))
    )
    (comp (ref "R152")
      (value "10K")
      (footprint "0603 Resistors")
      (description "100mW 10kΩ 75V Thick Film Resistor ±1% ±100ppm/℃ 0603 Chip Resistor - Surface Mount RoHS")
      (fields
        (field (name "MANUFACTURER") "VISHAY")
        (field (name "MFR. PART #") "CRCW060310K0FKEA")
        (field (name "PACKAGE") "0603")
      )
      (libsource (lib "TG21_TX_Ma tran phimPrjPcb") (part "0603 10K"))
    )
    (comp (ref "R153")
      (value "10K")
      (footprint "0603 Resistors")
      (description "100mW 10kΩ 75V Thick Film Resistor ±1% ±100ppm/℃ 0603 Chip Resistor - Surface Mount RoHS")
      (fields
        (field (name "MANUFACTURER") "VISHAY")
        (field (name "MFR. PART #") "CRCW060310K0FKEA")
        (field (name "PACKAGE") "0603")
      )
      (libsource (lib "TG21_TX_Ma tran phimPrjPcb") (part "0603 10K"))
    )
    (comp (ref "R154")
      (value "10K")
      (footprint "0603 Resistors")
      (description "100mW 10kΩ 75V Thick Film Resistor ±1% ±100ppm/℃ 0603 Chip Resistor - Surface Mount RoHS")
      (fields
        (field (name "MANUFACTURER") "VISHAY")
        (field (name "MFR. PART #") "CRCW060310K0FKEA")
        (field (name "PACKAGE") "0603")
      )
      (libsource (lib "TG21_TX_Ma tran phimPrjPcb") (part "0603 10K"))
    )
    (comp (ref "R155")
      (value "10K")
      (footprint "0603 Resistors")
      (description "100mW 10kΩ 75V Thick Film Resistor ±1% ±100ppm/℃ 0603 Chip Resistor - Surface Mount RoHS")
      (fields
        (field (name "MANUFACTURER") "VISHAY")
        (field (name "MFR. PART #") "CRCW060310K0FKEA")
        (field (name "PACKAGE") "0603")
      )
      (libsource (lib "TG21_TX_Ma tran phimPrjPcb") (part "0603 10K"))
    )
    (comp (ref "R156")
      (value "10K")
      (footprint "0603 Resistors")
      (description "100mW 10kΩ 75V Thick Film Resistor ±1% ±100ppm/℃ 0603 Chip Resistor - Surface Mount RoHS")
      (fields
        (field (name "MANUFACTURER") "VISHAY")
        (field (name "MFR. PART #") "CRCW060310K0FKEA")
        (field (name "PACKAGE") "0603")
      )
      (libsource (lib "TG21_TX_Ma tran phimPrjPcb") (part "0603 10K"))
    )
    (comp (ref "R157")
      (value "220R")
      (footprint "0603 MLCC")
      (description "100mW 220Ω 75V Thick Film Resistor ±1% ±100ppm/℃ 0603 Chip Resistor - Surface Mount RoHS")
      (fields
        (field (name "MFR. PART #") "CRCW0603220RFKEAHP")
        (field (name "LCSC PART #") "C313707")
        (field (name "PACKAGE") "0603")
      )
      (libsource (lib "TG21_TX_Ma tran phimPrjPcb") (part "0603 220R"))
    )
    (comp (ref "R158")
      (value "220R")
      (footprint "0603 MLCC")
      (description "100mW 220Ω 75V Thick Film Resistor ±1% ±100ppm/℃ 0603 Chip Resistor - Surface Mount RoHS")
      (fields
        (field (name "MFR. PART #") "CRCW0603220RFKEAHP")
        (field (name "LCSC PART #") "C313707")
        (field (name "PACKAGE") "0603")
      )
      (libsource (lib "TG21_TX_Ma tran phimPrjPcb") (part "0603 220R"))
    )
    (comp (ref "R159")
      (value "220R")
      (footprint "0603 MLCC")
      (description "100mW 220Ω 75V Thick Film Resistor ±1% ±100ppm/℃ 0603 Chip Resistor - Surface Mount RoHS")
      (fields
        (field (name "MFR. PART #") "CRCW0603220RFKEAHP")
        (field (name "LCSC PART #") "C313707")
        (field (name "PACKAGE") "0603")
      )
      (libsource (lib "TG21_TX_Ma tran phimPrjPcb") (part "0603 220R"))
    )
    (comp (ref "R160")
      (value "220R")
      (footprint "0603 MLCC")
      (description "100mW 220Ω 75V Thick Film Resistor ±1% ±100ppm/℃ 0603 Chip Resistor - Surface Mount RoHS")
      (fields
        (field (name "MFR. PART #") "CRCW0603220RFKEAHP")
        (field (name "LCSC PART #") "C313707")
        (field (name "PACKAGE") "0603")
      )
      (libsource (lib "TG21_TX_Ma tran phimPrjPcb") (part "0603 220R"))
    )
    (comp (ref "R161")
      (value "220R")
      (footprint "0603 MLCC")
      (description "100mW 220Ω 75V Thick Film Resistor ±1% ±100ppm/℃ 0603 Chip Resistor - Surface Mount RoHS")
      (fields
        (field (name "MFR. PART #") "CRCW0603220RFKEAHP")
        (field (name "LCSC PART #") "C313707")
        (field (name "PACKAGE") "0603")
      )
      (libsource (lib "TG21_TX_Ma tran phimPrjPcb") (part "0603 220R"))
    )
    (comp (ref "R162")
      (value "220R")
      (footprint "0603 MLCC")
      (description "100mW 220Ω 75V Thick Film Resistor ±1% ±100ppm/℃ 0603 Chip Resistor - Surface Mount RoHS")
      (fields
        (field (name "MFR. PART #") "CRCW0603220RFKEAHP")
        (field (name "LCSC PART #") "C313707")
        (field (name "PACKAGE") "0603")
      )
      (libsource (lib "TG21_TX_Ma tran phimPrjPcb") (part "0603 220R"))
    )
    (comp (ref "R163")
      (value "220R")
      (footprint "0603 MLCC")
      (description "100mW 220Ω 75V Thick Film Resistor ±1% ±100ppm/℃ 0603 Chip Resistor - Surface Mount RoHS")
      (fields
        (field (name "MFR. PART #") "CRCW0603220RFKEAHP")
        (field (name "LCSC PART #") "C313707")
        (field (name "PACKAGE") "0603")
      )
      (libsource (lib "TG21_TX_Ma tran phimPrjPcb") (part "0603 220R"))
    )
    (comp (ref "R164")
      (value "220R")
      (footprint "0603 MLCC")
      (description "100mW 220Ω 75V Thick Film Resistor ±1% ±100ppm/℃ 0603 Chip Resistor - Surface Mount RoHS")
      (fields
        (field (name "MFR. PART #") "CRCW0603220RFKEAHP")
        (field (name "LCSC PART #") "C313707")
        (field (name "PACKAGE") "0603")
      )
      (libsource (lib "TG21_TX_Ma tran phimPrjPcb") (part "0603 220R"))
    )
    (comp (ref "R165")
      (value "220R")
      (footprint "0603 MLCC")
      (description "100mW 220Ω 75V Thick Film Resistor ±1% ±100ppm/℃ 0603 Chip Resistor - Surface Mount RoHS")
      (fields
        (field (name "MFR. PART #") "CRCW0603220RFKEAHP")
        (field (name "LCSC PART #") "C313707")
        (field (name "PACKAGE") "0603")
      )
      (libsource (lib "TG21_TX_Ma tran phimPrjPcb") (part "0603 220R"))
    )
    (comp (ref "R166")
      (value "220R")
      (footprint "0603 MLCC")
      (description "100mW 220Ω 75V Thick Film Resistor ±1% ±100ppm/℃ 0603 Chip Resistor - Surface Mount RoHS")
      (fields
        (field (name "MFR. PART #") "CRCW0603220RFKEAHP")
        (field (name "LCSC PART #") "C313707")
        (field (name "PACKAGE") "0603")
      )
      (libsource (lib "TG21_TX_Ma tran phimPrjPcb") (part "0603 220R"))
    )
    (comp (ref "R167")
      (value "220R")
      (footprint "0603 MLCC")
      (description "100mW 220Ω 75V Thick Film Resistor ±1% ±100ppm/℃ 0603 Chip Resistor - Surface Mount RoHS")
      (fields
        (field (name "MFR. PART #") "CRCW0603220RFKEAHP")
        (field (name "LCSC PART #") "C313707")
        (field (name "PACKAGE") "0603")
      )
      (libsource (lib "TG21_TX_Ma tran phimPrjPcb") (part "0603 220R"))
    )
    (comp (ref "R168")
      (value "220R")
      (footprint "0603 MLCC")
      (description "100mW 220Ω 75V Thick Film Resistor ±1% ±100ppm/℃ 0603 Chip Resistor - Surface Mount RoHS")
      (fields
        (field (name "MFR. PART #") "CRCW0603220RFKEAHP")
        (field (name "LCSC PART #") "C313707")
        (field (name "PACKAGE") "0603")
      )
      (libsource (lib "TG21_TX_Ma tran phimPrjPcb") (part "0603 220R"))
    )
    (comp (ref "R169")
      (value "220R")
      (footprint "0603 MLCC")
      (description "100mW 220Ω 75V Thick Film Resistor ±1% ±100ppm/℃ 0603 Chip Resistor - Surface Mount RoHS")
      (fields
        (field (name "MFR. PART #") "CRCW0603220RFKEAHP")
        (field (name "LCSC PART #") "C313707")
        (field (name "PACKAGE") "0603")
      )
      (libsource (lib "TG21_TX_Ma tran phimPrjPcb") (part "0603 220R"))
    )
    (comp (ref "R170")
      (value "10K")
      (footprint "0603 Resistors")
      (description "100mW 10kΩ 75V Thick Film Resistor ±1% ±100ppm/℃ 0603 Chip Resistor - Surface Mount RoHS")
      (fields
        (field (name "MANUFACTURER") "VISHAY")
        (field (name "MFR. PART #") "CRCW060310K0FKEA")
        (field (name "PACKAGE") "0603")
      )
      (libsource (lib "TG21_TX_Ma tran phimPrjPcb") (part "0603 10K"))
    )
    (comp (ref "R171")
      (value "10K")
      (footprint "0603 Resistors")
      (description "100mW 10kΩ 75V Thick Film Resistor ±1% ±100ppm/℃ 0603 Chip Resistor - Surface Mount RoHS")
      (fields
        (field (name "MANUFACTURER") "VISHAY")
        (field (name "MFR. PART #") "CRCW060310K0FKEA")
        (field (name "PACKAGE") "0603")
      )
      (libsource (lib "TG21_TX_Ma tran phimPrjPcb") (part "0603 10K"))
    )
    (comp (ref "R172")
      (value "10K")
      (footprint "0603 Resistors")
      (description "100mW 10kΩ 75V Thick Film Resistor ±1% ±100ppm/℃ 0603 Chip Resistor - Surface Mount RoHS")
      (fields
        (field (name "MANUFACTURER") "VISHAY")
        (field (name "MFR. PART #") "CRCW060310K0FKEA")
        (field (name "PACKAGE") "0603")
      )
      (libsource (lib "TG21_TX_Ma tran phimPrjPcb") (part "0603 10K"))
    )
    (comp (ref "R173")
      (value "10K")
      (footprint "0603 Resistors")
      (description "100mW 10kΩ 75V Thick Film Resistor ±1% ±100ppm/℃ 0603 Chip Resistor - Surface Mount RoHS")
      (fields
        (field (name "MANUFACTURER") "VISHAY")
        (field (name "MFR. PART #") "CRCW060310K0FKEA")
        (field (name "PACKAGE") "0603")
      )
      (libsource (lib "TG21_TX_Ma tran phimPrjPcb") (part "0603 10K"))
    )
    (comp (ref "R174")
      (value "10K")
      (footprint "0603 Resistors")
      (description "100mW 10kΩ 75V Thick Film Resistor ±1% ±100ppm/℃ 0603 Chip Resistor - Surface Mount RoHS")
      (fields
        (field (name "MANUFACTURER") "VISHAY")
        (field (name "MFR. PART #") "CRCW060310K0FKEA")
        (field (name "PACKAGE") "0603")
      )
      (libsource (lib "TG21_TX_Ma tran phimPrjPcb") (part "0603 10K"))
    )
    (comp (ref "R175")
      (value "10K")
      (footprint "0603 Resistors")
      (description "100mW 10kΩ 75V Thick Film Resistor ±1% ±100ppm/℃ 0603 Chip Resistor - Surface Mount RoHS")
      (fields
        (field (name "MANUFACTURER") "VISHAY")
        (field (name "MFR. PART #") "CRCW060310K0FKEA")
        (field (name "PACKAGE") "0603")
      )
      (libsource (lib "TG21_TX_Ma tran phimPrjPcb") (part "0603 10K"))
    )
    (comp (ref "R176")
      (value "10K")
      (footprint "0603 Resistors")
      (description "100mW 10kΩ 75V Thick Film Resistor ±1% ±100ppm/℃ 0603 Chip Resistor - Surface Mount RoHS")
      (fields
        (field (name "MANUFACTURER") "VISHAY")
        (field (name "MFR. PART #") "CRCW060310K0FKEA")
        (field (name "PACKAGE") "0603")
      )
      (libsource (lib "TG21_TX_Ma tran phimPrjPcb") (part "0603 10K"))
    )
    (comp (ref "R177")
      (value "10K")
      (footprint "0603 Resistors")
      (description "100mW 10kΩ 75V Thick Film Resistor ±1% ±100ppm/℃ 0603 Chip Resistor - Surface Mount RoHS")
      (fields
        (field (name "MANUFACTURER") "VISHAY")
        (field (name "MFR. PART #") "CRCW060310K0FKEA")
        (field (name "PACKAGE") "0603")
      )
      (libsource (lib "TG21_TX_Ma tran phimPrjPcb") (part "0603 10K"))
    )
    (comp (ref "R178")
      (value "10K")
      (footprint "0603 Resistors")
      (description "100mW 10kΩ 75V Thick Film Resistor ±1% ±100ppm/℃ 0603 Chip Resistor - Surface Mount RoHS")
      (fields
        (field (name "MANUFACTURER") "VISHAY")
        (field (name "MFR. PART #") "CRCW060310K0FKEA")
        (field (name "PACKAGE") "0603")
      )
      (libsource (lib "TG21_TX_Ma tran phimPrjPcb") (part "0603 10K"))
    )
    (comp (ref "R179")
      (value "10K")
      (footprint "0603 Resistors")
      (description "100mW 10kΩ 75V Thick Film Resistor ±1% ±100ppm/℃ 0603 Chip Resistor - Surface Mount RoHS")
      (fields
        (field (name "MANUFACTURER") "VISHAY")
        (field (name "MFR. PART #") "CRCW060310K0FKEA")
        (field (name "PACKAGE") "0603")
      )
      (libsource (lib "TG21_TX_Ma tran phimPrjPcb") (part "0603 10K"))
    )
    (comp (ref "R180")
      (value "10K")
      (footprint "0603 Resistors")
      (description "100mW 10kΩ 75V Thick Film Resistor ±1% ±100ppm/℃ 0603 Chip Resistor - Surface Mount RoHS")
      (fields
        (field (name "MANUFACTURER") "VISHAY")
        (field (name "MFR. PART #") "CRCW060310K0FKEA")
        (field (name "PACKAGE") "0603")
      )
      (libsource (lib "TG21_TX_Ma tran phimPrjPcb") (part "0603 10K"))
    )
    (comp (ref "R181")
      (value "10K")
      (footprint "0603 Resistors")
      (description "100mW 10kΩ 75V Thick Film Resistor ±1% ±100ppm/℃ 0603 Chip Resistor - Surface Mount RoHS")
      (fields
        (field (name "MANUFACTURER") "VISHAY")
        (field (name "MFR. PART #") "CRCW060310K0FKEA")
        (field (name "PACKAGE") "0603")
      )
      (libsource (lib "TG21_TX_Ma tran phimPrjPcb") (part "0603 10K"))
    )
    (comp (ref "R182")
      (value "10K")
      (footprint "0603 Resistors")
      (description "100mW 10kΩ 75V Thick Film Resistor ±1% ±100ppm/℃ 0603 Chip Resistor - Surface Mount RoHS")
      (fields
        (field (name "MANUFACTURER") "VISHAY")
        (field (name "MFR. PART #") "CRCW060310K0FKEA")
        (field (name "PACKAGE") "0603")
      )
      (libsource (lib "TG21_TX_Ma tran phimPrjPcb") (part "0603 10K"))
    )
    (comp (ref "R183")
      (value "10K")
      (footprint "0603 Resistors")
      (description "100mW 10kΩ 75V Thick Film Resistor ±1% ±100ppm/℃ 0603 Chip Resistor - Surface Mount RoHS")
      (fields
        (field (name "MANUFACTURER") "VISHAY")
        (field (name "MFR. PART #") "CRCW060310K0FKEA")
        (field (name "PACKAGE") "0603")
      )
      (libsource (lib "TG21_TX_Ma tran phimPrjPcb") (part "0603 10K"))
    )
    (comp (ref "R184")
      (value "10K")
      (footprint "0603 Resistors")
      (description "100mW 10kΩ 75V Thick Film Resistor ±1% ±100ppm/℃ 0603 Chip Resistor - Surface Mount RoHS")
      (fields
        (field (name "MANUFACTURER") "VISHAY")
        (field (name "MFR. PART #") "CRCW060310K0FKEA")
        (field (name "PACKAGE") "0603")
      )
      (libsource (lib "TG21_TX_Ma tran phimPrjPcb") (part "0603 10K"))
    )
    (comp (ref "R185")
      (value "10K")
      (footprint "0603 Resistors")
      (description "100mW 10kΩ 75V Thick Film Resistor ±1% ±100ppm/℃ 0603 Chip Resistor - Surface Mount RoHS")
      (fields
        (field (name "MANUFACTURER") "VISHAY")
        (field (name "MFR. PART #") "CRCW060310K0FKEA")
        (field (name "PACKAGE") "0603")
      )
      (libsource (lib "TG21_TX_Ma tran phimPrjPcb") (part "0603 10K"))
    )
    (comp (ref "R186")
      (value "10K")
      (footprint "0603 Resistors")
      (description "100mW 10kΩ 75V Thick Film Resistor ±1% ±100ppm/℃ 0603 Chip Resistor - Surface Mount RoHS")
      (fields
        (field (name "MANUFACTURER") "VISHAY")
        (field (name "MFR. PART #") "CRCW060310K0FKEA")
        (field (name "PACKAGE") "0603")
      )
      (libsource (lib "TG21_TX_Ma tran phimPrjPcb") (part "0603 10K"))
    )
    (comp (ref "R187")
      (value "10K")
      (footprint "0603 Resistors")
      (description "100mW 10kΩ 75V Thick Film Resistor ±1% ±100ppm/℃ 0603 Chip Resistor - Surface Mount RoHS")
      (fields
        (field (name "MANUFACTURER") "VISHAY")
        (field (name "MFR. PART #") "CRCW060310K0FKEA")
        (field (name "PACKAGE") "0603")
      )
      (libsource (lib "TG21_TX_Ma tran phimPrjPcb") (part "0603 10K"))
    )
    (comp (ref "R188")
      (value "10K")
      (footprint "0603 Resistors")
      (description "100mW 10kΩ 75V Thick Film Resistor ±1% ±100ppm/℃ 0603 Chip Resistor - Surface Mount RoHS")
      (fields
        (field (name "MANUFACTURER") "VISHAY")
        (field (name "MFR. PART #") "CRCW060310K0FKEA")
        (field (name "PACKAGE") "0603")
      )
      (libsource (lib "TG21_TX_Ma tran phimPrjPcb") (part "0603 10K"))
    )
    (comp (ref "R189")
      (value "10K")
      (footprint "0603 Resistors")
      (description "100mW 10kΩ 75V Thick Film Resistor ±1% ±100ppm/℃ 0603 Chip Resistor - Surface Mount RoHS")
      (fields
        (field (name "MANUFACTURER") "VISHAY")
        (field (name "MFR. PART #") "CRCW060310K0FKEA")
        (field (name "PACKAGE") "0603")
      )
      (libsource (lib "TG21_TX_Ma tran phimPrjPcb") (part "0603 10K"))
    )
    (comp (ref "R190")
      (value "10K")
      (footprint "0603 Resistors")
      (description "100mW 10kΩ 75V Thick Film Resistor ±1% ±100ppm/℃ 0603 Chip Resistor - Surface Mount RoHS")
      (fields
        (field (name "MANUFACTURER") "VISHAY")
        (field (name "MFR. PART #") "CRCW060310K0FKEA")
        (field (name "PACKAGE") "0603")
      )
      (libsource (lib "TG21_TX_Ma tran phimPrjPcb") (part "0603 10K"))
    )
    (comp (ref "R191")
      (value "10K")
      (footprint "0603 Resistors")
      (description "100mW 10kΩ 75V Thick Film Resistor ±1% ±100ppm/℃ 0603 Chip Resistor - Surface Mount RoHS")
      (fields
        (field (name "MANUFACTURER") "VISHAY")
        (field (name "MFR. PART #") "CRCW060310K0FKEA")
        (field (name "PACKAGE") "0603")
      )
      (libsource (lib "TG21_TX_Ma tran phimPrjPcb") (part "0603 10K"))
    )
    (comp (ref "R192")
      (value "10K")
      (footprint "0603 Resistors")
      (description "100mW 10kΩ 75V Thick Film Resistor ±1% ±100ppm/℃ 0603 Chip Resistor - Surface Mount RoHS")
      (fields
        (field (name "MANUFACTURER") "VISHAY")
        (field (name "MFR. PART #") "CRCW060310K0FKEA")
        (field (name "PACKAGE") "0603")
      )
      (libsource (lib "TG21_TX_Ma tran phimPrjPcb") (part "0603 10K"))
    )
    (comp (ref "R193")
      (value "10K")
      (footprint "0603 Resistors")
      (description "100mW 10kΩ 75V Thick Film Resistor ±1% ±100ppm/℃ 0603 Chip Resistor - Surface Mount RoHS")
      (fields
        (field (name "MANUFACTURER") "VISHAY")
        (field (name "MFR. PART #") "CRCW060310K0FKEA")
        (field (name "PACKAGE") "0603")
      )
      (libsource (lib "TG21_TX_Ma tran phimPrjPcb") (part "0603 10K"))
    )
    (comp (ref "R194")
      (value "10K")
      (footprint "0603 Resistors")
      (description "100mW 10kΩ 75V Thick Film Resistor ±1% ±100ppm/℃ 0603 Chip Resistor - Surface Mount RoHS")
      (fields
        (field (name "MANUFACTURER") "VISHAY")
        (field (name "MFR. PART #") "CRCW060310K0FKEA")
        (field (name "PACKAGE") "0603")
      )
      (libsource (lib "TG21_TX_Ma tran phimPrjPcb") (part "0603 10K"))
    )
    (comp (ref "R195")
      (value "10K")
      (footprint "0603 Resistors")
      (description "100mW 10kΩ 75V Thick Film Resistor ±1% ±100ppm/℃ 0603 Chip Resistor - Surface Mount RoHS")
      (fields
        (field (name "MANUFACTURER") "VISHAY")
        (field (name "MFR. PART #") "CRCW060310K0FKEA")
        (field (name "PACKAGE") "0603")
      )
      (libsource (lib "TG21_TX_Ma tran phimPrjPcb") (part "0603 10K"))
    )
    (comp (ref "R196")
      (value "10K")
      (footprint "0603 Resistors")
      (description "100mW 10kΩ 75V Thick Film Resistor ±1% ±100ppm/℃ 0603 Chip Resistor - Surface Mount RoHS")
      (fields
        (field (name "MANUFACTURER") "VISHAY")
        (field (name "MFR. PART #") "CRCW060310K0FKEA")
        (field (name "PACKAGE") "0603")
      )
      (libsource (lib "TG21_SCHLib") (part "0603 10K"))
    )
    (comp (ref "R197")
      (value "220R")
      (footprint "0603 Resistors")
      (description "100mW 220Ω 75V Thick Film Resistor ±1% ±100ppm/℃ 0603 Chip Resistor - Surface Mount RoHS")
      (fields
        (field (name "MFR. PART #") "CRCW0603220RFKEAHP")
        (field (name "LCSC PART #") "C313707")
        (field (name "PACKAGE") "0603")
      )
      (libsource (lib "TG21_SCHLib") (part "0603 220R"))
    )
    (comp (ref "R198")
      (value "10K")
      (footprint "0603 Resistors")
      (description "100mW 10kΩ 75V Thick Film Resistor ±1% ±100ppm/℃ 0603 Chip Resistor - Surface Mount RoHS")
      (fields
        (field (name "MANUFACTURER") "VISHAY")
        (field (name "MFR. PART #") "CRCW060310K0FKEA")
        (field (name "PACKAGE") "0603")
      )
      (libsource (lib "TG21_SCHLib") (part "0603 10K"))
    )
    (comp (ref "R199")
      (value "220R")
      (footprint "0603 Resistors")
      (description "100mW 220Ω 75V Thick Film Resistor ±1% ±100ppm/℃ 0603 Chip Resistor - Surface Mount RoHS")
      (fields
        (field (name "MFR. PART #") "CRCW0603220RFKEAHP")
        (field (name "LCSC PART #") "C313707")
        (field (name "PACKAGE") "0603")
      )
      (libsource (lib "TG21_SCHLib") (part "0603 220R"))
    )
    (comp (ref "R200")
      (value "220R")
      (footprint "0603 Resistors")
      (description "100mW 220Ω 75V Thick Film Resistor ±1% ±100ppm/℃ 0603 Chip Resistor - Surface Mount RoHS")
      (fields
        (field (name "MFR. PART #") "CRCW0603220RFKEAHP")
        (field (name "LCSC PART #") "C313707")
        (field (name "PACKAGE") "0603")
      )
      (libsource (lib "TG21_SCHLib") (part "0603 220R"))
    )
    (comp (ref "U1")
      (value "74HC595 SMD")
      (footprint "SOP 16")
      (description "2V~6V 1 100ns@5V,50pF Serial-to-Serial or Parallel SOP-16 Shift Registers RoHS")
      (fields (field (name "MANUFACTURER") "GR") (field (name "MFR. PART #") "74HC595"))
      (libsource (lib "TG21_TX_Ma tran phimPrjPcb") (part "74HC595 SMD"))
    )
    (comp (ref "U2")
      (value "74HC595 SMD")
      (footprint "SOP 16")
      (description "2V~6V 1 100ns@5V,50pF Serial-to-Serial or Parallel SOP-16 Shift Registers RoHS")
      (fields (field (name "MANUFACTURER") "GR") (field (name "MFR. PART #") "74HC595"))
      (libsource (lib "TG21_TX_Ma tran phimPrjPcb") (part "74HC595 SMD"))
    )
    (comp (ref "U3")
      (value "74HC595 SMD")
      (footprint "SOP 16")
      (description "2V~6V 1 100ns@5V,50pF Serial-to-Serial or Parallel SOP-16 Shift Registers RoHS")
      (fields (field (name "MANUFACTURER") "GR") (field (name "MFR. PART #") "74HC595"))
      (libsource (lib "TG21_TX_Ma tran phimPrjPcb") (part "74HC595 SMD"))
    )
    (comp (ref "U4")
      (value "74HC595 SMD")
      (footprint "SOP 16")
      (description "2V~6V 1 100ns@5V,50pF Serial-to-Serial or Parallel SOP-16 Shift Registers RoHS")
      (fields (field (name "MANUFACTURER") "GR") (field (name "MFR. PART #") "74HC595"))
      (libsource (lib "TG21_TX_Ma tran phimPrjPcb") (part "74HC595 SMD"))
    )
    (comp (ref "U5")
      (value "74HC595 SMD")
      (footprint "SOP 16")
      (description "2V~6V 1 100ns@5V,50pF Serial-to-Serial or Parallel SOP-16 Shift Registers RoHS")
      (fields (field (name "MANUFACTURER") "GR") (field (name "MFR. PART #") "74HC595"))
      (libsource (lib "TG21_TX_Ma tran phimPrjPcb") (part "74HC595 SMD"))
    )
    (comp (ref "U6")
      (value "74HC595 SMD")
      (footprint "SOP 16")
      (description "2V~6V 1 100ns@5V,50pF Serial-to-Serial or Parallel SOP-16 Shift Registers RoHS")
      (fields (field (name "MANUFACTURER") "GR") (field (name "MFR. PART #") "74HC595"))
      (libsource (lib "TG21_TX_Ma tran phimPrjPcb") (part "74HC595 SMD"))
    )
    (comp (ref "U7")
      (value "74HC595 SMD")
      (footprint "SOP 16")
      (description "2V~6V 1 100ns@5V,50pF Serial-to-Serial or Parallel SOP-16 Shift Registers RoHS")
      (fields (field (name "MANUFACTURER") "GR") (field (name "MFR. PART #") "74HC595"))
      (libsource (lib "TG21_TX_Ma tran phimPrjPcb") (part "74HC595 SMD"))
    )
    (comp (ref "U8")
      (value "74HC595 SMD")
      (footprint "SOP 16")
      (description "2V~6V 1 100ns@5V,50pF Serial-to-Serial or Parallel SOP-16 Shift Registers RoHS")
      (fields (field (name "MANUFACTURER") "GR") (field (name "MFR. PART #") "74HC595"))
      (libsource (lib "TG21_TX_Ma tran phimPrjPcb") (part "74HC595 SMD"))
    )
    (comp (ref "U9")
      (value "74HC595 SMD")
      (footprint "SOP 16")
      (description "2V~6V 1 100ns@5V,50pF Serial-to-Serial or Parallel SOP-16 Shift Registers RoHS")
      (fields (field (name "MANUFACTURER") "GR") (field (name "MFR. PART #") "74HC595"))
      (libsource (lib "TG21_TX_Ma tran phimPrjPcb") (part "74HC595 SMD"))
    )
    (comp (ref "U10")
      (value "74HC595 SMD")
      (footprint "SOP 16")
      (description "2V~6V 1 100ns@5V,50pF Serial-to-Serial or Parallel SOP-16 Shift Registers RoHS")
      (fields (field (name "MANUFACTURER") "GR") (field (name "MFR. PART #") "74HC595"))
      (libsource (lib "TG21_TX_Ma tran phimPrjPcb") (part "74HC595 SMD"))
    )
    (comp (ref "U11")
      (value "74HC595 SMD")
      (footprint "SOP 16")
      (description "2V~6V 1 100ns@5V,50pF Serial-to-Serial or Parallel SOP-16 Shift Registers RoHS")
      (fields (field (name "MANUFACTURER") "GR") (field (name "MFR. PART #") "74HC595"))
      (libsource (lib "TG21_TX_Ma tran phimPrjPcb") (part "74HC595 SMD"))
    )
    (comp (ref "U12")
      (value "74HC595 SMD")
      (footprint "SOP 16")
      (description "2V~6V 1 100ns@5V,50pF Serial-to-Serial or Parallel SOP-16 Shift Registers RoHS")
      (fields (field (name "MANUFACTURER") "GR") (field (name "MFR. PART #") "74HC595"))
      (libsource (lib "TG21_TX_Ma tran phimPrjPcb") (part "74HC595 SMD"))
    )
    (comp (ref "U13")
      (value "74HC595 SMD")
      (footprint "SOP 16")
      (description "2V~6V 1 100ns@5V,50pF Serial-to-Serial or Parallel SOP-16 Shift Registers RoHS")
      (fields (field (name "MANUFACTURER") "GR") (field (name "MFR. PART #") "74HC595"))
      (libsource (lib "TG21_TX_Ma tran phimPrjPcb") (part "74HC595 SMD"))
    )
  )
  (nets
    (net (code "1") (name "+24VDC") (class "Default")
      (node (ref "C27") (pin "2") (pinfunction "2_2") (pintype "passive"))
      (node (ref "C28") (pin "2") (pinfunction "2_2") (pintype "passive"))
      (node (ref "C29") (pin "2") (pinfunction "2_2") (pintype "passive"))
      (node (ref "C30") (pin "2") (pinfunction "2_2") (pintype "passive"))
      (node (ref "C31") (pin "2") (pinfunction "2_2") (pintype "passive"))
      (node (ref "C32") (pin "2") (pinfunction "2_2") (pintype "passive"))
      (node (ref "C33") (pin "2") (pinfunction "2_2") (pintype "passive"))
      (node (ref "C34") (pin "2") (pinfunction "2_2") (pintype "passive"))
      (node (ref "C35") (pin "2") (pinfunction "2_2") (pintype "passive"))
      (node (ref "C36") (pin "2") (pinfunction "2_2") (pintype "passive"))
      (node (ref "C37") (pin "2") (pinfunction "2_2") (pintype "passive"))
      (node (ref "C38") (pin "2") (pinfunction "2_2") (pintype "passive"))
      (node (ref "C39") (pin "2") (pinfunction "2_2") (pintype "passive"))
      (node (ref "C40") (pin "2") (pinfunction "2_2") (pintype "passive"))
      (node (ref "R1") (pin "1") (pinfunction "1_1") (pintype "passive"))
      (node (ref "R10") (pin "1") (pinfunction "1_1") (pintype "passive"))
      (node (ref "R105") (pin "1") (pinfunction "1_1") (pintype "passive"))
      (node (ref "R106") (pin "1") (pinfunction "1_1") (pintype "passive"))
      (node (ref "R107") (pin "1") (pinfunction "1_1") (pintype "passive"))
      (node (ref "R108") (pin "1") (pinfunction "1_1") (pintype "passive"))
      (node (ref "R109") (pin "1") (pinfunction "1_1") (pintype "passive"))
      (node (ref "R11") (pin "1") (pinfunction "1_1") (pintype "passive"))
      (node (ref "R110") (pin "1") (pinfunction "1_1") (pintype "passive"))
      (node (ref "R111") (pin "1") (pinfunction "1_1") (pintype "passive"))
      (node (ref "R112") (pin "1") (pinfunction "1_1") (pintype "passive"))
      (node (ref "R113") (pin "1") (pinfunction "1_1") (pintype "passive"))
      (node (ref "R114") (pin "1") (pinfunction "1_1") (pintype "passive"))
      (node (ref "R115") (pin "1") (pinfunction "1_1") (pintype "passive"))
      (node (ref "R116") (pin "1") (pinfunction "1_1") (pintype "passive"))
      (node (ref "R117") (pin "1") (pinfunction "1_1") (pintype "passive"))
      (node (ref "R12") (pin "1") (pinfunction "1_1") (pintype "passive"))
      (node (ref "R13") (pin "1") (pinfunction "1_1") (pintype "passive"))
      (node (ref "R131") (pin "1") (pinfunction "1_1") (pintype "passive"))
      (node (ref "R132") (pin "1") (pinfunction "1_1") (pintype "passive"))
      (node (ref "R133") (pin "1") (pinfunction "1_1") (pintype "passive"))
      (node (ref "R134") (pin "1") (pinfunction "1_1") (pintype "passive"))
      (node (ref "R135") (pin "1") (pinfunction "1_1") (pintype "passive"))
      (node (ref "R136") (pin "1") (pinfunction "1_1") (pintype "passive"))
      (node (ref "R137") (pin "1") (pinfunction "1_1") (pintype "passive"))
      (node (ref "R138") (pin "1") (pinfunction "1_1") (pintype "passive"))
      (node (ref "R139") (pin "1") (pinfunction "1_1") (pintype "passive"))
      (node (ref "R140") (pin "1") (pinfunction "1_1") (pintype "passive"))
      (node (ref "R141") (pin "1") (pinfunction "1_1") (pintype "passive"))
      (node (ref "R142") (pin "1") (pinfunction "1_1") (pintype "passive"))
      (node (ref "R143") (pin "1") (pinfunction "1_1") (pintype "passive"))
      (node (ref "R157") (pin "1") (pinfunction "1_1") (pintype "passive"))
      (node (ref "R158") (pin "1") (pinfunction "1_1") (pintype "passive"))
      (node (ref "R159") (pin "1") (pinfunction "1_1") (pintype "passive"))
      (node (ref "R160") (pin "1") (pinfunction "1_1") (pintype "passive"))
      (node (ref "R161") (pin "1") (pinfunction "1_1") (pintype "passive"))
      (node (ref "R162") (pin "1") (pinfunction "1_1") (pintype "passive"))
      (node (ref "R163") (pin "1") (pinfunction "1_1") (pintype "passive"))
      (node (ref "R164") (pin "1") (pinfunction "1_1") (pintype "passive"))
      (node (ref "R165") (pin "1") (pinfunction "1_1") (pintype "passive"))
      (node (ref "R166") (pin "1") (pinfunction "1_1") (pintype "passive"))
      (node (ref "R167") (pin "1") (pinfunction "1_1") (pintype "passive"))
      (node (ref "R168") (pin "1") (pinfunction "1_1") (pintype "passive"))
      (node (ref "R169") (pin "1") (pinfunction "1_1") (pintype "passive"))
      (node (ref "R2") (pin "1") (pinfunction "1_1") (pintype "passive"))
      (node (ref "R27") (pin "1") (pinfunction "1_1") (pintype "passive"))
      (node (ref "R28") (pin "1") (pinfunction "1_1") (pintype "passive"))
      (node (ref "R29") (pin "1") (pinfunction "1_1") (pintype "passive"))
      (node (ref "R3") (pin "1") (pinfunction "1_1") (pintype "passive"))
      (node (ref "R30") (pin "1") (pinfunction "1_1") (pintype "passive"))
      (node (ref "R31") (pin "1") (pinfunction "1_1") (pintype "passive"))
      (node (ref "R32") (pin "1") (pinfunction "1_1") (pintype "passive"))
      (node (ref "R33") (pin "1") (pinfunction "1_1") (pintype "passive"))
      (node (ref "R34") (pin "1") (pinfunction "1_1") (pintype "passive"))
      (node (ref "R35") (pin "1") (pinfunction "1_1") (pintype "passive"))
      (node (ref "R36") (pin "1") (pinfunction "1_1") (pintype "passive"))
      (node (ref "R37") (pin "1") (pinfunction "1_1") (pintype "passive"))
      (node (ref "R38") (pin "1") (pinfunction "1_1") (pintype "passive"))
      (node (ref "R39") (pin "1") (pinfunction "1_1") (pintype "passive"))
      (node (ref "R4") (pin "1") (pinfunction "1_1") (pintype "passive"))
      (node (ref "R5") (pin "1") (pinfunction "1_1") (pintype "passive"))
      (node (ref "R53") (pin "1") (pinfunction "1_1") (pintype "passive"))
      (node (ref "R54") (pin "1") (pinfunction "1_1") (pintype "passive"))
      (node (ref "R55") (pin "1") (pinfunction "1_1") (pintype "passive"))
      (node (ref "R56") (pin "1") (pinfunction "1_1") (pintype "passive"))
      (node (ref "R57") (pin "1") (pinfunction "1_1") (pintype "passive"))
      (node (ref "R58") (pin "1") (pinfunction "1_1") (pintype "passive"))
      (node (ref "R59") (pin "1") (pinfunction "1_1") (pintype "passive"))
      (node (ref "R6") (pin "1") (pinfunction "1_1") (pintype "passive"))
      (node (ref "R60") (pin "1") (pinfunction "1_1") (pintype "passive"))
      (node (ref "R61") (pin "1") (pinfunction "1_1") (pintype "passive"))
      (node (ref "R62") (pin "1") (pinfunction "1_1") (pintype "passive"))
      (node (ref "R63") (pin "1") (pinfunction "1_1") (pintype "passive"))
      (node (ref "R64") (pin "1") (pinfunction "1_1") (pintype "passive"))
      (node (ref "R65") (pin "1") (pinfunction "1_1") (pintype "passive"))
      (node (ref "R7") (pin "1") (pinfunction "1_1") (pintype "passive"))
      (node (ref "R79") (pin "1") (pinfunction "1_1") (pintype "passive"))
      (node (ref "R8") (pin "1") (pinfunction "1_1") (pintype "passive"))
      (node (ref "R80") (pin "1") (pinfunction "1_1") (pintype "passive"))
      (node (ref "R81") (pin "1") (pinfunction "1_1") (pintype "passive"))
      (node (ref "R82") (pin "1") (pinfunction "1_1") (pintype "passive"))
      (node (ref "R83") (pin "1") (pinfunction "1_1") (pintype "passive"))
      (node (ref "R84") (pin "1") (pinfunction "1_1") (pintype "passive"))
      (node (ref "R85") (pin "1") (pinfunction "1_1") (pintype "passive"))
      (node (ref "R86") (pin "1") (pinfunction "1_1") (pintype "passive"))
      (node (ref "R87") (pin "1") (pinfunction "1_1") (pintype "passive"))
      (node (ref "R88") (pin "1") (pinfunction "1_1") (pintype "passive"))
      (node (ref "R89") (pin "1") (pinfunction "1_1") (pintype "passive"))
      (node (ref "R9") (pin "1") (pinfunction "1_1") (pintype "passive"))
      (node (ref "R90") (pin "1") (pinfunction "1_1") (pintype "passive"))
      (node (ref "R91") (pin "1") (pinfunction "1_1") (pintype "passive"))
    )
    (net (code "2") (name "/BAT") (class "Default")
      (node (ref "H3") (pin "1") (pinfunction "1_1") (pintype "passive"))
    )
    (net (code "3") (name "/C1") (class "Default")
      (node (ref "BT1") (pin "1") (pinfunction "1_1") (pintype "passive"))
      (node (ref "BT14") (pin "1") (pinfunction "1_1") (pintype "passive"))
      (node (ref "BT27") (pin "1") (pinfunction "1_1") (pintype "passive"))
      (node (ref "BT40") (pin "1") (pinfunction "1_1") (pintype "passive"))
      (node (ref "BT53") (pin "1") (pinfunction "1_1") (pintype "passive"))
      (node (ref "BT66") (pin "1") (pinfunction "1_1") (pintype "passive"))
      (node (ref "BT79") (pin "1") (pinfunction "1_1") (pintype "passive"))
      (node (ref "C14") (pin "2") (pinfunction "2_2") (pintype "passive"))
      (node (ref "R183") (pin "1") (pinfunction "1_1") (pintype "passive"))
    )
    (net (code "4") (name "/C2") (class "Default")
      (node (ref "BT15") (pin "1") (pinfunction "1_1") (pintype "passive"))
      (node (ref "BT2") (pin "1") (pinfunction "1_1") (pintype "passive"))
      (node (ref "BT28") (pin "1") (pinfunction "1_1") (pintype "passive"))
      (node (ref "BT41") (pin "1") (pinfunction "1_1") (pintype "passive"))
      (node (ref "BT54") (pin "1") (pinfunction "1_1") (pintype "passive"))
      (node (ref "BT67") (pin "1") (pinfunction "1_1") (pintype "passive"))
      (node (ref "BT80") (pin "1") (pinfunction "1_1") (pintype "passive"))
      (node (ref "C15") (pin "2") (pinfunction "2_2") (pintype "passive"))
      (node (ref "R184") (pin "1") (pinfunction "1_1") (pintype "passive"))
    )
    (net (code "5") (name "/C3") (class "Default")
      (node (ref "BT16") (pin "1") (pinfunction "1_1") (pintype "passive"))
      (node (ref "BT29") (pin "1") (pinfunction "1_1") (pintype "passive"))
      (node (ref "BT3") (pin "1") (pinfunction "1_1") (pintype "passive"))
      (node (ref "BT42") (pin "1") (pinfunction "1_1") (pintype "passive"))
      (node (ref "BT55") (pin "1") (pinfunction "1_1") (pintype "passive"))
      (node (ref "BT68") (pin "1") (pinfunction "1_1") (pintype "passive"))
      (node (ref "BT81") (pin "1") (pinfunction "1_1") (pintype "passive"))
      (node (ref "C16") (pin "2") (pinfunction "2_2") (pintype "passive"))
      (node (ref "R185") (pin "1") (pinfunction "1_1") (pintype "passive"))
    )
    (net (code "6") (name "/C4") (class "Default")
      (node (ref "BT17") (pin "1") (pinfunction "1_1") (pintype "passive"))
      (node (ref "BT30") (pin "1") (pinfunction "1_1") (pintype "passive"))
      (node (ref "BT4") (pin "1") (pinfunction "1_1") (pintype "passive"))
      (node (ref "BT43") (pin "1") (pinfunction "1_1") (pintype "passive"))
      (node (ref "BT56") (pin "1") (pinfunction "1_1") (pintype "passive"))
      (node (ref "BT69") (pin "1") (pinfunction "1_1") (pintype "passive"))
      (node (ref "BT82") (pin "1") (pinfunction "1_1") (pintype "passive"))
      (node (ref "C17") (pin "2") (pinfunction "2_2") (pintype "passive"))
      (node (ref "R186") (pin "1") (pinfunction "1_1") (pintype "passive"))
    )
    (net (code "7") (name "/C5") (class "Default")
      (node (ref "BT18") (pin "1") (pinfunction "1_1") (pintype "passive"))
      (node (ref "BT31") (pin "1") (pinfunction "1_1") (pintype "passive"))
      (node (ref "BT44") (pin "1") (pinfunction "1_1") (pintype "passive"))
      (node (ref "BT5") (pin "1") (pinfunction "1_1") (pintype "passive"))
      (node (ref "BT57") (pin "1") (pinfunction "1_1") (pintype "passive"))
      (node (ref "BT70") (pin "1") (pinfunction "1_1") (pintype "passive"))
      (node (ref "BT83") (pin "1") (pinfunction "1_1") (pintype "passive"))
      (node (ref "C18") (pin "2") (pinfunction "2_2") (pintype "passive"))
      (node (ref "R187") (pin "1") (pinfunction "1_1") (pintype "passive"))
    )
    (net (code "8") (name "/C6") (class "Default")
      (node (ref "BT19") (pin "1") (pinfunction "1_1") (pintype "passive"))
      (node (ref "BT32") (pin "1") (pinfunction "1_1") (pintype "passive"))
      (node (ref "BT45") (pin "1") (pinfunction "1_1") (pintype "passive"))
      (node (ref "BT58") (pin "1") (pinfunction "1_1") (pintype "passive"))
      (node (ref "BT6") (pin "1") (pinfunction "1_1") (pintype "passive"))
      (node (ref "BT71") (pin "1") (pinfunction "1_1") (pintype "passive"))
      (node (ref "BT84") (pin "1") (pinfunction "1_1") (pintype "passive"))
      (node (ref "C19") (pin "2") (pinfunction "2_2") (pintype "passive"))
      (node (ref "R188") (pin "1") (pinfunction "1_1") (pintype "passive"))
    )
    (net (code "9") (name "/C7") (class "Default")
      (node (ref "BT20") (pin "1") (pinfunction "1_1") (pintype "passive"))
      (node (ref "BT33") (pin "1") (pinfunction "1_1") (pintype "passive"))
      (node (ref "BT46") (pin "1") (pinfunction "1_1") (pintype "passive"))
      (node (ref "BT59") (pin "1") (pinfunction "1_1") (pintype "passive"))
      (node (ref "BT7") (pin "1") (pinfunction "1_1") (pintype "passive"))
      (node (ref "BT72") (pin "1") (pinfunction "1_1") (pintype "passive"))
      (node (ref "BT85") (pin "1") (pinfunction "1_1") (pintype "passive"))
      (node (ref "C20") (pin "2") (pinfunction "2_2") (pintype "passive"))
      (node (ref "R189") (pin "1") (pinfunction "1_1") (pintype "passive"))
    )
    (net (code "10") (name "/C8") (class "Default")
      (node (ref "BT21") (pin "1") (pinfunction "1_1") (pintype "passive"))
      (node (ref "BT34") (pin "1") (pinfunction "1_1") (pintype "passive"))
      (node (ref "BT47") (pin "1") (pinfunction "1_1") (pintype "passive"))
      (node (ref "BT60") (pin "1") (pinfunction "1_1") (pintype "passive"))
      (node (ref "BT73") (pin "1") (pinfunction "1_1") (pintype "passive"))
      (node (ref "BT8") (pin "1") (pinfunction "1_1") (pintype "passive"))
      (node (ref "BT86") (pin "1") (pinfunction "1_1") (pintype "passive"))
      (node (ref "C21") (pin "2") (pinfunction "2_2") (pintype "passive"))
      (node (ref "R190") (pin "1") (pinfunction "1_1") (pintype "passive"))
    )
    (net (code "11") (name "/C9") (class "Default")
      (node (ref "BT22") (pin "1") (pinfunction "1_1") (pintype "passive"))
      (node (ref "BT35") (pin "1") (pinfunction "1_1") (pintype "passive"))
      (node (ref "BT48") (pin "1") (pinfunction "1_1") (pintype "passive"))
      (node (ref "BT61") (pin "1") (pinfunction "1_1") (pintype "passive"))
      (node (ref "BT74") (pin "1") (pinfunction "1_1") (pintype "passive"))
      (node (ref "BT87") (pin "1") (pinfunction "1_1") (pintype "passive"))
      (node (ref "BT9") (pin "1") (pinfunction "1_1") (pintype "passive"))
      (node (ref "C22") (pin "2") (pinfunction "2_2") (pintype "passive"))
      (node (ref "R191") (pin "1") (pinfunction "1_1") (pintype "passive"))
    )
    (net (code "12") (name "/C10") (class "Default")
      (node (ref "BT10") (pin "1") (pinfunction "1_1") (pintype "passive"))
      (node (ref "BT23") (pin "1") (pinfunction "1_1") (pintype "passive"))
      (node (ref "BT36") (pin "1") (pinfunction "1_1") (pintype "passive"))
      (node (ref "BT49") (pin "1") (pinfunction "1_1") (pintype "passive"))
      (node (ref "BT62") (pin "1") (pinfunction "1_1") (pintype "passive"))
      (node (ref "BT75") (pin "1") (pinfunction "1_1") (pintype "passive"))
      (node (ref "BT88") (pin "1") (pinfunction "1_1") (pintype "passive"))
      (node (ref "C23") (pin "2") (pinfunction "2_2") (pintype "passive"))
      (node (ref "R192") (pin "1") (pinfunction "1_1") (pintype "passive"))
    )
    (net (code "13") (name "/C11") (class "Default")
      (node (ref "BT11") (pin "1") (pinfunction "1_1") (pintype "passive"))
      (node (ref "BT24") (pin "1") (pinfunction "1_1") (pintype "passive"))
      (node (ref "BT37") (pin "1") (pinfunction "1_1") (pintype "passive"))
      (node (ref "BT50") (pin "1") (pinfunction "1_1") (pintype "passive"))
      (node (ref "BT63") (pin "1") (pinfunction "1_1") (pintype "passive"))
      (node (ref "BT76") (pin "1") (pinfunction "1_1") (pintype "passive"))
      (node (ref "BT89") (pin "1") (pinfunction "1_1") (pintype "passive"))
      (node (ref "C24") (pin "2") (pinfunction "2_2") (pintype "passive"))
      (node (ref "R193") (pin "1") (pinfunction "1_1") (pintype "passive"))
    )
    (net (code "14") (name "/C12") (class "Default")
      (node (ref "BT12") (pin "1") (pinfunction "1_1") (pintype "passive"))
      (node (ref "BT25") (pin "1") (pinfunction "1_1") (pintype "passive"))
      (node (ref "BT38") (pin "1") (pinfunction "1_1") (pintype "passive"))
      (node (ref "BT51") (pin "1") (pinfunction "1_1") (pintype "passive"))
      (node (ref "BT64") (pin "1") (pinfunction "1_1") (pintype "passive"))
      (node (ref "BT77") (pin "1") (pinfunction "1_1") (pintype "passive"))
      (node (ref "BT90") (pin "1") (pinfunction "1_1") (pintype "passive"))
      (node (ref "C25") (pin "2") (pinfunction "2_2") (pintype "passive"))
      (node (ref "R194") (pin "1") (pinfunction "1_1") (pintype "passive"))
    )
    (net (code "15") (name "/C13") (class "Default")
      (node (ref "BT13") (pin "1") (pinfunction "1_1") (pintype "passive"))
      (node (ref "BT26") (pin "1") (pinfunction "1_1") (pintype "passive"))
      (node (ref "BT39") (pin "1") (pinfunction "1_1") (pintype "passive"))
      (node (ref "BT52") (pin "1") (pinfunction "1_1") (pintype "passive"))
      (node (ref "BT65") (pin "1") (pinfunction "1_1") (pintype "passive"))
      (node (ref "BT78") (pin "1") (pinfunction "1_1") (pintype "passive"))
      (node (ref "BT91") (pin "1") (pinfunction "1_1") (pintype "passive"))
      (node (ref "C26") (pin "2") (pinfunction "2_2") (pintype "passive"))
      (node (ref "R195") (pin "1") (pinfunction "1_1") (pintype "passive"))
    )
    (net (code "16") (name "/DATA") (class "Default")
      (node (ref "U1") (pin "14") (pinfunction "DS_14") (pintype "passive"))
    )
    (net (code "17") (name "/H1") (class "Default")
      (node (ref "BT1") (pin "2") (pinfunction "2_2") (pintype "passive"))
      (node (ref "BT10") (pin "2") (pinfunction "2_2") (pintype "passive"))
      (node (ref "BT11") (pin "2") (pinfunction "2_2") (pintype "passive"))
      (node (ref "BT12") (pin "2") (pinfunction "2_2") (pintype "passive"))
      (node (ref "BT13") (pin "2") (pinfunction "2_2") (pintype "passive"))
      (node (ref "BT2") (pin "2") (pinfunction "2_2") (pintype "passive"))
      (node (ref "BT3") (pin "2") (pinfunction "2_2") (pintype "passive"))
      (node (ref "BT4") (pin "2") (pinfunction "2_2") (pintype "passive"))
      (node (ref "BT5") (pin "2") (pinfunction "2_2") (pintype "passive"))
      (node (ref "BT6") (pin "2") (pinfunction "2_2") (pintype "passive"))
      (node (ref "BT7") (pin "2") (pinfunction "2_2") (pintype "passive"))
      (node (ref "BT8") (pin "2") (pinfunction "2_2") (pintype "passive"))
      (node (ref "BT9") (pin "2") (pinfunction "2_2") (pintype "passive"))
    )
    (net (code "18") (name "/H2") (class "Default")
      (node (ref "BT14") (pin "2") (pinfunction "2_2") (pintype "passive"))
      (node (ref "BT15") (pin "2") (pinfunction "2_2") (pintype "passive"))
      (node (ref "BT16") (pin "2") (pinfunction "2_2") (pintype "passive"))
      (node (ref "BT17") (pin "2") (pinfunction "2_2") (pintype "passive"))
      (node (ref "BT18") (pin "2") (pinfunction "2_2") (pintype "passive"))
      (node (ref "BT19") (pin "2") (pinfunction "2_2") (pintype "passive"))
      (node (ref "BT20") (pin "2") (pinfunction "2_2") (pintype "passive"))
      (node (ref "BT21") (pin "2") (pinfunction "2_2") (pintype "passive"))
      (node (ref "BT22") (pin "2") (pinfunction "2_2") (pintype "passive"))
      (node (ref "BT23") (pin "2") (pinfunction "2_2") (pintype "passive"))
      (node (ref "BT24") (pin "2") (pinfunction "2_2") (pintype "passive"))
      (node (ref "BT25") (pin "2") (pinfunction "2_2") (pintype "passive"))
      (node (ref "BT26") (pin "2") (pinfunction "2_2") (pintype "passive"))
    )
    (net (code "19") (name "/H3") (class "Default")
      (node (ref "BT27") (pin "2") (pinfunction "2_2") (pintype "passive"))
      (node (ref "BT28") (pin "2") (pinfunction "2_2") (pintype "passive"))
      (node (ref "BT29") (pin "2") (pinfunction "2_2") (pintype "passive"))
      (node (ref "BT30") (pin "2") (pinfunction "2_2") (pintype "passive"))
      (node (ref "BT31") (pin "2") (pinfunction "2_2") (pintype "passive"))
      (node (ref "BT32") (pin "2") (pinfunction "2_2") (pintype "passive"))
      (node (ref "BT33") (pin "2") (pinfunction "2_2") (pintype "passive"))
      (node (ref "BT34") (pin "2") (pinfunction "2_2") (pintype "passive"))
      (node (ref "BT35") (pin "2") (pinfunction "2_2") (pintype "passive"))
      (node (ref "BT36") (pin "2") (pinfunction "2_2") (pintype "passive"))
      (node (ref "BT37") (pin "2") (pinfunction "2_2") (pintype "passive"))
      (node (ref "BT38") (pin "2") (pinfunction "2_2") (pintype "passive"))
      (node (ref "BT39") (pin "2") (pinfunction "2_2") (pintype "passive"))
    )
    (net (code "20") (name "/H4") (class "Default")
      (node (ref "BT40") (pin "2") (pinfunction "2_2") (pintype "passive"))
      (node (ref "BT41") (pin "2") (pinfunction "2_2") (pintype "passive"))
      (node (ref "BT42") (pin "2") (pinfunction "2_2") (pintype "passive"))
      (node (ref "BT43") (pin "2") (pinfunction "2_2") (pintype "passive"))
      (node (ref "BT44") (pin "2") (pinfunction "2_2") (pintype "passive"))
      (node (ref "BT45") (pin "2") (pinfunction "2_2") (pintype "passive"))
      (node (ref "BT46") (pin "2") (pinfunction "2_2") (pintype "passive"))
      (node (ref "BT47") (pin "2") (pinfunction "2_2") (pintype "passive"))
      (node (ref "BT48") (pin "2") (pinfunction "2_2") (pintype "passive"))
      (node (ref "BT49") (pin "2") (pinfunction "2_2") (pintype "passive"))
      (node (ref "BT50") (pin "2") (pinfunction "2_2") (pintype "passive"))
      (node (ref "BT51") (pin "2") (pinfunction "2_2") (pintype "passive"))
      (node (ref "BT52") (pin "2") (pinfunction "2_2") (pintype "passive"))
    )
    (net (code "21") (name "/H5") (class "Default")
      (node (ref "BT53") (pin "2") (pinfunction "2_2") (pintype "passive"))
      (node (ref "BT54") (pin "2") (pinfunction "2_2") (pintype "passive"))
      (node (ref "BT55") (pin "2") (pinfunction "2_2") (pintype "passive"))
      (node (ref "BT56") (pin "2") (pinfunction "2_2") (pintype "passive"))
      (node (ref "BT57") (pin "2") (pinfunction "2_2") (pintype "passive"))
      (node (ref "BT58") (pin "2") (pinfunction "2_2") (pintype "passive"))
      (node (ref "BT59") (pin "2") (pinfunction "2_2") (pintype "passive"))
      (node (ref "BT60") (pin "2") (pinfunction "2_2") (pintype "passive"))
      (node (ref "BT61") (pin "2") (pinfunction "2_2") (pintype "passive"))
      (node (ref "BT62") (pin "2") (pinfunction "2_2") (pintype "passive"))
      (node (ref "BT63") (pin "2") (pinfunction "2_2") (pintype "passive"))
      (node (ref "BT64") (pin "2") (pinfunction "2_2") (pintype "passive"))
      (node (ref "BT65") (pin "2") (pinfunction "2_2") (pintype "passive"))
    )
    (net (code "22") (name "/H6") (class "Default")
      (node (ref "BT66") (pin "2") (pinfunction "2_2") (pintype "passive"))
      (node (ref "BT67") (pin "2") (pinfunction "2_2") (pintype "passive"))
      (node (ref "BT68") (pin "2") (pinfunction "2_2") (pintype "passive"))
      (node (ref "BT69") (pin "2") (pinfunction "2_2") (pintype "passive"))
      (node (ref "BT70") (pin "2") (pinfunction "2_2") (pintype "passive"))
      (node (ref "BT71") (pin "2") (pinfunction "2_2") (pintype "passive"))
      (node (ref "BT72") (pin "2") (pinfunction "2_2") (pintype "passive"))
      (node (ref "BT73") (pin "2") (pinfunction "2_2") (pintype "passive"))
      (node (ref "BT74") (pin "2") (pinfunction "2_2") (pintype "passive"))
      (node (ref "BT75") (pin "2") (pinfunction "2_2") (pintype "passive"))
      (node (ref "BT76") (pin "2") (pinfunction "2_2") (pintype "passive"))
      (node (ref "BT77") (pin "2") (pinfunction "2_2") (pintype "passive"))
      (node (ref "BT78") (pin "2") (pinfunction "2_2") (pintype "passive"))
    )
    (net (code "23") (name "/H7") (class "Default")
      (node (ref "BT79") (pin "2") (pinfunction "2_2") (pintype "passive"))
      (node (ref "BT80") (pin "2") (pinfunction "2_2") (pintype "passive"))
      (node (ref "BT81") (pin "2") (pinfunction "2_2") (pintype "passive"))
      (node (ref "BT82") (pin "2") (pinfunction "2_2") (pintype "passive"))
      (node (ref "BT83") (pin "2") (pinfunction "2_2") (pintype "passive"))
      (node (ref "BT84") (pin "2") (pinfunction "2_2") (pintype "passive"))
      (node (ref "BT85") (pin "2") (pinfunction "2_2") (pintype "passive"))
      (node (ref "BT86") (pin "2") (pinfunction "2_2") (pintype "passive"))
      (node (ref "BT87") (pin "2") (pinfunction "2_2") (pintype "passive"))
      (node (ref "BT88") (pin "2") (pinfunction "2_2") (pintype "passive"))
      (node (ref "BT89") (pin "2") (pinfunction "2_2") (pintype "passive"))
      (node (ref "BT90") (pin "2") (pinfunction "2_2") (pintype "passive"))
      (node (ref "BT91") (pin "2") (pinfunction "2_2") (pintype "passive"))
    )
    (net (code "24") (name "/LED_PW") (class "Default")
      (node (ref "R200") (pin "1") (pinfunction "1_1") (pintype "passive"))
    )
    (net (code "25") (name "/LED_SET") (class "Default")
      (node (ref "R197") (pin "1") (pinfunction "1_1") (pintype "passive"))
    )
    (net (code "26") (name "/LED_STOP") (class "Default")
      (node (ref "R199") (pin "1") (pinfunction "1_1") (pintype "passive"))
    )
    (net (code "27") (name "/SET") (class "Default")
      (node (ref "C41") (pin "1") (pinfunction "1_1") (pintype "passive"))
      (node (ref "H1") (pin "4") (pinfunction "4_4") (pintype "passive"))
      (node (ref "R196") (pin "1") (pinfunction "1_1") (pintype "passive"))
    )
    (net (code "28") (name "/SLK") (class "Default")
      (node (ref "U1") (pin "11") (pinfunction "SHCP_11") (pintype "passive"))
      (node (ref "U10") (pin "11") (pinfunction "SHCP_11") (pintype "passive"))
      (node (ref "U11") (pin "11") (pinfunction "SHCP_11") (pintype "passive"))
      (node (ref "U12") (pin "11") (pinfunction "SHCP_11") (pintype "passive"))
      (node (ref "U13") (pin "11") (pinfunction "SHCP_11") (pintype "passive"))
      (node (ref "U2") (pin "11") (pinfunction "SHCP_11") (pintype "passive"))
      (node (ref "U3") (pin "11") (pinfunction "SHCP_11") (pintype "passive"))
      (node (ref "U4") (pin "11") (pinfunction "SHCP_11") (pintype "passive"))
      (node (ref "U5") (pin "11") (pinfunction "SHCP_11") (pintype "passive"))
      (node (ref "U6") (pin "11") (pinfunction "SHCP_11") (pintype "passive"))
      (node (ref "U7") (pin "11") (pinfunction "SHCP_11") (pintype "passive"))
      (node (ref "U8") (pin "11") (pinfunction "SHCP_11") (pintype "passive"))
      (node (ref "U9") (pin "11") (pinfunction "SHCP_11") (pintype "passive"))
    )
    (net (code "29") (name "/STOP") (class "Default")
      (node (ref "C42") (pin "1") (pinfunction "1_1") (pintype "passive"))
      (node (ref "H2") (pin "4") (pinfunction "4_4") (pintype "passive"))
      (node (ref "R198") (pin "1") (pinfunction "1_1") (pintype "passive"))
    )
    (net (code "30") (name "/STR") (class "Default")
      (node (ref "U1") (pin "12") (pinfunction "STCP_12") (pintype "passive"))
      (node (ref "U10") (pin "12") (pinfunction "STCP_12") (pintype "passive"))
      (node (ref "U11") (pin "12") (pinfunction "STCP_12") (pintype "passive"))
      (node (ref "U12") (pin "12") (pinfunction "STCP_12") (pintype "passive"))
      (node (ref "U13") (pin "12") (pinfunction "STCP_12") (pintype "passive"))
      (node (ref "U2") (pin "12") (pinfunction "STCP_12") (pintype "passive"))
      (node (ref "U3") (pin "12") (pinfunction "STCP_12") (pintype "passive"))
      (node (ref "U4") (pin "12") (pinfunction "STCP_12") (pintype "passive"))
      (node (ref "U5") (pin "12") (pinfunction "STCP_12") (pintype "passive"))
      (node (ref "U6") (pin "12") (pinfunction "STCP_12") (pintype "passive"))
      (node (ref "U7") (pin "12") (pinfunction "STCP_12") (pintype "passive"))
      (node (ref "U8") (pin "12") (pinfunction "STCP_12") (pintype "passive"))
      (node (ref "U9") (pin "12") (pinfunction "STCP_12") (pintype "passive"))
    )
    (net (code "31") (name "BAT+") (class "Default")
      (node (ref "H3") (pin "4") (pinfunction "4_4") (pintype "passive"))
    )
    (net (code "32") (name "CP1") (class "Default")
      (node (ref "U1") (pin "9") (pinfunction "DATAO_9") (pintype "passive"))
      (node (ref "U2") (pin "14") (pinfunction "DS_14") (pintype "passive"))
    )
    (net (code "33") (name "CP2") (class "Default")
      (node (ref "U2") (pin "9") (pinfunction "DATAO_9") (pintype "passive"))
      (node (ref "U3") (pin "14") (pinfunction "DS_14") (pintype "passive"))
    )
    (net (code "34") (name "CP3") (class "Default")
      (node (ref "U3") (pin "9") (pinfunction "DATAO_9") (pintype "passive"))
      (node (ref "U4") (pin "14") (pinfunction "DS_14") (pintype "passive"))
    )
    (net (code "35") (name "CP4") (class "Default")
      (node (ref "U4") (pin "9") (pinfunction "DATAO_9") (pintype "passive"))
      (node (ref "U5") (pin "14") (pinfunction "DS_14") (pintype "passive"))
    )
    (net (code "36") (name "CP5") (class "Default")
      (node (ref "U5") (pin "9") (pinfunction "DATAO_9") (pintype "passive"))
      (node (ref "U6") (pin "14") (pinfunction "DS_14") (pintype "passive"))
    )
    (net (code "37") (name "CP6") (class "Default")
      (node (ref "U6") (pin "9") (pinfunction "DATAO_9") (pintype "passive"))
      (node (ref "U7") (pin "14") (pinfunction "DS_14") (pintype "passive"))
    )
    (net (code "38") (name "CP7") (class "Default")
      (node (ref "U7") (pin "9") (pinfunction "DATAO_9") (pintype "passive"))
      (node (ref "U8") (pin "14") (pinfunction "DS_14") (pintype "passive"))
    )
    (net (code "39") (name "CP8") (class "Default")
      (node (ref "U8") (pin "9") (pinfunction "DATAO_9") (pintype "passive"))
      (node (ref "U9") (pin "14") (pinfunction "DS_14") (pintype "passive"))
    )
    (net (code "40") (name "CP9") (class "Default")
      (node (ref "U10") (pin "14") (pinfunction "DS_14") (pintype "passive"))
      (node (ref "U9") (pin "9") (pinfunction "DATAO_9") (pintype "passive"))
    )
    (net (code "41") (name "CP10") (class "Default")
      (node (ref "U10") (pin "9") (pinfunction "DATAO_9") (pintype "passive"))
      (node (ref "U11") (pin "14") (pinfunction "DS_14") (pintype "passive"))
    )
    (net (code "42") (name "CP11") (class "Default")
      (node (ref "U11") (pin "9") (pinfunction "DATAO_9") (pintype "passive"))
      (node (ref "U13") (pin "14") (pinfunction "DS_14") (pintype "passive"))
    )
    (net (code "43") (name "CP12") (class "Default")
      (node (ref "U12") (pin "14") (pinfunction "DS_14") (pintype "passive"))
      (node (ref "U13") (pin "9") (pinfunction "DATAO_9") (pintype "passive"))
    )
    (net (code "44") (name "GND") (class "Default")
      (node (ref "C1") (pin "1") (pinfunction "1_1") (pintype "passive"))
      (node (ref "C10") (pin "1") (pinfunction "1_1") (pintype "passive"))
      (node (ref "C11") (pin "1") (pinfunction "1_1") (pintype "passive"))
      (node (ref "C12") (pin "1") (pinfunction "1_1") (pintype "passive"))
      (node (ref "C13") (pin "1") (pinfunction "1_1") (pintype "passive"))
      (node (ref "C2") (pin "1") (pinfunction "1_1") (pintype "passive"))
      (node (ref "C27") (pin "1") (pinfunction "1_1") (pintype "passive"))
      (node (ref "C28") (pin "1") (pinfunction "1_1") (pintype "passive"))
      (node (ref "C29") (pin "1") (pinfunction "1_1") (pintype "passive"))
      (node (ref "C3") (pin "1") (pinfunction "1_1") (pintype "passive"))
      (node (ref "C30") (pin "1") (pinfunction "1_1") (pintype "passive"))
      (node (ref "C31") (pin "1") (pinfunction "1_1") (pintype "passive"))
      (node (ref "C32") (pin "1") (pinfunction "1_1") (pintype "passive"))
      (node (ref "C33") (pin "1") (pinfunction "1_1") (pintype "passive"))
      (node (ref "C34") (pin "1") (pinfunction "1_1") (pintype "passive"))
      (node (ref "C35") (pin "1") (pinfunction "1_1") (pintype "passive"))
      (node (ref "C36") (pin "1") (pinfunction "1_1") (pintype "passive"))
      (node (ref "C37") (pin "1") (pinfunction "1_1") (pintype "passive"))
      (node (ref "C38") (pin "1") (pinfunction "1_1") (pintype "passive"))
      (node (ref "C39") (pin "1") (pinfunction "1_1") (pintype "passive"))
      (node (ref "C4") (pin "1") (pinfunction "1_1") (pintype "passive"))
      (node (ref "C40") (pin "1") (pinfunction "1_1") (pintype "passive"))
      (node (ref "C41") (pin "2") (pinfunction "2_2") (pintype "passive"))
      (node (ref "C42") (pin "2") (pinfunction "2_2") (pintype "passive"))
      (node (ref "C5") (pin "1") (pinfunction "1_1") (pintype "passive"))
      (node (ref "C6") (pin "1") (pinfunction "1_1") (pintype "passive"))
      (node (ref "C7") (pin "1") (pinfunction "1_1") (pintype "passive"))
      (node (ref "C8") (pin "1") (pinfunction "1_1") (pintype "passive"))
      (node (ref "C9") (pin "1") (pinfunction "1_1") (pintype "passive"))
      (node (ref "H1") (pin "1") (pinfunction "1_1") (pintype "passive"))
      (node (ref "H1") (pin "2") (pinfunction "2_2") (pintype "passive"))
      (node (ref "H2") (pin "1") (pinfunction "1_1") (pintype "passive"))
      (node (ref "H2") (pin "2") (pinfunction "2_2") (pintype "passive"))
      (node (ref "H3") (pin "2") (pinfunction "2_2") (pintype "passive"))
      (node (ref "Q1") (pin "2") (pinfunction "S_2") (pintype "passive"))
      (node (ref "Q10") (pin "2") (pinfunction "S_2") (pintype "passive"))
      (node (ref "Q11") (pin "2") (pinfunction "S_2") (pintype "passive"))
      (node (ref "Q12") (pin "2") (pinfunction "S_2") (pintype "passive"))
      (node (ref "Q13") (pin "2") (pinfunction "S_2") (pintype "passive"))
      (node (ref "Q14") (pin "2") (pinfunction "S_2") (pintype "passive"))
      (node (ref "Q15") (pin "2") (pinfunction "S_2") (pintype "passive"))
      (node (ref "Q16") (pin "2") (pinfunction "S_2") (pintype "passive"))
      (node (ref "Q17") (pin "2") (pinfunction "S_2") (pintype "passive"))
      (node (ref "Q18") (pin "2") (pinfunction "S_2") (pintype "passive"))
      (node (ref "Q19") (pin "2") (pinfunction "S_2") (pintype "passive"))
      (node (ref "Q2") (pin "2") (pinfunction "S_2") (pintype "passive"))
      (node (ref "Q20") (pin "2") (pinfunction "S_2") (pintype "passive"))
      (node (ref "Q21") (pin "2") (pinfunction "S_2") (pintype "passive"))
      (node (ref "Q22") (pin "2") (pinfunction "S_2") (pintype "passive"))
      (node (ref "Q23") (pin "2") (pinfunction "S_2") (pintype "passive"))
      (node (ref "Q24") (pin "2") (pinfunction "S_2") (pintype "passive"))
      (node (ref "Q25") (pin "2") (pinfunction "S_2") (pintype "passive"))
      (node (ref "Q26") (pin "2") (pinfunction "S_2") (pintype "passive"))
      (node (ref "Q27") (pin "2") (pinfunction "S_2") (pintype "passive"))
      (node (ref "Q28") (pin "2") (pinfunction "S_2") (pintype "passive"))
      (node (ref "Q29") (pin "2") (pinfunction "S_2") (pintype "passive"))
      (node (ref "Q3") (pin "2") (pinfunction "S_2") (pintype "passive"))
      (node (ref "Q30") (pin "2") (pinfunction "S_2") (pintype "passive"))
      (node (ref "Q31") (pin "2") (pinfunction "S_2") (pintype "passive"))
      (node (ref "Q32") (pin "2") (pinfunction "S_2") (pintype "passive"))
      (node (ref "Q33") (pin "2") (pinfunction "S_2") (pintype "passive"))
      (node (ref "Q34") (pin "2") (pinfunction "S_2") (pintype "passive"))
      (node (ref "Q35") (pin "2") (pinfunction "S_2") (pintype "passive"))
      (node (ref "Q36") (pin "2") (pinfunction "S_2") (pintype "passive"))
      (node (ref "Q37") (pin "2") (pinfunction "S_2") (pintype "passive"))
      (node (ref "Q38") (pin "2") (pinfunction "S_2") (pintype "passive"))
      (node (ref "Q39") (pin "2") (pinfunction "S_2") (pintype "passive"))
      (node (ref "Q4") (pin "2") (pinfunction "S_2") (pintype "passive"))
      (node (ref "Q40") (pin "2") (pinfunction "S_2") (pintype "passive"))
      (node (ref "Q41") (pin "2") (pinfunction "S_2") (pintype "passive"))
      (node (ref "Q42") (pin "2") (pinfunction "S_2") (pintype "passive"))
      (node (ref "Q43") (pin "2") (pinfunction "S_2") (pintype "passive"))
      (node (ref "Q44") (pin "2") (pinfunction "S_2") (pintype "passive"))
      (node (ref "Q45") (pin "2") (pinfunction "S_2") (pintype "passive"))
      (node (ref "Q46") (pin "2") (pinfunction "S_2") (pintype "passive"))
      (node (ref "Q47") (pin "2") (pinfunction "S_2") (pintype "passive"))
      (node (ref "Q48") (pin "2") (pinfunction "S_2") (pintype "passive"))
      (node (ref "Q49") (pin "2") (pinfunction "S_2") (pintype "passive"))
      (node (ref "Q5") (pin "2") (pinfunction "S_2") (pintype "passive"))
      (node (ref "Q50") (pin "2") (pinfunction "S_2") (pintype "passive"))
      (node (ref "Q51") (pin "2") (pinfunction "S_2") (pintype "passive"))
      (node (ref "Q52") (pin "2") (pinfunction "S_2") (pintype "passive"))
      (node (ref "Q53") (pin "2") (pinfunction "S_2") (pintype "passive"))
      (node (ref "Q54") (pin "2") (pinfunction "S_2") (pintype "passive"))
      (node (ref "Q55") (pin "2") (pinfunction "S_2") (pintype "passive"))
      (node (ref "Q56") (pin "2") (pinfunction "S_2") (pintype "passive"))
      (node (ref "Q57") (pin "2") (pinfunction "S_2") (pintype "passive"))
      (node (ref "Q58") (pin "2") (pinfunction "S_2") (pintype "passive"))
      (node (ref "Q59") (pin "2") (pinfunction "S_2") (pintype "passive"))
      (node (ref "Q6") (pin "2") (pinfunction "S_2") (pintype "passive"))
      (node (ref "Q60") (pin "2") (pinfunction "S_2") (pintype "passive"))
      (node (ref "Q61") (pin "2") (pinfunction "S_2") (pintype "passive"))
      (node (ref "Q62") (pin "2") (pinfunction "S_2") (pintype "passive"))
      (node (ref "Q63") (pin "2") (pinfunction "S_2") (pintype "passive"))
      (node (ref "Q64") (pin "2") (pinfunction "S_2") (pintype "passive"))
      (node (ref "Q65") (pin "2") (pinfunction "S_2") (pintype "passive"))
      (node (ref "Q66") (pin "2") (pinfunction "S_2") (pintype "passive"))
      (node (ref "Q67") (pin "2") (pinfunction "S_2") (pintype "passive"))
      (node (ref "Q68") (pin "2") (pinfunction "S_2") (pintype "passive"))
      (node (ref "Q69") (pin "2") (pinfunction "S_2") (pintype "passive"))
      (node (ref "Q7") (pin "2") (pinfunction "S_2") (pintype "passive"))
      (node (ref "Q70") (pin "2") (pinfunction "S_2") (pintype "passive"))
      (node (ref "Q71") (pin "2") (pinfunction "S_2") (pintype "passive"))
      (node (ref "Q72") (pin "2") (pinfunction "S_2") (pintype "passive"))
      (node (ref "Q73") (pin "2") (pinfunction "S_2") (pintype "passive"))
      (node (ref "Q74") (pin "2") (pinfunction "S_2") (pintype "passive"))
      (node (ref "Q75") (pin "2") (pinfunction "S_2") (pintype "passive"))
      (node (ref "Q76") (pin "2") (pinfunction "S_2") (pintype "passive"))
      (node (ref "Q77") (pin "2") (pinfunction "S_2") (pintype "passive"))
      (node (ref "Q78") (pin "2") (pinfunction "S_2") (pintype "passive"))
      (node (ref "Q79") (pin "2") (pinfunction "S_2") (pintype "passive"))
      (node (ref "Q8") (pin "2") (pinfunction "S_2") (pintype "passive"))
      (node (ref "Q80") (pin "2") (pinfunction "S_2") (pintype "passive"))
      (node (ref "Q81") (pin "2") (pinfunction "S_2") (pintype "passive"))
      (node (ref "Q82") (pin "2") (pinfunction "S_2") (pintype "passive"))
      (node (ref "Q83") (pin "2") (pinfunction "S_2") (pintype "passive"))
      (node (ref "Q84") (pin "2") (pinfunction "S_2") (pintype "passive"))
      (node (ref "Q85") (pin "2") (pinfunction "S_2") (pintype "passive"))
      (node (ref "Q86") (pin "2") (pinfunction "S_2") (pintype "passive"))
      (node (ref "Q87") (pin "2") (pinfunction "S_2") (pintype "passive"))
      (node (ref "Q88") (pin "2") (pinfunction "S_2") (pintype "passive"))
      (node (ref "Q89") (pin "2") (pinfunction "S_2") (pintype "passive"))
      (node (ref "Q9") (pin "2") (pinfunction "S_2") (pintype "passive"))
      (node (ref "Q90") (pin "2") (pinfunction "S_2") (pintype "passive"))
      (node (ref "Q91") (pin "2") (pinfunction "S_2") (pintype "passive"))
      (node (ref "R100") (pin "1") (pinfunction "1_1") (pintype "passive"))
      (node (ref "R101") (pin "1") (pinfunction "1_1") (pintype "passive"))
      (node (ref "R102") (pin "1") (pinfunction "1_1") (pintype "passive"))
      (node (ref "R103") (pin "1") (pinfunction "1_1") (pintype "passive"))
      (node (ref "R104") (pin "1") (pinfunction "1_1") (pintype "passive"))
      (node (ref "R118") (pin "1") (pinfunction "1_1") (pintype "passive"))
      (node (ref "R119") (pin "1") (pinfunction "1_1") (pintype "passive"))
      (node (ref "R120") (pin "1") (pinfunction "1_1") (pintype "passive"))
      (node (ref "R121") (pin "1") (pinfunction "1_1") (pintype "passive"))
      (node (ref "R122") (pin "1") (pinfunction "1_1") (pintype "passive"))
      (node (ref "R123") (pin "1") (pinfunction "1_1") (pintype "passive"))
      (node (ref "R124") (pin "1") (pinfunction "1_1") (pintype "passive"))
      (node (ref "R125") (pin "1") (pinfunction "1_1") (pintype "passive"))
      (node (ref "R126") (pin "1") (pinfunction "1_1") (pintype "passive"))
      (node (ref "R127") (pin "1") (pinfunction "1_1") (pintype "passive"))
      (node (ref "R128") (pin "1") (pinfunction "1_1") (pintype "passive"))
      (node (ref "R129") (pin "1") (pinfunction "1_1") (pintype "passive"))
      (node (ref "R130") (pin "1") (pinfunction "1_1") (pintype "passive"))
      (node (ref "R14") (pin "1") (pinfunction "1_1") (pintype "passive"))
      (node (ref "R144") (pin "1") (pinfunction "1_1") (pintype "passive"))
      (node (ref "R145") (pin "1") (pinfunction "1_1") (pintype "passive"))
      (node (ref "R146") (pin "1") (pinfunction "1_1") (pintype "passive"))
      (node (ref "R147") (pin "1") (pinfunction "1_1") (pintype "passive"))
      (node (ref "R148") (pin "1") (pinfunction "1_1") (pintype "passive"))
      (node (ref "R149") (pin "1") (pinfunction "1_1") (pintype "passive"))
      (node (ref "R15") (pin "1") (pinfunction "1_1") (pintype "passive"))
      (node (ref "R150") (pin "1") (pinfunction "1_1") (pintype "passive"))
      (node (ref "R151") (pin "1") (pinfunction "1_1") (pintype "passive"))
      (node (ref "R152") (pin "1") (pinfunction "1_1") (pintype "passive"))
      (node (ref "R153") (pin "1") (pinfunction "1_1") (pintype "passive"))
      (node (ref "R154") (pin "1") (pinfunction "1_1") (pintype "passive"))
      (node (ref "R155") (pin "1") (pinfunction "1_1") (pintype "passive"))
      (node (ref "R156") (pin "1") (pinfunction "1_1") (pintype "passive"))
      (node (ref "R16") (pin "1") (pinfunction "1_1") (pintype "passive"))
      (node (ref "R17") (pin "1") (pinfunction "1_1") (pintype "passive"))
      (node (ref "R170") (pin "1") (pinfunction "1_1") (pintype "passive"))
      (node (ref "R171") (pin "1") (pinfunction "1_1") (pintype "passive"))
      (node (ref "R172") (pin "1") (pinfunction "1_1") (pintype "passive"))
      (node (ref "R173") (pin "1") (pinfunction "1_1") (pintype "passive"))
      (node (ref "R174") (pin "1") (pinfunction "1_1") (pintype "passive"))
      (node (ref "R175") (pin "1") (pinfunction "1_1") (pintype "passive"))
      (node (ref "R176") (pin "1") (pinfunction "1_1") (pintype "passive"))
      (node (ref "R177") (pin "1") (pinfunction "1_1") (pintype "passive"))
      (node (ref "R178") (pin "1") (pinfunction "1_1") (pintype "passive"))
      (node (ref "R179") (pin "1") (pinfunction "1_1") (pintype "passive"))
      (node (ref "R18") (pin "1") (pinfunction "1_1") (pintype "passive"))
      (node (ref "R180") (pin "1") (pinfunction "1_1") (pintype "passive"))
      (node (ref "R181") (pin "1") (pinfunction "1_1") (pintype "passive"))
      (node (ref "R182") (pin "1") (pinfunction "1_1") (pintype "passive"))
      (node (ref "R19") (pin "1") (pinfunction "1_1") (pintype "passive"))
      (node (ref "R20") (pin "1") (pinfunction "1_1") (pintype "passive"))
      (node (ref "R21") (pin "1") (pinfunction "1_1") (pintype "passive"))
      (node (ref "R22") (pin "1") (pinfunction "1_1") (pintype "passive"))
      (node (ref "R23") (pin "1") (pinfunction "1_1") (pintype "passive"))
      (node (ref "R24") (pin "1") (pinfunction "1_1") (pintype "passive"))
      (node (ref "R25") (pin "1") (pinfunction "1_1") (pintype "passive"))
      (node (ref "R26") (pin "1") (pinfunction "1_1") (pintype "passive"))
      (node (ref "R40") (pin "1") (pinfunction "1_1") (pintype "passive"))
      (node (ref "R41") (pin "1") (pinfunction "1_1") (pintype "passive"))
      (node (ref "R42") (pin "1") (pinfunction "1_1") (pintype "passive"))
      (node (ref "R43") (pin "1") (pinfunction "1_1") (pintype "passive"))
      (node (ref "R44") (pin "1") (pinfunction "1_1") (pintype "passive"))
      (node (ref "R45") (pin "1") (pinfunction "1_1") (pintype "passive"))
      (node (ref "R46") (pin "1") (pinfunction "1_1") (pintype "passive"))
      (node (ref "R47") (pin "1") (pinfunction "1_1") (pintype "passive"))
      (node (ref "R48") (pin "1") (pinfunction "1_1") (pintype "passive"))
      (node (ref "R49") (pin "1") (pinfunction "1_1") (pintype "passive"))
      (node (ref "R50") (pin "1") (pinfunction "1_1") (pintype "passive"))
      (node (ref "R51") (pin "1") (pinfunction "1_1") (pintype "passive"))
      (node (ref "R52") (pin "1") (pinfunction "1_1") (pintype "passive"))
      (node (ref "R66") (pin "1") (pinfunction "1_1") (pintype "passive"))
      (node (ref "R67") (pin "1") (pinfunction "1_1") (pintype "passive"))
      (node (ref "R68") (pin "1") (pinfunction "1_1") (pintype "passive"))
      (node (ref "R69") (pin "1") (pinfunction "1_1") (pintype "passive"))
      (node (ref "R70") (pin "1") (pinfunction "1_1") (pintype "passive"))
      (node (ref "R71") (pin "1") (pinfunction "1_1") (pintype "passive"))
      (node (ref "R72") (pin "1") (pinfunction "1_1") (pintype "passive"))
      (node (ref "R73") (pin "1") (pinfunction "1_1") (pintype "passive"))
      (node (ref "R74") (pin "1") (pinfunction "1_1") (pintype "passive"))
      (node (ref "R75") (pin "1") (pinfunction "1_1") (pintype "passive"))
      (node (ref "R76") (pin "1") (pinfunction "1_1") (pintype "passive"))
      (node (ref "R77") (pin "1") (pinfunction "1_1") (pintype "passive"))
      (node (ref "R78") (pin "1") (pinfunction "1_1") (pintype "passive"))
      (node (ref "R92") (pin "1") (pinfunction "1_1") (pintype "passive"))
      (node (ref "R93") (pin "1") (pinfunction "1_1") (pintype "passive"))
      (node (ref "R94") (pin "1") (pinfunction "1_1") (pintype "passive"))
      (node (ref "R95") (pin "1") (pinfunction "1_1") (pintype "passive"))
      (node (ref "R96") (pin "1") (pinfunction "1_1") (pintype "passive"))
      (node (ref "R97") (pin "1") (pinfunction "1_1") (pintype "passive"))
      (node (ref "R98") (pin "1") (pinfunction "1_1") (pintype "passive"))
      (node (ref "R99") (pin "1") (pinfunction "1_1") (pintype "passive"))
      (node (ref "U1") (pin "13") (pinfunction "~{OE}_13") (pintype "passive"))
      (node (ref "U1") (pin "8") (pinfunction "GND_8") (pintype "passive"))
      (node (ref "U10") (pin "13") (pinfunction "~{OE}_13") (pintype "passive"))
      (node (ref "U10") (pin "8") (pinfunction "GND_8") (pintype "passive"))
      (node (ref "U11") (pin "13") (pinfunction "~{OE}_13") (pintype "passive"))
      (node (ref "U11") (pin "8") (pinfunction "GND_8") (pintype "passive"))
      (node (ref "U12") (pin "13") (pinfunction "~{OE}_13") (pintype "passive"))
      (node (ref "U12") (pin "8") (pinfunction "GND_8") (pintype "passive"))
      (node (ref "U13") (pin "13") (pinfunction "~{OE}_13") (pintype "passive"))
      (node (ref "U13") (pin "8") (pinfunction "GND_8") (pintype "passive"))
      (node (ref "U2") (pin "13") (pinfunction "~{OE}_13") (pintype "passive"))
      (node (ref "U2") (pin "8") (pinfunction "GND_8") (pintype "passive"))
      (node (ref "U3") (pin "13") (pinfunction "~{OE}_13") (pintype "passive"))
      (node (ref "U3") (pin "8") (pinfunction "GND_8") (pintype "passive"))
      (node (ref "U4") (pin "13") (pinfunction "~{OE}_13") (pintype "passive"))
      (node (ref "U4") (pin "8") (pinfunction "GND_8") (pintype "passive"))
      (node (ref "U5") (pin "13") (pinfunction "~{OE}_13") (pintype "passive"))
      (node (ref "U5") (pin "8") (pinfunction "GND_8") (pintype "passive"))
      (node (ref "U6") (pin "13") (pinfunction "~{OE}_13") (pintype "passive"))
      (node (ref "U6") (pin "8") (pinfunction "GND_8") (pintype "passive"))
      (node (ref "U7") (pin "13") (pinfunction "~{OE}_13") (pintype "passive"))
      (node (ref "U7") (pin "8") (pinfunction "GND_8") (pintype "passive"))
      (node (ref "U8") (pin "13") (pinfunction "~{OE}_13") (pintype "passive"))
      (node (ref "U8") (pin "8") (pinfunction "GND_8") (pintype "passive"))
      (node (ref "U9") (pin "13") (pinfunction "~{OE}_13") (pintype "passive"))
      (node (ref "U9") (pin "8") (pinfunction "GND_8") (pintype "passive"))
    )
    (net (code "45") (name "L1") (class "Default")
      (node (ref "Q1") (pin "1") (pinfunction "G_1") (pintype "passive"))
      (node (ref "R14") (pin "2") (pinfunction "2_2") (pintype "passive"))
      (node (ref "U1") (pin "15") (pinfunction "QA_15") (pintype "passive"))
    )
    (net (code "46") (name "L2") (class "Default")
      (node (ref "Q14") (pin "1") (pinfunction "G_1") (pintype "passive"))
      (node (ref "R40") (pin "2") (pinfunction "2_2") (pintype "passive"))
      (node (ref "U1") (pin "1") (pinfunction "QB_1") (pintype "passive"))
    )
    (net (code "47") (name "L3") (class "Default")
      (node (ref "Q27") (pin "1") (pinfunction "G_1") (pintype "passive"))
      (node (ref "R66") (pin "2") (pinfunction "2_2") (pintype "passive"))
      (node (ref "U1") (pin "2") (pinfunction "QC_2") (pintype "passive"))
    )
    (net (code "48") (name "L4") (class "Default")
      (node (ref "Q40") (pin "1") (pinfunction "G_1") (pintype "passive"))
      (node (ref "R92") (pin "2") (pinfunction "2_2") (pintype "passive"))
      (node (ref "U1") (pin "3") (pinfunction "QD_3") (pintype "passive"))
    )
    (net (code "49") (name "L5") (class "Default")
      (node (ref "Q53") (pin "1") (pinfunction "G_1") (pintype "passive"))
      (node (ref "R118") (pin "2") (pinfunction "2_2") (pintype "passive"))
      (node (ref "U1") (pin "4") (pinfunction "QE_4") (pintype "passive"))
    )
    (net (code "50") (name "L6") (class "Default")
      (node (ref "Q66") (pin "1") (pinfunction "G_1") (pintype "passive"))
      (node (ref "R144") (pin "2") (pinfunction "2_2") (pintype "passive"))
      (node (ref "U1") (pin "5") (pinfunction "QF_5") (pintype "passive"))
    )
    (net (code "51") (name "L7") (class "Default")
      (node (ref "Q79") (pin "1") (pinfunction "G_1") (pintype "passive"))
      (node (ref "R170") (pin "2") (pinfunction "2_2") (pintype "passive"))
      (node (ref "U1") (pin "6") (pinfunction "QG_6") (pintype "passive"))
    )
    (net (code "52") (name "L8") (class "Default")
      (node (ref "Q2") (pin "1") (pinfunction "G_1") (pintype "passive"))
      (node (ref "R15") (pin "2") (pinfunction "2_2") (pintype "passive"))
      (node (ref "U2") (pin "15") (pinfunction "QA_15") (pintype "passive"))
    )
    (net (code "53") (name "L9") (class "Default")
      (node (ref "Q15") (pin "1") (pinfunction "G_1") (pintype "passive"))
      (node (ref "R41") (pin "2") (pinfunction "2_2") (pintype "passive"))
      (node (ref "U2") (pin "1") (pinfunction "QB_1") (pintype "passive"))
    )
    (net (code "54") (name "L10") (class "Default")
      (node (ref "Q28") (pin "1") (pinfunction "G_1") (pintype "passive"))
      (node (ref "R67") (pin "2") (pinfunction "2_2") (pintype "passive"))
      (node (ref "U2") (pin "2") (pinfunction "QC_2") (pintype "passive"))
    )
    (net (code "55") (name "L11") (class "Default")
      (node (ref "Q41") (pin "1") (pinfunction "G_1") (pintype "passive"))
      (node (ref "R93") (pin "2") (pinfunction "2_2") (pintype "passive"))
      (node (ref "U2") (pin "3") (pinfunction "QD_3") (pintype "passive"))
    )
    (net (code "56") (name "L12") (class "Default")
      (node (ref "Q54") (pin "1") (pinfunction "G_1") (pintype "passive"))
      (node (ref "R119") (pin "2") (pinfunction "2_2") (pintype "passive"))
      (node (ref "U2") (pin "4") (pinfunction "QE_4") (pintype "passive"))
    )
    (net (code "57") (name "L13") (class "Default")
      (node (ref "Q67") (pin "1") (pinfunction "G_1") (pintype "passive"))
      (node (ref "R145") (pin "2") (pinfunction "2_2") (pintype "passive"))
      (node (ref "U2") (pin "5") (pinfunction "QF_5") (pintype "passive"))
    )
    (net (code "58") (name "L14") (class "Default")
      (node (ref "Q80") (pin "1") (pinfunction "G_1") (pintype "passive"))
      (node (ref "R171") (pin "2") (pinfunction "2_2") (pintype "passive"))
      (node (ref "U2") (pin "6") (pinfunction "QG_6") (pintype "passive"))
    )
    (net (code "59") (name "L15") (class "Default")
      (node (ref "Q3") (pin "1") (pinfunction "G_1") (pintype "passive"))
      (node (ref "R16") (pin "2") (pinfunction "2_2") (pintype "passive"))
      (node (ref "U3") (pin "15") (pinfunction "QA_15") (pintype "passive"))
    )
    (net (code "60") (name "L16") (class "Default")
      (node (ref "Q16") (pin "1") (pinfunction "G_1") (pintype "passive"))
      (node (ref "R42") (pin "2") (pinfunction "2_2") (pintype "passive"))
      (node (ref "U3") (pin "1") (pinfunction "QB_1") (pintype "passive"))
    )
    (net (code "61") (name "L17") (class "Default")
      (node (ref "Q29") (pin "1") (pinfunction "G_1") (pintype "passive"))
      (node (ref "R68") (pin "2") (pinfunction "2_2") (pintype "passive"))
      (node (ref "U3") (pin "2") (pinfunction "QC_2") (pintype "passive"))
    )
    (net (code "62") (name "L18") (class "Default")
      (node (ref "Q42") (pin "1") (pinfunction "G_1") (pintype "passive"))
      (node (ref "R94") (pin "2") (pinfunction "2_2") (pintype "passive"))
      (node (ref "U3") (pin "3") (pinfunction "QD_3") (pintype "passive"))
    )
    (net (code "63") (name "L19") (class "Default")
      (node (ref "Q55") (pin "1") (pinfunction "G_1") (pintype "passive"))
      (node (ref "R120") (pin "2") (pinfunction "2_2") (pintype "passive"))
      (node (ref "U3") (pin "4") (pinfunction "QE_4") (pintype "passive"))
    )
    (net (code "64") (name "L20") (class "Default")
      (node (ref "Q68") (pin "1") (pinfunction "G_1") (pintype "passive"))
      (node (ref "R146") (pin "2") (pinfunction "2_2") (pintype "passive"))
      (node (ref "U3") (pin "5") (pinfunction "QF_5") (pintype "passive"))
    )
    (net (code "65") (name "L21") (class "Default")
      (node (ref "Q81") (pin "1") (pinfunction "G_1") (pintype "passive"))
      (node (ref "R172") (pin "2") (pinfunction "2_2") (pintype "passive"))
      (node (ref "U3") (pin "6") (pinfunction "QG_6") (pintype "passive"))
    )
    (net (code "66") (name "L22") (class "Default")
      (node (ref "Q4") (pin "1") (pinfunction "G_1") (pintype "passive"))
      (node (ref "R17") (pin "2") (pinfunction "2_2") (pintype "passive"))
      (node (ref "U4") (pin "15") (pinfunction "QA_15") (pintype "passive"))
    )
    (net (code "67") (name "L23") (class "Default")
      (node (ref "Q17") (pin "1") (pinfunction "G_1") (pintype "passive"))
      (node (ref "R43") (pin "2") (pinfunction "2_2") (pintype "passive"))
      (node (ref "U4") (pin "1") (pinfunction "QB_1") (pintype "passive"))
    )
    (net (code "68") (name "L24") (class "Default")
      (node (ref "Q30") (pin "1") (pinfunction "G_1") (pintype "passive"))
      (node (ref "R69") (pin "2") (pinfunction "2_2") (pintype "passive"))
      (node (ref "U4") (pin "2") (pinfunction "QC_2") (pintype "passive"))
    )
    (net (code "69") (name "L25") (class "Default")
      (node (ref "Q43") (pin "1") (pinfunction "G_1") (pintype "passive"))
      (node (ref "R95") (pin "2") (pinfunction "2_2") (pintype "passive"))
      (node (ref "U4") (pin "3") (pinfunction "QD_3") (pintype "passive"))
    )
    (net (code "70") (name "L26") (class "Default")
      (node (ref "Q56") (pin "1") (pinfunction "G_1") (pintype "passive"))
      (node (ref "R121") (pin "2") (pinfunction "2_2") (pintype "passive"))
      (node (ref "U4") (pin "4") (pinfunction "QE_4") (pintype "passive"))
    )
    (net (code "71") (name "L27") (class "Default")
      (node (ref "Q69") (pin "1") (pinfunction "G_1") (pintype "passive"))
      (node (ref "R147") (pin "2") (pinfunction "2_2") (pintype "passive"))
      (node (ref "U4") (pin "5") (pinfunction "QF_5") (pintype "passive"))
    )
    (net (code "72") (name "L28") (class "Default")
      (node (ref "Q82") (pin "1") (pinfunction "G_1") (pintype "passive"))
      (node (ref "R173") (pin "2") (pinfunction "2_2") (pintype "passive"))
      (node (ref "U4") (pin "6") (pinfunction "QG_6") (pintype "passive"))
    )
    (net (code "73") (name "L29") (class "Default")
      (node (ref "Q5") (pin "1") (pinfunction "G_1") (pintype "passive"))
      (node (ref "R18") (pin "2") (pinfunction "2_2") (pintype "passive"))
      (node (ref "U5") (pin "15") (pinfunction "QA_15") (pintype "passive"))
    )
    (net (code "74") (name "L30") (class "Default")
      (node (ref "Q18") (pin "1") (pinfunction "G_1") (pintype "passive"))
      (node (ref "R44") (pin "2") (pinfunction "2_2") (pintype "passive"))
      (node (ref "U5") (pin "1") (pinfunction "QB_1") (pintype "passive"))
    )
    (net (code "75") (name "L31") (class "Default")
      (node (ref "Q31") (pin "1") (pinfunction "G_1") (pintype "passive"))
      (node (ref "R70") (pin "2") (pinfunction "2_2") (pintype "passive"))
      (node (ref "U5") (pin "2") (pinfunction "QC_2") (pintype "passive"))
    )
    (net (code "76") (name "L32") (class "Default")
      (node (ref "Q44") (pin "1") (pinfunction "G_1") (pintype "passive"))
      (node (ref "R96") (pin "2") (pinfunction "2_2") (pintype "passive"))
      (node (ref "U5") (pin "3") (pinfunction "QD_3") (pintype "passive"))
    )
    (net (code "77") (name "L33") (class "Default")
      (node (ref "Q57") (pin "1") (pinfunction "G_1") (pintype "passive"))
      (node (ref "R122") (pin "2") (pinfunction "2_2") (pintype "passive"))
      (node (ref "U5") (pin "4") (pinfunction "QE_4") (pintype "passive"))
    )
    (net (code "78") (name "L34") (class "Default")
      (node (ref "Q70") (pin "1") (pinfunction "G_1") (pintype "passive"))
      (node (ref "R148") (pin "2") (pinfunction "2_2") (pintype "passive"))
      (node (ref "U5") (pin "5") (pinfunction "QF_5") (pintype "passive"))
    )
    (net (code "79") (name "L35") (class "Default")
      (node (ref "Q83") (pin "1") (pinfunction "G_1") (pintype "passive"))
      (node (ref "R174") (pin "2") (pinfunction "2_2") (pintype "passive"))
      (node (ref "U5") (pin "6") (pinfunction "QG_6") (pintype "passive"))
    )
    (net (code "80") (name "L36") (class "Default")
      (node (ref "Q6") (pin "1") (pinfunction "G_1") (pintype "passive"))
      (node (ref "R19") (pin "2") (pinfunction "2_2") (pintype "passive"))
      (node (ref "U6") (pin "15") (pinfunction "QA_15") (pintype "passive"))
    )
    (net (code "81") (name "L37") (class "Default")
      (node (ref "Q19") (pin "1") (pinfunction "G_1") (pintype "passive"))
      (node (ref "R45") (pin "2") (pinfunction "2_2") (pintype "passive"))
      (node (ref "U6") (pin "1") (pinfunction "QB_1") (pintype "passive"))
    )
    (net (code "82") (name "L38") (class "Default")
      (node (ref "Q32") (pin "1") (pinfunction "G_1") (pintype "passive"))
      (node (ref "R71") (pin "2") (pinfunction "2_2") (pintype "passive"))
      (node (ref "U6") (pin "2") (pinfunction "QC_2") (pintype "passive"))
    )
    (net (code "83") (name "L39") (class "Default")
      (node (ref "Q45") (pin "1") (pinfunction "G_1") (pintype "passive"))
      (node (ref "R97") (pin "2") (pinfunction "2_2") (pintype "passive"))
      (node (ref "U6") (pin "3") (pinfunction "QD_3") (pintype "passive"))
    )
    (net (code "84") (name "L40") (class "Default")
      (node (ref "Q58") (pin "1") (pinfunction "G_1") (pintype "passive"))
      (node (ref "R123") (pin "2") (pinfunction "2_2") (pintype "passive"))
      (node (ref "U6") (pin "4") (pinfunction "QE_4") (pintype "passive"))
    )
    (net (code "85") (name "L41") (class "Default")
      (node (ref "Q71") (pin "1") (pinfunction "G_1") (pintype "passive"))
      (node (ref "R149") (pin "2") (pinfunction "2_2") (pintype "passive"))
      (node (ref "U6") (pin "5") (pinfunction "QF_5") (pintype "passive"))
    )
    (net (code "86") (name "L42") (class "Default")
      (node (ref "Q84") (pin "1") (pinfunction "G_1") (pintype "passive"))
      (node (ref "R175") (pin "2") (pinfunction "2_2") (pintype "passive"))
      (node (ref "U6") (pin "6") (pinfunction "QG_6") (pintype "passive"))
    )
    (net (code "87") (name "L43") (class "Default")
      (node (ref "Q7") (pin "1") (pinfunction "G_1") (pintype "passive"))
      (node (ref "R20") (pin "2") (pinfunction "2_2") (pintype "passive"))
      (node (ref "U7") (pin "15") (pinfunction "QA_15") (pintype "passive"))
    )
    (net (code "88") (name "L44") (class "Default")
      (node (ref "Q20") (pin "1") (pinfunction "G_1") (pintype "passive"))
      (node (ref "R46") (pin "2") (pinfunction "2_2") (pintype "passive"))
      (node (ref "U7") (pin "1") (pinfunction "QB_1") (pintype "passive"))
    )
    (net (code "89") (name "L45") (class "Default")
      (node (ref "Q33") (pin "1") (pinfunction "G_1") (pintype "passive"))
      (node (ref "R72") (pin "2") (pinfunction "2_2") (pintype "passive"))
      (node (ref "U7") (pin "2") (pinfunction "QC_2") (pintype "passive"))
    )
    (net (code "90") (name "L46") (class "Default")
      (node (ref "Q46") (pin "1") (pinfunction "G_1") (pintype "passive"))
      (node (ref "R98") (pin "2") (pinfunction "2_2") (pintype "passive"))
      (node (ref "U7") (pin "3") (pinfunction "QD_3") (pintype "passive"))
    )
    (net (code "91") (name "L47") (class "Default")
      (node (ref "Q59") (pin "1") (pinfunction "G_1") (pintype "passive"))
      (node (ref "R124") (pin "2") (pinfunction "2_2") (pintype "passive"))
      (node (ref "U7") (pin "4") (pinfunction "QE_4") (pintype "passive"))
    )
    (net (code "92") (name "L48") (class "Default")
      (node (ref "Q72") (pin "1") (pinfunction "G_1") (pintype "passive"))
      (node (ref "R150") (pin "2") (pinfunction "2_2") (pintype "passive"))
      (node (ref "U7") (pin "5") (pinfunction "QF_5") (pintype "passive"))
    )
    (net (code "93") (name "L49") (class "Default")
      (node (ref "Q85") (pin "1") (pinfunction "G_1") (pintype "passive"))
      (node (ref "R176") (pin "2") (pinfunction "2_2") (pintype "passive"))
      (node (ref "U7") (pin "6") (pinfunction "QG_6") (pintype "passive"))
    )
    (net (code "94") (name "L50") (class "Default")
      (node (ref "Q8") (pin "1") (pinfunction "G_1") (pintype "passive"))
      (node (ref "R21") (pin "2") (pinfunction "2_2") (pintype "passive"))
      (node (ref "U8") (pin "15") (pinfunction "QA_15") (pintype "passive"))
    )
    (net (code "95") (name "L51") (class "Default")
      (node (ref "Q21") (pin "1") (pinfunction "G_1") (pintype "passive"))
      (node (ref "R47") (pin "2") (pinfunction "2_2") (pintype "passive"))
      (node (ref "U8") (pin "1") (pinfunction "QB_1") (pintype "passive"))
    )
    (net (code "96") (name "L52") (class "Default")
      (node (ref "Q34") (pin "1") (pinfunction "G_1") (pintype "passive"))
      (node (ref "R73") (pin "2") (pinfunction "2_2") (pintype "passive"))
      (node (ref "U8") (pin "2") (pinfunction "QC_2") (pintype "passive"))
    )
    (net (code "97") (name "L53") (class "Default")
      (node (ref "Q47") (pin "1") (pinfunction "G_1") (pintype "passive"))
      (node (ref "R99") (pin "2") (pinfunction "2_2") (pintype "passive"))
      (node (ref "U8") (pin "3") (pinfunction "QD_3") (pintype "passive"))
    )
    (net (code "98") (name "L54") (class "Default")
      (node (ref "Q60") (pin "1") (pinfunction "G_1") (pintype "passive"))
      (node (ref "R125") (pin "2") (pinfunction "2_2") (pintype "passive"))
      (node (ref "U8") (pin "4") (pinfunction "QE_4") (pintype "passive"))
    )
    (net (code "99") (name "L55") (class "Default")
      (node (ref "Q73") (pin "1") (pinfunction "G_1") (pintype "passive"))
      (node (ref "R151") (pin "2") (pinfunction "2_2") (pintype "passive"))
      (node (ref "U8") (pin "5") (pinfunction "QF_5") (pintype "passive"))
    )
    (net (code "100") (name "L56") (class "Default")
      (node (ref "Q86") (pin "1") (pinfunction "G_1") (pintype "passive"))
      (node (ref "R177") (pin "2") (pinfunction "2_2") (pintype "passive"))
      (node (ref "U8") (pin "6") (pinfunction "QG_6") (pintype "passive"))
    )
    (net (code "101") (name "L57") (class "Default")
      (node (ref "Q9") (pin "1") (pinfunction "G_1") (pintype "passive"))
      (node (ref "R22") (pin "2") (pinfunction "2_2") (pintype "passive"))
      (node (ref "U9") (pin "15") (pinfunction "QA_15") (pintype "passive"))
    )
    (net (code "102") (name "L58") (class "Default")
      (node (ref "Q22") (pin "1") (pinfunction "G_1") (pintype "passive"))
      (node (ref "R48") (pin "2") (pinfunction "2_2") (pintype "passive"))
      (node (ref "U9") (pin "1") (pinfunction "QB_1") (pintype "passive"))
    )
    (net (code "103") (name "L59") (class "Default")
      (node (ref "Q35") (pin "1") (pinfunction "G_1") (pintype "passive"))
      (node (ref "R74") (pin "2") (pinfunction "2_2") (pintype "passive"))
      (node (ref "U9") (pin "2") (pinfunction "QC_2") (pintype "passive"))
    )
    (net (code "104") (name "L60") (class "Default")
      (node (ref "Q48") (pin "1") (pinfunction "G_1") (pintype "passive"))
      (node (ref "R100") (pin "2") (pinfunction "2_2") (pintype "passive"))
      (node (ref "U9") (pin "3") (pinfunction "QD_3") (pintype "passive"))
    )
    (net (code "105") (name "L61") (class "Default")
      (node (ref "Q61") (pin "1") (pinfunction "G_1") (pintype "passive"))
      (node (ref "R126") (pin "2") (pinfunction "2_2") (pintype "passive"))
      (node (ref "U9") (pin "4") (pinfunction "QE_4") (pintype "passive"))
    )
    (net (code "106") (name "L62") (class "Default")
      (node (ref "Q74") (pin "1") (pinfunction "G_1") (pintype "passive"))
      (node (ref "R152") (pin "2") (pinfunction "2_2") (pintype "passive"))
      (node (ref "U9") (pin "5") (pinfunction "QF_5") (pintype "passive"))
    )
    (net (code "107") (name "L63") (class "Default")
      (node (ref "Q87") (pin "1") (pinfunction "G_1") (pintype "passive"))
      (node (ref "R178") (pin "2") (pinfunction "2_2") (pintype "passive"))
      (node (ref "U9") (pin "6") (pinfunction "QG_6") (pintype "passive"))
    )
    (net (code "108") (name "L64") (class "Default")
      (node (ref "Q10") (pin "1") (pinfunction "G_1") (pintype "passive"))
      (node (ref "R23") (pin "2") (pinfunction "2_2") (pintype "passive"))
      (node (ref "U10") (pin "15") (pinfunction "QA_15") (pintype "passive"))
    )
    (net (code "109") (name "L65") (class "Default")
      (node (ref "Q23") (pin "1") (pinfunction "G_1") (pintype "passive"))
      (node (ref "R49") (pin "2") (pinfunction "2_2") (pintype "passive"))
      (node (ref "U10") (pin "1") (pinfunction "QB_1") (pintype "passive"))
    )
    (net (code "110") (name "L66") (class "Default")
      (node (ref "Q36") (pin "1") (pinfunction "G_1") (pintype "passive"))
      (node (ref "R75") (pin "2") (pinfunction "2_2") (pintype "passive"))
      (node (ref "U10") (pin "2") (pinfunction "QC_2") (pintype "passive"))
    )
    (net (code "111") (name "L67") (class "Default")
      (node (ref "Q49") (pin "1") (pinfunction "G_1") (pintype "passive"))
      (node (ref "R101") (pin "2") (pinfunction "2_2") (pintype "passive"))
      (node (ref "U10") (pin "3") (pinfunction "QD_3") (pintype "passive"))
    )
    (net (code "112") (name "L68") (class "Default")
      (node (ref "Q62") (pin "1") (pinfunction "G_1") (pintype "passive"))
      (node (ref "R127") (pin "2") (pinfunction "2_2") (pintype "passive"))
      (node (ref "U10") (pin "4") (pinfunction "QE_4") (pintype "passive"))
    )
    (net (code "113") (name "L69") (class "Default")
      (node (ref "Q75") (pin "1") (pinfunction "G_1") (pintype "passive"))
      (node (ref "R153") (pin "2") (pinfunction "2_2") (pintype "passive"))
      (node (ref "U10") (pin "5") (pinfunction "QF_5") (pintype "passive"))
    )
    (net (code "114") (name "L70") (class "Default")
      (node (ref "Q88") (pin "1") (pinfunction "G_1") (pintype "passive"))
      (node (ref "R179") (pin "2") (pinfunction "2_2") (pintype "passive"))
      (node (ref "U10") (pin "6") (pinfunction "QG_6") (pintype "passive"))
    )
    (net (code "115") (name "L71") (class "Default")
      (node (ref "Q11") (pin "1") (pinfunction "G_1") (pintype "passive"))
      (node (ref "R24") (pin "2") (pinfunction "2_2") (pintype "passive"))
      (node (ref "U11") (pin "15") (pinfunction "QA_15") (pintype "passive"))
    )
    (net (code "116") (name "L72") (class "Default")
      (node (ref "Q24") (pin "1") (pinfunction "G_1") (pintype "passive"))
      (node (ref "R50") (pin "2") (pinfunction "2_2") (pintype "passive"))
      (node (ref "U11") (pin "1") (pinfunction "QB_1") (pintype "passive"))
    )
    (net (code "117") (name "L73") (class "Default")
      (node (ref "Q37") (pin "1") (pinfunction "G_1") (pintype "passive"))
      (node (ref "R76") (pin "2") (pinfunction "2_2") (pintype "passive"))
      (node (ref "U11") (pin "2") (pinfunction "QC_2") (pintype "passive"))
    )
    (net (code "118") (name "L74") (class "Default")
      (node (ref "Q50") (pin "1") (pinfunction "G_1") (pintype "passive"))
      (node (ref "R102") (pin "2") (pinfunction "2_2") (pintype "passive"))
      (node (ref "U11") (pin "3") (pinfunction "QD_3") (pintype "passive"))
    )
    (net (code "119") (name "L75") (class "Default")
      (node (ref "Q63") (pin "1") (pinfunction "G_1") (pintype "passive"))
      (node (ref "R128") (pin "2") (pinfunction "2_2") (pintype "passive"))
      (node (ref "U11") (pin "4") (pinfunction "QE_4") (pintype "passive"))
    )
    (net (code "120") (name "L76") (class "Default")
      (node (ref "Q76") (pin "1") (pinfunction "G_1") (pintype "passive"))
      (node (ref "R154") (pin "2") (pinfunction "2_2") (pintype "passive"))
      (node (ref "U11") (pin "5") (pinfunction "QF_5") (pintype "passive"))
    )
    (net (code "121") (name "L77") (class "Default")
      (node (ref "Q89") (pin "1") (pinfunction "G_1") (pintype "passive"))
      (node (ref "R180") (pin "2") (pinfunction "2_2") (pintype "passive"))
      (node (ref "U11") (pin "6") (pinfunction "QG_6") (pintype "passive"))
    )
    (net (code "122") (name "L78") (class "Default")
      (node (ref "Q12") (pin "1") (pinfunction "G_1") (pintype "passive"))
      (node (ref "R25") (pin "2") (pinfunction "2_2") (pintype "passive"))
      (node (ref "U13") (pin "15") (pinfunction "QA_15") (pintype "passive"))
    )
    (net (code "123") (name "L79") (class "Default")
      (node (ref "Q25") (pin "1") (pinfunction "G_1") (pintype "passive"))
      (node (ref "R51") (pin "2") (pinfunction "2_2") (pintype "passive"))
      (node (ref "U13") (pin "1") (pinfunction "QB_1") (pintype "passive"))
    )
    (net (code "124") (name "L80") (class "Default")
      (node (ref "Q38") (pin "1") (pinfunction "G_1") (pintype "passive"))
      (node (ref "R77") (pin "2") (pinfunction "2_2") (pintype "passive"))
      (node (ref "U13") (pin "2") (pinfunction "QC_2") (pintype "passive"))
    )
    (net (code "125") (name "L81") (class "Default")
      (node (ref "Q51") (pin "1") (pinfunction "G_1") (pintype "passive"))
      (node (ref "R103") (pin "2") (pinfunction "2_2") (pintype "passive"))
      (node (ref "U13") (pin "3") (pinfunction "QD_3") (pintype "passive"))
    )
    (net (code "126") (name "L82") (class "Default")
      (node (ref "Q64") (pin "1") (pinfunction "G_1") (pintype "passive"))
      (node (ref "R129") (pin "2") (pinfunction "2_2") (pintype "passive"))
      (node (ref "U13") (pin "4") (pinfunction "QE_4") (pintype "passive"))
    )
    (net (code "127") (name "L83") (class "Default")
      (node (ref "Q77") (pin "1") (pinfunction "G_1") (pintype "passive"))
      (node (ref "R155") (pin "2") (pinfunction "2_2") (pintype "passive"))
      (node (ref "U13") (pin "5") (pinfunction "QF_5") (pintype "passive"))
    )
    (net (code "128") (name "L84") (class "Default")
      (node (ref "Q90") (pin "1") (pinfunction "G_1") (pintype "passive"))
      (node (ref "R181") (pin "2") (pinfunction "2_2") (pintype "passive"))
      (node (ref "U13") (pin "6") (pinfunction "QG_6") (pintype "passive"))
    )
    (net (code "129") (name "L85") (class "Default")
      (node (ref "Q13") (pin "1") (pinfunction "G_1") (pintype "passive"))
      (node (ref "R26") (pin "2") (pinfunction "2_2") (pintype "passive"))
      (node (ref "U12") (pin "15") (pinfunction "QA_15") (pintype "passive"))
    )
    (net (code "130") (name "L86") (class "Default")
      (node (ref "Q26") (pin "1") (pinfunction "G_1") (pintype "passive"))
      (node (ref "R52") (pin "2") (pinfunction "2_2") (pintype "passive"))
      (node (ref "U12") (pin "1") (pinfunction "QB_1") (pintype "passive"))
    )
    (net (code "131") (name "L87") (class "Default")
      (node (ref "Q39") (pin "1") (pinfunction "G_1") (pintype "passive"))
      (node (ref "R78") (pin "2") (pinfunction "2_2") (pintype "passive"))
      (node (ref "U12") (pin "2") (pinfunction "QC_2") (pintype "passive"))
    )
    (net (code "132") (name "L88") (class "Default")
      (node (ref "Q52") (pin "1") (pinfunction "G_1") (pintype "passive"))
      (node (ref "R104") (pin "2") (pinfunction "2_2") (pintype "passive"))
      (node (ref "U12") (pin "3") (pinfunction "QD_3") (pintype "passive"))
    )
    (net (code "133") (name "L89") (class "Default")
      (node (ref "Q65") (pin "1") (pinfunction "G_1") (pintype "passive"))
      (node (ref "R130") (pin "2") (pinfunction "2_2") (pintype "passive"))
      (node (ref "U12") (pin "4") (pinfunction "QE_4") (pintype "passive"))
    )
    (net (code "134") (name "L90") (class "Default")
      (node (ref "Q78") (pin "1") (pinfunction "G_1") (pintype "passive"))
      (node (ref "R156") (pin "2") (pinfunction "2_2") (pintype "passive"))
      (node (ref "U12") (pin "5") (pinfunction "QF_5") (pintype "passive"))
    )
    (net (code "135") (name "L91") (class "Default")
      (node (ref "Q91") (pin "1") (pinfunction "G_1") (pintype "passive"))
      (node (ref "R182") (pin "2") (pinfunction "2_2") (pintype "passive"))
      (node (ref "U12") (pin "6") (pinfunction "QG_6") (pintype "passive"))
    )
    (net (code "136") (name "Net-(BT1-Pad3)") (class "Default")
      (node (ref "BT1") (pin "3") (pinfunction "3_3") (pintype "passive"))
      (node (ref "R1") (pin "2") (pinfunction "2_2") (pintype "passive"))
    )
    (net (code "137") (name "Net-(BT2-Pad3)") (class "Default")
      (node (ref "BT2") (pin "3") (pinfunction "3_3") (pintype "passive"))
      (node (ref "R2") (pin "2") (pinfunction "2_2") (pintype "passive"))
    )
    (net (code "138") (name "Net-(BT3-Pad3)") (class "Default")
      (node (ref "BT3") (pin "3") (pinfunction "3_3") (pintype "passive"))
      (node (ref "R3") (pin "2") (pinfunction "2_2") (pintype "passive"))
    )
    (net (code "139") (name "Net-(BT4-Pad3)") (class "Default")
      (node (ref "BT4") (pin "3") (pinfunction "3_3") (pintype "passive"))
      (node (ref "R4") (pin "2") (pinfunction "2_2") (pintype "passive"))
    )
    (net (code "140") (name "Net-(BT5-Pad3)") (class "Default")
      (node (ref "BT5") (pin "3") (pinfunction "3_3") (pintype "passive"))
      (node (ref "R5") (pin "2") (pinfunction "2_2") (pintype "passive"))
    )
    (net (code "141") (name "Net-(BT6-Pad3)") (class "Default")
      (node (ref "BT6") (pin "3") (pinfunction "3_3") (pintype "passive"))
      (node (ref "R6") (pin "2") (pinfunction "2_2") (pintype "passive"))
    )
    (net (code "142") (name "Net-(BT7-Pad3)") (class "Default")
      (node (ref "BT7") (pin "3") (pinfunction "3_3") (pintype "passive"))
      (node (ref "R7") (pin "2") (pinfunction "2_2") (pintype "passive"))
    )
    (net (code "143") (name "Net-(BT8-Pad3)") (class "Default")
      (node (ref "BT8") (pin "3") (pinfunction "3_3") (pintype "passive"))
      (node (ref "R8") (pin "2") (pinfunction "2_2") (pintype "passive"))
    )
    (net (code "144") (name "Net-(BT9-Pad3)") (class "Default")
      (node (ref "BT9") (pin "3") (pinfunction "3_3") (pintype "passive"))
      (node (ref "R9") (pin "2") (pinfunction "2_2") (pintype "passive"))
    )
    (net (code "145") (name "Net-(BT10-Pad3)") (class "Default")
      (node (ref "BT10") (pin "3") (pinfunction "3_3") (pintype "passive"))
      (node (ref "R10") (pin "2") (pinfunction "2_2") (pintype "passive"))
    )
    (net (code "146") (name "Net-(BT11-Pad3)") (class "Default")
      (node (ref "BT11") (pin "3") (pinfunction "3_3") (pintype "passive"))
      (node (ref "R11") (pin "2") (pinfunction "2_2") (pintype "passive"))
    )
    (net (code "147") (name "Net-(BT12-Pad3)") (class "Default")
      (node (ref "BT12") (pin "3") (pinfunction "3_3") (pintype "passive"))
      (node (ref "R12") (pin "2") (pinfunction "2_2") (pintype "passive"))
    )
    (net (code "148") (name "Net-(BT13-Pad3)") (class "Default")
      (node (ref "BT13") (pin "3") (pinfunction "3_3") (pintype "passive"))
      (node (ref "R13") (pin "2") (pinfunction "2_2") (pintype "passive"))
    )
    (net (code "149") (name "Net-(BT14-Pad3)") (class "Default")
      (node (ref "BT14") (pin "3") (pinfunction "3_3") (pintype "passive"))
      (node (ref "R27") (pin "2") (pinfunction "2_2") (pintype "passive"))
    )
    (net (code "150") (name "Net-(BT15-Pad3)") (class "Default")
      (node (ref "BT15") (pin "3") (pinfunction "3_3") (pintype "passive"))
      (node (ref "R28") (pin "2") (pinfunction "2_2") (pintype "passive"))
    )
    (net (code "151") (name "Net-(BT16-Pad3)") (class "Default")
      (node (ref "BT16") (pin "3") (pinfunction "3_3") (pintype "passive"))
      (node (ref "R29") (pin "2") (pinfunction "2_2") (pintype "passive"))
    )
    (net (code "152") (name "Net-(BT17-Pad3)") (class "Default")
      (node (ref "BT17") (pin "3") (pinfunction "3_3") (pintype "passive"))
      (node (ref "R30") (pin "2") (pinfunction "2_2") (pintype "passive"))
    )
    (net (code "153") (name "Net-(BT18-Pad3)") (class "Default")
      (node (ref "BT18") (pin "3") (pinfunction "3_3") (pintype "passive"))
      (node (ref "R31") (pin "2") (pinfunction "2_2") (pintype "passive"))
    )
    (net (code "154") (name "Net-(BT19-Pad3)") (class "Default")
      (node (ref "BT19") (pin "3") (pinfunction "3_3") (pintype "passive"))
      (node (ref "R32") (pin "2") (pinfunction "2_2") (pintype "passive"))
    )
    (net (code "155") (name "Net-(BT20-Pad3)") (class "Default")
      (node (ref "BT20") (pin "3") (pinfunction "3_3") (pintype "passive"))
      (node (ref "R33") (pin "2") (pinfunction "2_2") (pintype "passive"))
    )
    (net (code "156") (name "Net-(BT21-Pad3)") (class "Default")
      (node (ref "BT21") (pin "3") (pinfunction "3_3") (pintype "passive"))
      (node (ref "R34") (pin "2") (pinfunction "2_2") (pintype "passive"))
    )
    (net (code "157") (name "Net-(BT22-Pad3)") (class "Default")
      (node (ref "BT22") (pin "3") (pinfunction "3_3") (pintype "passive"))
      (node (ref "R35") (pin "2") (pinfunction "2_2") (pintype "passive"))
    )
    (net (code "158") (name "Net-(BT23-Pad3)") (class "Default")
      (node (ref "BT23") (pin "3") (pinfunction "3_3") (pintype "passive"))
      (node (ref "R36") (pin "2") (pinfunction "2_2") (pintype "passive"))
    )
    (net (code "159") (name "Net-(BT24-Pad3)") (class "Default")
      (node (ref "BT24") (pin "3") (pinfunction "3_3") (pintype "passive"))
      (node (ref "R37") (pin "2") (pinfunction "2_2") (pintype "passive"))
    )
    (net (code "160") (name "Net-(BT25-Pad3)") (class "Default")
      (node (ref "BT25") (pin "3") (pinfunction "3_3") (pintype "passive"))
      (node (ref "R38") (pin "2") (pinfunction "2_2") (pintype "passive"))
    )
    (net (code "161") (name "Net-(BT26-Pad3)") (class "Default")
      (node (ref "BT26") (pin "3") (pinfunction "3_3") (pintype "passive"))
      (node (ref "R39") (pin "2") (pinfunction "2_2") (pintype "passive"))
    )
    (net (code "162") (name "Net-(BT27-Pad3)") (class "Default")
      (node (ref "BT27") (pin "3") (pinfunction "3_3") (pintype "passive"))
      (node (ref "R53") (pin "2") (pinfunction "2_2") (pintype "passive"))
    )
    (net (code "163") (name "Net-(BT28-Pad3)") (class "Default")
      (node (ref "BT28") (pin "3") (pinfunction "3_3") (pintype "passive"))
      (node (ref "R54") (pin "2") (pinfunction "2_2") (pintype "passive"))
    )
    (net (code "164") (name "Net-(BT29-Pad3)") (class "Default")
      (node (ref "BT29") (pin "3") (pinfunction "3_3") (pintype "passive"))
      (node (ref "R55") (pin "2") (pinfunction "2_2") (pintype "passive"))
    )
    (net (code "165") (name "Net-(BT30-Pad3)") (class "Default")
      (node (ref "BT30") (pin "3") (pinfunction "3_3") (pintype "passive"))
      (node (ref "R56") (pin "2") (pinfunction "2_2") (pintype "passive"))
    )
    (net (code "166") (name "Net-(BT31-Pad3)") (class "Default")
      (node (ref "BT31") (pin "3") (pinfunction "3_3") (pintype "passive"))
      (node (ref "R57") (pin "2") (pinfunction "2_2") (pintype "passive"))
    )
    (net (code "167") (name "Net-(BT32-Pad3)") (class "Default")
      (node (ref "BT32") (pin "3") (pinfunction "3_3") (pintype "passive"))
      (node (ref "R58") (pin "2") (pinfunction "2_2") (pintype "passive"))
    )
    (net (code "168") (name "Net-(BT33-Pad3)") (class "Default")
      (node (ref "BT33") (pin "3") (pinfunction "3_3") (pintype "passive"))
      (node (ref "R59") (pin "2") (pinfunction "2_2") (pintype "passive"))
    )
    (net (code "169") (name "Net-(BT34-Pad3)") (class "Default")
      (node (ref "BT34") (pin "3") (pinfunction "3_3") (pintype "passive"))
      (node (ref "R60") (pin "2") (pinfunction "2_2") (pintype "passive"))
    )
    (net (code "170") (name "Net-(BT35-Pad3)") (class "Default")
      (node (ref "BT35") (pin "3") (pinfunction "3_3") (pintype "passive"))
      (node (ref "R61") (pin "2") (pinfunction "2_2") (pintype "passive"))
    )
    (net (code "171") (name "Net-(BT36-Pad3)") (class "Default")
      (node (ref "BT36") (pin "3") (pinfunction "3_3") (pintype "passive"))
      (node (ref "R62") (pin "2") (pinfunction "2_2") (pintype "passive"))
    )
    (net (code "172") (name "Net-(BT37-Pad3)") (class "Default")
      (node (ref "BT37") (pin "3") (pinfunction "3_3") (pintype "passive"))
      (node (ref "R63") (pin "2") (pinfunction "2_2") (pintype "passive"))
    )
    (net (code "173") (name "Net-(BT38-Pad3)") (class "Default")
      (node (ref "BT38") (pin "3") (pinfunction "3_3") (pintype "passive"))
      (node (ref "R64") (pin "2") (pinfunction "2_2") (pintype "passive"))
    )
    (net (code "174") (name "Net-(BT39-Pad3)") (class "Default")
      (node (ref "BT39") (pin "3") (pinfunction "3_3") (pintype "passive"))
      (node (ref "R65") (pin "2") (pinfunction "2_2") (pintype "passive"))
    )
    (net (code "175") (name "Net-(BT40-Pad3)") (class "Default")
      (node (ref "BT40") (pin "3") (pinfunction "3_3") (pintype "passive"))
      (node (ref "R79") (pin "2") (pinfunction "2_2") (pintype "passive"))
    )
    (net (code "176") (name "Net-(BT41-Pad3)") (class "Default")
      (node (ref "BT41") (pin "3") (pinfunction "3_3") (pintype "passive"))
      (node (ref "R80") (pin "2") (pinfunction "2_2") (pintype "passive"))
    )
    (net (code "177") (name "Net-(BT42-Pad3)") (class "Default")
      (node (ref "BT42") (pin "3") (pinfunction "3_3") (pintype "passive"))
      (node (ref "R81") (pin "2") (pinfunction "2_2") (pintype "passive"))
    )
    (net (code "178") (name "Net-(BT43-Pad3)") (class "Default")
      (node (ref "BT43") (pin "3") (pinfunction "3_3") (pintype "passive"))
      (node (ref "R82") (pin "2") (pinfunction "2_2") (pintype "passive"))
    )
    (net (code "179") (name "Net-(BT44-Pad3)") (class "Default")
      (node (ref "BT44") (pin "3") (pinfunction "3_3") (pintype "passive"))
      (node (ref "R83") (pin "2") (pinfunction "2_2") (pintype "passive"))
    )
    (net (code "180") (name "Net-(BT45-Pad3)") (class "Default")
      (node (ref "BT45") (pin "3") (pinfunction "3_3") (pintype "passive"))
      (node (ref "R84") (pin "2") (pinfunction "2_2") (pintype "passive"))
    )
    (net (code "181") (name "Net-(BT46-Pad3)") (class "Default")
      (node (ref "BT46") (pin "3") (pinfunction "3_3") (pintype "passive"))
      (node (ref "R85") (pin "2") (pinfunction "2_2") (pintype "passive"))
    )
    (net (code "182") (name "Net-(BT47-Pad3)") (class "Default")
      (node (ref "BT47") (pin "3") (pinfunction "3_3") (pintype "passive"))
      (node (ref "R86") (pin "2") (pinfunction "2_2") (pintype "passive"))
    )
    (net (code "183") (name "Net-(BT48-Pad3)") (class "Default")
      (node (ref "BT48") (pin "3") (pinfunction "3_3") (pintype "passive"))
      (node (ref "R87") (pin "2") (pinfunction "2_2") (pintype "passive"))
    )
    (net (code "184") (name "Net-(BT49-Pad3)") (class "Default")
      (node (ref "BT49") (pin "3") (pinfunction "3_3") (pintype "passive"))
      (node (ref "R88") (pin "2") (pinfunction "2_2") (pintype "passive"))
    )
    (net (code "185") (name "Net-(BT50-Pad3)") (class "Default")
      (node (ref "BT50") (pin "3") (pinfunction "3_3") (pintype "passive"))
      (node (ref "R89") (pin "2") (pinfunction "2_2") (pintype "passive"))
    )
    (net (code "186") (name "Net-(BT51-Pad3)") (class "Default")
      (node (ref "BT51") (pin "3") (pinfunction "3_3") (pintype "passive"))
      (node (ref "R90") (pin "2") (pinfunction "2_2") (pintype "passive"))
    )
    (net (code "187") (name "Net-(BT52-Pad3)") (class "Default")
      (node (ref "BT52") (pin "3") (pinfunction "3_3") (pintype "passive"))
      (node (ref "R91") (pin "2") (pinfunction "2_2") (pintype "passive"))
    )
    (net (code "188") (name "Net-(BT53-Pad3)") (class "Default")
      (node (ref "BT53") (pin "3") (pinfunction "3_3") (pintype "passive"))
      (node (ref "R105") (pin "2") (pinfunction "2_2") (pintype "passive"))
    )
    (net (code "189") (name "Net-(BT54-Pad3)") (class "Default")
      (node (ref "BT54") (pin "3") (pinfunction "3_3") (pintype "passive"))
      (node (ref "R106") (pin "2") (pinfunction "2_2") (pintype "passive"))
    )
    (net (code "190") (name "Net-(BT55-Pad3)") (class "Default")
      (node (ref "BT55") (pin "3") (pinfunction "3_3") (pintype "passive"))
      (node (ref "R107") (pin "2") (pinfunction "2_2") (pintype "passive"))
    )
    (net (code "191") (name "Net-(BT56-Pad3)") (class "Default")
      (node (ref "BT56") (pin "3") (pinfunction "3_3") (pintype "passive"))
      (node (ref "R108") (pin "2") (pinfunction "2_2") (pintype "passive"))
    )
    (net (code "192") (name "Net-(BT57-Pad3)") (class "Default")
      (node (ref "BT57") (pin "3") (pinfunction "3_3") (pintype "passive"))
      (node (ref "R109") (pin "2") (pinfunction "2_2") (pintype "passive"))
    )
    (net (code "193") (name "Net-(BT58-Pad3)") (class "Default")
      (node (ref "BT58") (pin "3") (pinfunction "3_3") (pintype "passive"))
      (node (ref "R110") (pin "2") (pinfunction "2_2") (pintype "passive"))
    )
    (net (code "194") (name "Net-(BT59-Pad3)") (class "Default")
      (node (ref "BT59") (pin "3") (pinfunction "3_3") (pintype "passive"))
      (node (ref "R111") (pin "2") (pinfunction "2_2") (pintype "passive"))
    )
    (net (code "195") (name "Net-(BT60-Pad3)") (class "Default")
      (node (ref "BT60") (pin "3") (pinfunction "3_3") (pintype "passive"))
      (node (ref "R112") (pin "2") (pinfunction "2_2") (pintype "passive"))
    )
    (net (code "196") (name "Net-(BT61-Pad3)") (class "Default")
      (node (ref "BT61") (pin "3") (pinfunction "3_3") (pintype "passive"))
      (node (ref "R113") (pin "2") (pinfunction "2_2") (pintype "passive"))
    )
    (net (code "197") (name "Net-(BT62-Pad3)") (class "Default")
      (node (ref "BT62") (pin "3") (pinfunction "3_3") (pintype "passive"))
      (node (ref "R114") (pin "2") (pinfunction "2_2") (pintype "passive"))
    )
    (net (code "198") (name "Net-(BT63-Pad3)") (class "Default")
      (node (ref "BT63") (pin "3") (pinfunction "3_3") (pintype "passive"))
      (node (ref "R115") (pin "2") (pinfunction "2_2") (pintype "passive"))
    )
    (net (code "199") (name "Net-(BT64-Pad3)") (class "Default")
      (node (ref "BT64") (pin "3") (pinfunction "3_3") (pintype "passive"))
      (node (ref "R116") (pin "2") (pinfunction "2_2") (pintype "passive"))
    )
    (net (code "200") (name "Net-(BT65-Pad3)") (class "Default")
      (node (ref "BT65") (pin "3") (pinfunction "3_3") (pintype "passive"))
      (node (ref "R117") (pin "2") (pinfunction "2_2") (pintype "passive"))
    )
    (net (code "201") (name "Net-(BT66-Pad3)") (class "Default")
      (node (ref "BT66") (pin "3") (pinfunction "3_3") (pintype "passive"))
      (node (ref "R131") (pin "2") (pinfunction "2_2") (pintype "passive"))
    )
    (net (code "202") (name "Net-(BT67-Pad3)") (class "Default")
      (node (ref "BT67") (pin "3") (pinfunction "3_3") (pintype "passive"))
      (node (ref "R132") (pin "2") (pinfunction "2_2") (pintype "passive"))
    )
    (net (code "203") (name "Net-(BT68-Pad3)") (class "Default")
      (node (ref "BT68") (pin "3") (pinfunction "3_3") (pintype "passive"))
      (node (ref "R133") (pin "2") (pinfunction "2_2") (pintype "passive"))
    )
    (net (code "204") (name "Net-(BT69-Pad3)") (class "Default")
      (node (ref "BT69") (pin "3") (pinfunction "3_3") (pintype "passive"))
      (node (ref "R134") (pin "2") (pinfunction "2_2") (pintype "passive"))
    )
    (net (code "205") (name "Net-(BT70-Pad3)") (class "Default")
      (node (ref "BT70") (pin "3") (pinfunction "3_3") (pintype "passive"))
      (node (ref "R135") (pin "2") (pinfunction "2_2") (pintype "passive"))
    )
    (net (code "206") (name "Net-(BT71-Pad3)") (class "Default")
      (node (ref "BT71") (pin "3") (pinfunction "3_3") (pintype "passive"))
      (node (ref "R136") (pin "2") (pinfunction "2_2") (pintype "passive"))
    )
    (net (code "207") (name "Net-(BT72-Pad3)") (class "Default")
      (node (ref "BT72") (pin "3") (pinfunction "3_3") (pintype "passive"))
      (node (ref "R137") (pin "2") (pinfunction "2_2") (pintype "passive"))
    )
    (net (code "208") (name "Net-(BT73-Pad3)") (class "Default")
      (node (ref "BT73") (pin "3") (pinfunction "3_3") (pintype "passive"))
      (node (ref "R138") (pin "2") (pinfunction "2_2") (pintype "passive"))
    )
    (net (code "209") (name "Net-(BT74-Pad3)") (class "Default")
      (node (ref "BT74") (pin "3") (pinfunction "3_3") (pintype "passive"))
      (node (ref "R139") (pin "2") (pinfunction "2_2") (pintype "passive"))
    )
    (net (code "210") (name "Net-(BT75-Pad3)") (class "Default")
      (node (ref "BT75") (pin "3") (pinfunction "3_3") (pintype "passive"))
      (node (ref "R140") (pin "2") (pinfunction "2_2") (pintype "passive"))
    )
    (net (code "211") (name "Net-(BT76-Pad3)") (class "Default")
      (node (ref "BT76") (pin "3") (pinfunction "3_3") (pintype "passive"))
      (node (ref "R141") (pin "2") (pinfunction "2_2") (pintype "passive"))
    )
    (net (code "212") (name "Net-(BT77-Pad3)") (class "Default")
      (node (ref "BT77") (pin "3") (pinfunction "3_3") (pintype "passive"))
      (node (ref "R142") (pin "2") (pinfunction "2_2") (pintype "passive"))
    )
    (net (code "213") (name "Net-(BT78-Pad3)") (class "Default")
      (node (ref "BT78") (pin "3") (pinfunction "3_3") (pintype "passive"))
      (node (ref "R143") (pin "2") (pinfunction "2_2") (pintype "passive"))
    )
    (net (code "214") (name "Net-(BT79-Pad3)") (class "Default")
      (node (ref "BT79") (pin "3") (pinfunction "3_3") (pintype "passive"))
      (node (ref "R157") (pin "2") (pinfunction "2_2") (pintype "passive"))
    )
    (net (code "215") (name "Net-(BT80-Pad3)") (class "Default")
      (node (ref "BT80") (pin "3") (pinfunction "3_3") (pintype "passive"))
      (node (ref "R158") (pin "2") (pinfunction "2_2") (pintype "passive"))
    )
    (net (code "216") (name "Net-(BT81-Pad3)") (class "Default")
      (node (ref "BT81") (pin "3") (pinfunction "3_3") (pintype "passive"))
      (node (ref "R159") (pin "2") (pinfunction "2_2") (pintype "passive"))
    )
    (net (code "217") (name "Net-(BT82-Pad3)") (class "Default")
      (node (ref "BT82") (pin "3") (pinfunction "3_3") (pintype "passive"))
      (node (ref "R160") (pin "2") (pinfunction "2_2") (pintype "passive"))
    )
    (net (code "218") (name "Net-(BT83-Pad3)") (class "Default")
      (node (ref "BT83") (pin "3") (pinfunction "3_3") (pintype "passive"))
      (node (ref "R161") (pin "2") (pinfunction "2_2") (pintype "passive"))
    )
    (net (code "219") (name "Net-(BT84-Pad3)") (class "Default")
      (node (ref "BT84") (pin "3") (pinfunction "3_3") (pintype "passive"))
      (node (ref "R162") (pin "2") (pinfunction "2_2") (pintype "passive"))
    )
    (net (code "220") (name "Net-(BT85-Pad3)") (class "Default")
      (node (ref "BT85") (pin "3") (pinfunction "3_3") (pintype "passive"))
      (node (ref "R163") (pin "2") (pinfunction "2_2") (pintype "passive"))
    )
    (net (code "221") (name "Net-(BT86-Pad3)") (class "Default")
      (node (ref "BT86") (pin "3") (pinfunction "3_3") (pintype "passive"))
      (node (ref "R164") (pin "2") (pinfunction "2_2") (pintype "passive"))
    )
    (net (code "222") (name "Net-(BT87-Pad3)") (class "Default")
      (node (ref "BT87") (pin "3") (pinfunction "3_3") (pintype "passive"))
      (node (ref "R165") (pin "2") (pinfunction "2_2") (pintype "passive"))
    )
    (net (code "223") (name "Net-(BT88-Pad3)") (class "Default")
      (node (ref "BT88") (pin "3") (pinfunction "3_3") (pintype "passive"))
      (node (ref "R166") (pin "2") (pinfunction "2_2") (pintype "passive"))
    )
    (net (code "224") (name "Net-(BT89-Pad3)") (class "Default")
      (node (ref "BT89") (pin "3") (pinfunction "3_3") (pintype "passive"))
      (node (ref "R167") (pin "2") (pinfunction "2_2") (pintype "passive"))
    )
    (net (code "225") (name "Net-(BT90-Pad3)") (class "Default")
      (node (ref "BT90") (pin "3") (pinfunction "3_3") (pintype "passive"))
      (node (ref "R168") (pin "2") (pinfunction "2_2") (pintype "passive"))
    )
    (net (code "226") (name "Net-(BT91-Pad3)") (class "Default")
      (node (ref "BT91") (pin "3") (pinfunction "3_3") (pintype "passive"))
      (node (ref "R169") (pin "2") (pinfunction "2_2") (pintype "passive"))
    )
    (net (code "227") (name "Net-(H1-Pad3)") (class "Default")
      (node (ref "H1") (pin "3") (pinfunction "3_3") (pintype "passive"))
      (node (ref "R197") (pin "2") (pinfunction "2_2") (pintype "passive"))
    )
    (net (code "228") (name "Net-(H2-Pad3)") (class "Default")
      (node (ref "H2") (pin "3") (pinfunction "3_3") (pintype "passive"))
      (node (ref "R199") (pin "2") (pinfunction "2_2") (pintype "passive"))
    )
    (net (code "229") (name "Net-(H3-Pad3)") (class "Default")
      (node (ref "H3") (pin "3") (pinfunction "3_3") (pintype "passive"))
      (node (ref "R200") (pin "2") (pinfunction "2_2") (pintype "passive"))
    )
    (net (code "230") (name "Net-(Q1-D)") (class "Default")
      (node (ref "BT1") (pin "4") (pinfunction "4_4") (pintype "passive"))
      (node (ref "Q1") (pin "3") (pinfunction "D_3") (pintype "passive"))
    )
    (net (code "231") (name "Net-(Q2-D)") (class "Default")
      (node (ref "BT2") (pin "4") (pinfunction "4_4") (pintype "passive"))
      (node (ref "Q2") (pin "3") (pinfunction "D_3") (pintype "passive"))
    )
    (net (code "232") (name "Net-(Q3-D)") (class "Default")
      (node (ref "BT3") (pin "4") (pinfunction "4_4") (pintype "passive"))
      (node (ref "Q3") (pin "3") (pinfunction "D_3") (pintype "passive"))
    )
    (net (code "233") (name "Net-(Q4-D)") (class "Default")
      (node (ref "BT4") (pin "4") (pinfunction "4_4") (pintype "passive"))
      (node (ref "Q4") (pin "3") (pinfunction "D_3") (pintype "passive"))
    )
    (net (code "234") (name "Net-(Q5-D)") (class "Default")
      (node (ref "BT5") (pin "4") (pinfunction "4_4") (pintype "passive"))
      (node (ref "Q5") (pin "3") (pinfunction "D_3") (pintype "passive"))
    )
    (net (code "235") (name "Net-(Q6-D)") (class "Default")
      (node (ref "BT6") (pin "4") (pinfunction "4_4") (pintype "passive"))
      (node (ref "Q6") (pin "3") (pinfunction "D_3") (pintype "passive"))
    )
    (net (code "236") (name "Net-(Q7-D)") (class "Default")
      (node (ref "BT7") (pin "4") (pinfunction "4_4") (pintype "passive"))
      (node (ref "Q7") (pin "3") (pinfunction "D_3") (pintype "passive"))
    )
    (net (code "237") (name "Net-(Q8-D)") (class "Default")
      (node (ref "BT8") (pin "4") (pinfunction "4_4") (pintype "passive"))
      (node (ref "Q8") (pin "3") (pinfunction "D_3") (pintype "passive"))
    )
    (net (code "238") (name "Net-(Q9-D)") (class "Default")
      (node (ref "BT9") (pin "4") (pinfunction "4_4") (pintype "passive"))
      (node (ref "Q9") (pin "3") (pinfunction "D_3") (pintype "passive"))
    )
    (net (code "239") (name "Net-(Q10-D)") (class "Default")
      (node (ref "BT10") (pin "4") (pinfunction "4_4") (pintype "passive"))
      (node (ref "Q10") (pin "3") (pinfunction "D_3") (pintype "passive"))
    )
    (net (code "240") (name "Net-(Q11-D)") (class "Default")
      (node (ref "BT11") (pin "4") (pinfunction "4_4") (pintype "passive"))
      (node (ref "Q11") (pin "3") (pinfunction "D_3") (pintype "passive"))
    )
    (net (code "241") (name "Net-(Q12-D)") (class "Default")
      (node (ref "BT12") (pin "4") (pinfunction "4_4") (pintype "passive"))
      (node (ref "Q12") (pin "3") (pinfunction "D_3") (pintype "passive"))
    )
    (net (code "242") (name "Net-(Q13-D)") (class "Default")
      (node (ref "BT13") (pin "4") (pinfunction "4_4") (pintype "passive"))
      (node (ref "Q13") (pin "3") (pinfunction "D_3") (pintype "passive"))
    )
    (net (code "243") (name "Net-(Q14-D)") (class "Default")
      (node (ref "BT14") (pin "4") (pinfunction "4_4") (pintype "passive"))
      (node (ref "Q14") (pin "3") (pinfunction "D_3") (pintype "passive"))
    )
    (net (code "244") (name "Net-(Q15-D)") (class "Default")
      (node (ref "BT15") (pin "4") (pinfunction "4_4") (pintype "passive"))
      (node (ref "Q15") (pin "3") (pinfunction "D_3") (pintype "passive"))
    )
    (net (code "245") (name "Net-(Q16-D)") (class "Default")
      (node (ref "BT16") (pin "4") (pinfunction "4_4") (pintype "passive"))
      (node (ref "Q16") (pin "3") (pinfunction "D_3") (pintype "passive"))
    )
    (net (code "246") (name "Net-(Q17-D)") (class "Default")
      (node (ref "BT17") (pin "4") (pinfunction "4_4") (pintype "passive"))
      (node (ref "Q17") (pin "3") (pinfunction "D_3") (pintype "passive"))
    )
    (net (code "247") (name "Net-(Q18-D)") (class "Default")
      (node (ref "BT18") (pin "4") (pinfunction "4_4") (pintype "passive"))
      (node (ref "Q18") (pin "3") (pinfunction "D_3") (pintype "passive"))
    )
    (net (code "248") (name "Net-(Q19-D)") (class "Default")
      (node (ref "BT19") (pin "4") (pinfunction "4_4") (pintype "passive"))
      (node (ref "Q19") (pin "3") (pinfunction "D_3") (pintype "passive"))
    )
    (net (code "249") (name "Net-(Q20-D)") (class "Default")
      (node (ref "BT20") (pin "4") (pinfunction "4_4") (pintype "passive"))
      (node (ref "Q20") (pin "3") (pinfunction "D_3") (pintype "passive"))
    )
    (net (code "250") (name "Net-(Q21-D)") (class "Default")
      (node (ref "BT21") (pin "4") (pinfunction "4_4") (pintype "passive"))
      (node (ref "Q21") (pin "3") (pinfunction "D_3") (pintype "passive"))
    )
    (net (code "251") (name "Net-(Q22-D)") (class "Default")
      (node (ref "BT22") (pin "4") (pinfunction "4_4") (pintype "passive"))
      (node (ref "Q22") (pin "3") (pinfunction "D_3") (pintype "passive"))
    )
    (net (code "252") (name "Net-(Q23-D)") (class "Default")
      (node (ref "BT23") (pin "4") (pinfunction "4_4") (pintype "passive"))
      (node (ref "Q23") (pin "3") (pinfunction "D_3") (pintype "passive"))
    )
    (net (code "253") (name "Net-(Q24-D)") (class "Default")
      (node (ref "BT24") (pin "4") (pinfunction "4_4") (pintype "passive"))
      (node (ref "Q24") (pin "3") (pinfunction "D_3") (pintype "passive"))
    )
    (net (code "254") (name "Net-(Q25-D)") (class "Default")
      (node (ref "BT25") (pin "4") (pinfunction "4_4") (pintype "passive"))
      (node (ref "Q25") (pin "3") (pinfunction "D_3") (pintype "passive"))
    )
    (net (code "255") (name "Net-(Q26-D)") (class "Default")
      (node (ref "BT26") (pin "4") (pinfunction "4_4") (pintype "passive"))
      (node (ref "Q26") (pin "3") (pinfunction "D_3") (pintype "passive"))
    )
    (net (code "256") (name "Net-(Q27-D)") (class "Default")
      (node (ref "BT27") (pin "4") (pinfunction "4_4") (pintype "passive"))
      (node (ref "Q27") (pin "3") (pinfunction "D_3") (pintype "passive"))
    )
    (net (code "257") (name "Net-(Q28-D)") (class "Default")
      (node (ref "BT28") (pin "4") (pinfunction "4_4") (pintype "passive"))
      (node (ref "Q28") (pin "3") (pinfunction "D_3") (pintype "passive"))
    )
    (net (code "258") (name "Net-(Q29-D)") (class "Default")
      (node (ref "BT29") (pin "4") (pinfunction "4_4") (pintype "passive"))
      (node (ref "Q29") (pin "3") (pinfunction "D_3") (pintype "passive"))
    )
    (net (code "259") (name "Net-(Q30-D)") (class "Default")
      (node (ref "BT30") (pin "4") (pinfunction "4_4") (pintype "passive"))
      (node (ref "Q30") (pin "3") (pinfunction "D_3") (pintype "passive"))
    )
    (net (code "260") (name "Net-(Q31-D)") (class "Default")
      (node (ref "BT31") (pin "4") (pinfunction "4_4") (pintype "passive"))
      (node (ref "Q31") (pin "3") (pinfunction "D_3") (pintype "passive"))
    )
    (net (code "261") (name "Net-(Q32-D)") (class "Default")
      (node (ref "BT32") (pin "4") (pinfunction "4_4") (pintype "passive"))
      (node (ref "Q32") (pin "3") (pinfunction "D_3") (pintype "passive"))
    )
    (net (code "262") (name "Net-(Q33-D)") (class "Default")
      (node (ref "BT33") (pin "4") (pinfunction "4_4") (pintype "passive"))
      (node (ref "Q33") (pin "3") (pinfunction "D_3") (pintype "passive"))
    )
    (net (code "263") (name "Net-(Q34-D)") (class "Default")
      (node (ref "BT34") (pin "4") (pinfunction "4_4") (pintype "passive"))
      (node (ref "Q34") (pin "3") (pinfunction "D_3") (pintype "passive"))
    )
    (net (code "264") (name "Net-(Q35-D)") (class "Default")
      (node (ref "BT35") (pin "4") (pinfunction "4_4") (pintype "passive"))
      (node (ref "Q35") (pin "3") (pinfunction "D_3") (pintype "passive"))
    )
    (net (code "265") (name "Net-(Q36-D)") (class "Default")
      (node (ref "BT36") (pin "4") (pinfunction "4_4") (pintype "passive"))
      (node (ref "Q36") (pin "3") (pinfunction "D_3") (pintype "passive"))
    )
    (net (code "266") (name "Net-(Q37-D)") (class "Default")
      (node (ref "BT37") (pin "4") (pinfunction "4_4") (pintype "passive"))
      (node (ref "Q37") (pin "3") (pinfunction "D_3") (pintype "passive"))
    )
    (net (code "267") (name "Net-(Q38-D)") (class "Default")
      (node (ref "BT38") (pin "4") (pinfunction "4_4") (pintype "passive"))
      (node (ref "Q38") (pin "3") (pinfunction "D_3") (pintype "passive"))
    )
    (net (code "268") (name "Net-(Q39-D)") (class "Default")
      (node (ref "BT39") (pin "4") (pinfunction "4_4") (pintype "passive"))
      (node (ref "Q39") (pin "3") (pinfunction "D_3") (pintype "passive"))
    )
    (net (code "269") (name "Net-(Q40-D)") (class "Default")
      (node (ref "BT40") (pin "4") (pinfunction "4_4") (pintype "passive"))
      (node (ref "Q40") (pin "3") (pinfunction "D_3") (pintype "passive"))
    )
    (net (code "270") (name "Net-(Q41-D)") (class "Default")
      (node (ref "BT41") (pin "4") (pinfunction "4_4") (pintype "passive"))
      (node (ref "Q41") (pin "3") (pinfunction "D_3") (pintype "passive"))
    )
    (net (code "271") (name "Net-(Q42-D)") (class "Default")
      (node (ref "BT42") (pin "4") (pinfunction "4_4") (pintype "passive"))
      (node (ref "Q42") (pin "3") (pinfunction "D_3") (pintype "passive"))
    )
    (net (code "272") (name "Net-(Q43-D)") (class "Default")
      (node (ref "BT43") (pin "4") (pinfunction "4_4") (pintype "passive"))
      (node (ref "Q43") (pin "3") (pinfunction "D_3") (pintype "passive"))
    )
    (net (code "273") (name "Net-(Q44-D)") (class "Default")
      (node (ref "BT44") (pin "4") (pinfunction "4_4") (pintype "passive"))
      (node (ref "Q44") (pin "3") (pinfunction "D_3") (pintype "passive"))
    )
    (net (code "274") (name "Net-(Q45-D)") (class "Default")
      (node (ref "BT45") (pin "4") (pinfunction "4_4") (pintype "passive"))
      (node (ref "Q45") (pin "3") (pinfunction "D_3") (pintype "passive"))
    )
    (net (code "275") (name "Net-(Q46-D)") (class "Default")
      (node (ref "BT46") (pin "4") (pinfunction "4_4") (pintype "passive"))
      (node (ref "Q46") (pin "3") (pinfunction "D_3") (pintype "passive"))
    )
    (net (code "276") (name "Net-(Q47-D)") (class "Default")
      (node (ref "BT47") (pin "4") (pinfunction "4_4") (pintype "passive"))
      (node (ref "Q47") (pin "3") (pinfunction "D_3") (pintype "passive"))
    )
    (net (code "277") (name "Net-(Q48-D)") (class "Default")
      (node (ref "BT48") (pin "4") (pinfunction "4_4") (pintype "passive"))
      (node (ref "Q48") (pin "3") (pinfunction "D_3") (pintype "passive"))
    )
    (net (code "278") (name "Net-(Q49-D)") (class "Default")
      (node (ref "BT49") (pin "4") (pinfunction "4_4") (pintype "passive"))
      (node (ref "Q49") (pin "3") (pinfunction "D_3") (pintype "passive"))
    )
    (net (code "279") (name "Net-(Q50-D)") (class "Default")
      (node (ref "BT50") (pin "4") (pinfunction "4_4") (pintype "passive"))
      (node (ref "Q50") (pin "3") (pinfunction "D_3") (pintype "passive"))
    )
    (net (code "280") (name "Net-(Q51-D)") (class "Default")
      (node (ref "BT51") (pin "4") (pinfunction "4_4") (pintype "passive"))
      (node (ref "Q51") (pin "3") (pinfunction "D_3") (pintype "passive"))
    )
    (net (code "281") (name "Net-(Q52-D)") (class "Default")
      (node (ref "BT52") (pin "4") (pinfunction "4_4") (pintype "passive"))
      (node (ref "Q52") (pin "3") (pinfunction "D_3") (pintype "passive"))
    )
    (net (code "282") (name "Net-(Q53-D)") (class "Default")
      (node (ref "BT53") (pin "4") (pinfunction "4_4") (pintype "passive"))
      (node (ref "Q53") (pin "3") (pinfunction "D_3") (pintype "passive"))
    )
    (net (code "283") (name "Net-(Q54-D)") (class "Default")
      (node (ref "BT54") (pin "4") (pinfunction "4_4") (pintype "passive"))
      (node (ref "Q54") (pin "3") (pinfunction "D_3") (pintype "passive"))
    )
    (net (code "284") (name "Net-(Q55-D)") (class "Default")
      (node (ref "BT55") (pin "4") (pinfunction "4_4") (pintype "passive"))
      (node (ref "Q55") (pin "3") (pinfunction "D_3") (pintype "passive"))
    )
    (net (code "285") (name "Net-(Q56-D)") (class "Default")
      (node (ref "BT56") (pin "4") (pinfunction "4_4") (pintype "passive"))
      (node (ref "Q56") (pin "3") (pinfunction "D_3") (pintype "passive"))
    )
    (net (code "286") (name "Net-(Q57-D)") (class "Default")
      (node (ref "BT57") (pin "4") (pinfunction "4_4") (pintype "passive"))
      (node (ref "Q57") (pin "3") (pinfunction "D_3") (pintype "passive"))
    )
    (net (code "287") (name "Net-(Q58-D)") (class "Default")
      (node (ref "BT58") (pin "4") (pinfunction "4_4") (pintype "passive"))
      (node (ref "Q58") (pin "3") (pinfunction "D_3") (pintype "passive"))
    )
    (net (code "288") (name "Net-(Q59-D)") (class "Default")
      (node (ref "BT59") (pin "4") (pinfunction "4_4") (pintype "passive"))
      (node (ref "Q59") (pin "3") (pinfunction "D_3") (pintype "passive"))
    )
    (net (code "289") (name "Net-(Q60-D)") (class "Default")
      (node (ref "BT60") (pin "4") (pinfunction "4_4") (pintype "passive"))
      (node (ref "Q60") (pin "3") (pinfunction "D_3") (pintype "passive"))
    )
    (net (code "290") (name "Net-(Q61-D)") (class "Default")
      (node (ref "BT61") (pin "4") (pinfunction "4_4") (pintype "passive"))
      (node (ref "Q61") (pin "3") (pinfunction "D_3") (pintype "passive"))
    )
    (net (code "291") (name "Net-(Q62-D)") (class "Default")
      (node (ref "BT62") (pin "4") (pinfunction "4_4") (pintype "passive"))
      (node (ref "Q62") (pin "3") (pinfunction "D_3") (pintype "passive"))
    )
    (net (code "292") (name "Net-(Q63-D)") (class "Default")
      (node (ref "BT63") (pin "4") (pinfunction "4_4") (pintype "passive"))
      (node (ref "Q63") (pin "3") (pinfunction "D_3") (pintype "passive"))
    )
    (net (code "293") (name "Net-(Q64-D)") (class "Default")
      (node (ref "BT64") (pin "4") (pinfunction "4_4") (pintype "passive"))
      (node (ref "Q64") (pin "3") (pinfunction "D_3") (pintype "passive"))
    )
    (net (code "294") (name "Net-(Q65-D)") (class "Default")
      (node (ref "BT65") (pin "4") (pinfunction "4_4") (pintype "passive"))
      (node (ref "Q65") (pin "3") (pinfunction "D_3") (pintype "passive"))
    )
    (net (code "295") (name "Net-(Q66-D)") (class "Default")
      (node (ref "BT66") (pin "4") (pinfunction "4_4") (pintype "passive"))
      (node (ref "Q66") (pin "3") (pinfunction "D_3") (pintype "passive"))
    )
    (net (code "296") (name "Net-(Q67-D)") (class "Default")
      (node (ref "BT67") (pin "4") (pinfunction "4_4") (pintype "passive"))
      (node (ref "Q67") (pin "3") (pinfunction "D_3") (pintype "passive"))
    )
    (net (code "297") (name "Net-(Q68-D)") (class "Default")
      (node (ref "BT68") (pin "4") (pinfunction "4_4") (pintype "passive"))
      (node (ref "Q68") (pin "3") (pinfunction "D_3") (pintype "passive"))
    )
    (net (code "298") (name "Net-(Q69-D)") (class "Default")
      (node (ref "BT69") (pin "4") (pinfunction "4_4") (pintype "passive"))
      (node (ref "Q69") (pin "3") (pinfunction "D_3") (pintype "passive"))
    )
    (net (code "299") (name "Net-(Q70-D)") (class "Default")
      (node (ref "BT70") (pin "4") (pinfunction "4_4") (pintype "passive"))
      (node (ref "Q70") (pin "3") (pinfunction "D_3") (pintype "passive"))
    )
    (net (code "300") (name "Net-(Q71-D)") (class "Default")
      (node (ref "BT71") (pin "4") (pinfunction "4_4") (pintype "passive"))
      (node (ref "Q71") (pin "3") (pinfunction "D_3") (pintype "passive"))
    )
    (net (code "301") (name "Net-(Q72-D)") (class "Default")
      (node (ref "BT72") (pin "4") (pinfunction "4_4") (pintype "passive"))
      (node (ref "Q72") (pin "3") (pinfunction "D_3") (pintype "passive"))
    )
    (net (code "302") (name "Net-(Q73-D)") (class "Default")
      (node (ref "BT73") (pin "4") (pinfunction "4_4") (pintype "passive"))
      (node (ref "Q73") (pin "3") (pinfunction "D_3") (pintype "passive"))
    )
    (net (code "303") (name "Net-(Q74-D)") (class "Default")
      (node (ref "BT74") (pin "4") (pinfunction "4_4") (pintype "passive"))
      (node (ref "Q74") (pin "3") (pinfunction "D_3") (pintype "passive"))
    )
    (net (code "304") (name "Net-(Q75-D)") (class "Default")
      (node (ref "BT75") (pin "4") (pinfunction "4_4") (pintype "passive"))
      (node (ref "Q75") (pin "3") (pinfunction "D_3") (pintype "passive"))
    )
    (net (code "305") (name "Net-(Q76-D)") (class "Default")
      (node (ref "BT76") (pin "4") (pinfunction "4_4") (pintype "passive"))
      (node (ref "Q76") (pin "3") (pinfunction "D_3") (pintype "passive"))
    )
    (net (code "306") (name "Net-(Q77-D)") (class "Default")
      (node (ref "BT77") (pin "4") (pinfunction "4_4") (pintype "passive"))
      (node (ref "Q77") (pin "3") (pinfunction "D_3") (pintype "passive"))
    )
    (net (code "307") (name "Net-(Q78-D)") (class "Default")
      (node (ref "BT78") (pin "4") (pinfunction "4_4") (pintype "passive"))
      (node (ref "Q78") (pin "3") (pinfunction "D_3") (pintype "passive"))
    )
    (net (code "308") (name "Net-(Q79-D)") (class "Default")
      (node (ref "BT79") (pin "4") (pinfunction "4_4") (pintype "passive"))
      (node (ref "Q79") (pin "3") (pinfunction "D_3") (pintype "passive"))
    )
    (net (code "309") (name "Net-(Q80-D)") (class "Default")
      (node (ref "BT80") (pin "4") (pinfunction "4_4") (pintype "passive"))
      (node (ref "Q80") (pin "3") (pinfunction "D_3") (pintype "passive"))
    )
    (net (code "310") (name "Net-(Q81-D)") (class "Default")
      (node (ref "BT81") (pin "4") (pinfunction "4_4") (pintype "passive"))
      (node (ref "Q81") (pin "3") (pinfunction "D_3") (pintype "passive"))
    )
    (net (code "311") (name "Net-(Q82-D)") (class "Default")
      (node (ref "BT82") (pin "4") (pinfunction "4_4") (pintype "passive"))
      (node (ref "Q82") (pin "3") (pinfunction "D_3") (pintype "passive"))
    )
    (net (code "312") (name "Net-(Q83-D)") (class "Default")
      (node (ref "BT83") (pin "4") (pinfunction "4_4") (pintype "passive"))
      (node (ref "Q83") (pin "3") (pinfunction "D_3") (pintype "passive"))
    )
    (net (code "313") (name "Net-(Q84-D)") (class "Default")
      (node (ref "BT84") (pin "4") (pinfunction "4_4") (pintype "passive"))
      (node (ref "Q84") (pin "3") (pinfunction "D_3") (pintype "passive"))
    )
    (net (code "314") (name "Net-(Q85-D)") (class "Default")
      (node (ref "BT85") (pin "4") (pinfunction "4_4") (pintype "passive"))
      (node (ref "Q85") (pin "3") (pinfunction "D_3") (pintype "passive"))
    )
    (net (code "315") (name "Net-(Q86-D)") (class "Default")
      (node (ref "BT86") (pin "4") (pinfunction "4_4") (pintype "passive"))
      (node (ref "Q86") (pin "3") (pinfunction "D_3") (pintype "passive"))
    )
    (net (code "316") (name "Net-(Q87-D)") (class "Default")
      (node (ref "BT87") (pin "4") (pinfunction "4_4") (pintype "passive"))
      (node (ref "Q87") (pin "3") (pinfunction "D_3") (pintype "passive"))
    )
    (net (code "317") (name "Net-(Q88-D)") (class "Default")
      (node (ref "BT88") (pin "4") (pinfunction "4_4") (pintype "passive"))
      (node (ref "Q88") (pin "3") (pinfunction "D_3") (pintype "passive"))
    )
    (net (code "318") (name "Net-(Q89-D)") (class "Default")
      (node (ref "BT89") (pin "4") (pinfunction "4_4") (pintype "passive"))
      (node (ref "Q89") (pin "3") (pinfunction "D_3") (pintype "passive"))
    )
    (net (code "319") (name "Net-(Q90-D)") (class "Default")
      (node (ref "BT90") (pin "4") (pinfunction "4_4") (pintype "passive"))
      (node (ref "Q90") (pin "3") (pinfunction "D_3") (pintype "passive"))
    )
    (net (code "320") (name "Net-(Q91-D)") (class "Default")
      (node (ref "BT91") (pin "4") (pinfunction "4_4") (pintype "passive"))
      (node (ref "Q91") (pin "3") (pinfunction "D_3") (pintype "passive"))
    )
    (net (code "321") (name "V_MCU") (class "Default")
      (node (ref "C1") (pin "2") (pinfunction "2_2") (pintype "passive"))
      (node (ref "C10") (pin "2") (pinfunction "2_2") (pintype "passive"))
      (node (ref "C11") (pin "2") (pinfunction "2_2") (pintype "passive"))
      (node (ref "C12") (pin "2") (pinfunction "2_2") (pintype "passive"))
      (node (ref "C13") (pin "2") (pinfunction "2_2") (pintype "passive"))
      (node (ref "C14") (pin "1") (pinfunction "1_1") (pintype "passive"))
      (node (ref "C15") (pin "1") (pinfunction "1_1") (pintype "passive"))
      (node (ref "C16") (pin "1") (pinfunction "1_1") (pintype "passive"))
      (node (ref "C17") (pin "1") (pinfunction "1_1") (pintype "passive"))
      (node (ref "C18") (pin "1") (pinfunction "1_1") (pintype "passive"))
      (node (ref "C19") (pin "1") (pinfunction "1_1") (pintype "passive"))
      (node (ref "C2") (pin "2") (pinfunction "2_2") (pintype "passive"))
      (node (ref "C20") (pin "1") (pinfunction "1_1") (pintype "passive"))
      (node (ref "C21") (pin "1") (pinfunction "1_1") (pintype "passive"))
      (node (ref "C22") (pin "1") (pinfunction "1_1") (pintype "passive"))
      (node (ref "C23") (pin "1") (pinfunction "1_1") (pintype "passive"))
      (node (ref "C24") (pin "1") (pinfunction "1_1") (pintype "passive"))
      (node (ref "C25") (pin "1") (pinfunction "1_1") (pintype "passive"))
      (node (ref "C26") (pin "1") (pinfunction "1_1") (pintype "passive"))
      (node (ref "C3") (pin "2") (pinfunction "2_2") (pintype "passive"))
      (node (ref "C4") (pin "2") (pinfunction "2_2") (pintype "passive"))
      (node (ref "C5") (pin "2") (pinfunction "2_2") (pintype "passive"))
      (node (ref "C6") (pin "2") (pinfunction "2_2") (pintype "passive"))
      (node (ref "C7") (pin "2") (pinfunction "2_2") (pintype "passive"))
      (node (ref "C8") (pin "2") (pinfunction "2_2") (pintype "passive"))
      (node (ref "C9") (pin "2") (pinfunction "2_2") (pintype "passive"))
      (node (ref "R183") (pin "2") (pinfunction "2_2") (pintype "passive"))
      (node (ref "R184") (pin "2") (pinfunction "2_2") (pintype "passive"))
      (node (ref "R185") (pin "2") (pinfunction "2_2") (pintype "passive"))
      (node (ref "R186") (pin "2") (pinfunction "2_2") (pintype "passive"))
      (node (ref "R187") (pin "2") (pinfunction "2_2") (pintype "passive"))
      (node (ref "R188") (pin "2") (pinfunction "2_2") (pintype "passive"))
      (node (ref "R189") (pin "2") (pinfunction "2_2") (pintype "passive"))
      (node (ref "R190") (pin "2") (pinfunction "2_2") (pintype "passive"))
      (node (ref "R191") (pin "2") (pinfunction "2_2") (pintype "passive"))
      (node (ref "R192") (pin "2") (pinfunction "2_2") (pintype "passive"))
      (node (ref "R193") (pin "2") (pinfunction "2_2") (pintype "passive"))
      (node (ref "R194") (pin "2") (pinfunction "2_2") (pintype "passive"))
      (node (ref "R195") (pin "2") (pinfunction "2_2") (pintype "passive"))
      (node (ref "R196") (pin "2") (pinfunction "2_2") (pintype "passive"))
      (node (ref "R198") (pin "2") (pinfunction "2_2") (pintype "passive"))
      (node (ref "U1") (pin "10") (pinfunction "~{RST}_10") (pintype "passive"))
      (node (ref "U1") (pin "16") (pinfunction "VDD_16") (pintype "passive"))
      (node (ref "U10") (pin "10") (pinfunction "~{RST}_10") (pintype "passive"))
      (node (ref "U10") (pin "16") (pinfunction "VDD_16") (pintype "passive"))
      (node (ref "U11") (pin "10") (pinfunction "~{RST}_10") (pintype "passive"))
      (node (ref "U11") (pin "16") (pinfunction "VDD_16") (pintype "passive"))
      (node (ref "U12") (pin "10") (pinfunction "~{RST}_10") (pintype "passive"))
      (node (ref "U12") (pin "16") (pinfunction "VDD_16") (pintype "passive"))
      (node (ref "U13") (pin "10") (pinfunction "~{RST}_10") (pintype "passive"))
      (node (ref "U13") (pin "16") (pinfunction "VDD_16") (pintype "passive"))
      (node (ref "U2") (pin "10") (pinfunction "~{RST}_10") (pintype "passive"))
      (node (ref "U2") (pin "16") (pinfunction "VDD_16") (pintype "passive"))
      (node (ref "U3") (pin "10") (pinfunction "~{RST}_10") (pintype "passive"))
      (node (ref "U3") (pin "16") (pinfunction "VDD_16") (pintype "passive"))
      (node (ref "U4") (pin "10") (pinfunction "~{RST}_10") (pintype "passive"))
      (node (ref "U4") (pin "16") (pinfunction "VDD_16") (pintype "passive"))
      (node (ref "U5") (pin "10") (pinfunction "~{RST}_10") (pintype "passive"))
      (node (ref "U5") (pin "16") (pinfunction "VDD_16") (pintype "passive"))
      (node (ref "U6") (pin "10") (pinfunction "~{RST}_10") (pintype "passive"))
      (node (ref "U6") (pin "16") (pinfunction "VDD_16") (pintype "passive"))
      (node (ref "U7") (pin "10") (pinfunction "~{RST}_10") (pintype "passive"))
      (node (ref "U7") (pin "16") (pinfunction "VDD_16") (pintype "passive"))
      (node (ref "U8") (pin "10") (pinfunction "~{RST}_10") (pintype "passive"))
      (node (ref "U8") (pin "16") (pinfunction "VDD_16") (pintype "passive"))
      (node (ref "U9") (pin "10") (pinfunction "~{RST}_10") (pintype "passive"))
      (node (ref "U9") (pin "16") (pinfunction "VDD_16") (pintype "passive"))
    )
    (net (code "322") (name "unconnected-(U1-QH-Pad7)") (class "Default")
      (node (ref "U1") (pin "7") (pinfunction "QH_7") (pintype "passive+no_connect"))
    )
    (net (code "323") (name "unconnected-(U2-QH-Pad7)") (class "Default")
      (node (ref "U2") (pin "7") (pinfunction "QH_7") (pintype "passive+no_connect"))
    )
    (net (code "324") (name "unconnected-(U3-QH-Pad7)") (class "Default")
      (node (ref "U3") (pin "7") (pinfunction "QH_7") (pintype "passive+no_connect"))
    )
    (net (code "325") (name "unconnected-(U4-QH-Pad7)") (class "Default")
      (node (ref "U4") (pin "7") (pinfunction "QH_7") (pintype "passive+no_connect"))
    )
    (net (code "326") (name "unconnected-(U5-QH-Pad7)") (class "Default")
      (node (ref "U5") (pin "7") (pinfunction "QH_7") (pintype "passive+no_connect"))
    )
    (net (code "327") (name "unconnected-(U6-QH-Pad7)") (class "Default")
      (node (ref "U6") (pin "7") (pinfunction "QH_7") (pintype "passive+no_connect"))
    )
    (net (code "328") (name "unconnected-(U7-QH-Pad7)") (class "Default")
      (node (ref "U7") (pin "7") (pinfunction "QH_7") (pintype "passive+no_connect"))
    )
    (net (code "329") (name "unconnected-(U8-QH-Pad7)") (class "Default")
      (node (ref "U8") (pin "7") (pinfunction "QH_7") (pintype "passive+no_connect"))
    )
    (net (code "330") (name "unconnected-(U9-QH-Pad7)") (class "Default")
      (node (ref "U9") (pin "7") (pinfunction "QH_7") (pintype "passive+no_connect"))
    )
    (net (code "331") (name "unconnected-(U10-QH-Pad7)") (class "Default")
      (node (ref "U10") (pin "7") (pinfunction "QH_7") (pintype "passive+no_connect"))
    )
    (net (code "332") (name "unconnected-(U11-QH-Pad7)") (class "Default")
      (node (ref "U11") (pin "7") (pinfunction "QH_7") (pintype "passive+no_connect"))
    )
    (net (code "333") (name "unconnected-(U12-DATAO-Pad9)") (class "Default")
      (node (ref "U12") (pin "9") (pinfunction "DATAO_9") (pintype "passive+no_connect"))
    )
    (net (code "334") (name "unconnected-(U12-QH-Pad7)") (class "Default")
      (node (ref "U12") (pin "7") (pinfunction "QH_7") (pintype "passive+no_connect"))
    )
    (net (code "335") (name "unconnected-(U13-QH-Pad7)") (class "Default")
      (node (ref "U13") (pin "7") (pinfunction "QH_7") (pintype "passive+no_connect"))
    )
  )
)
